# BE_PROJECT_PCB.net
KiCad netlist of a schematic drawn in EAGLE
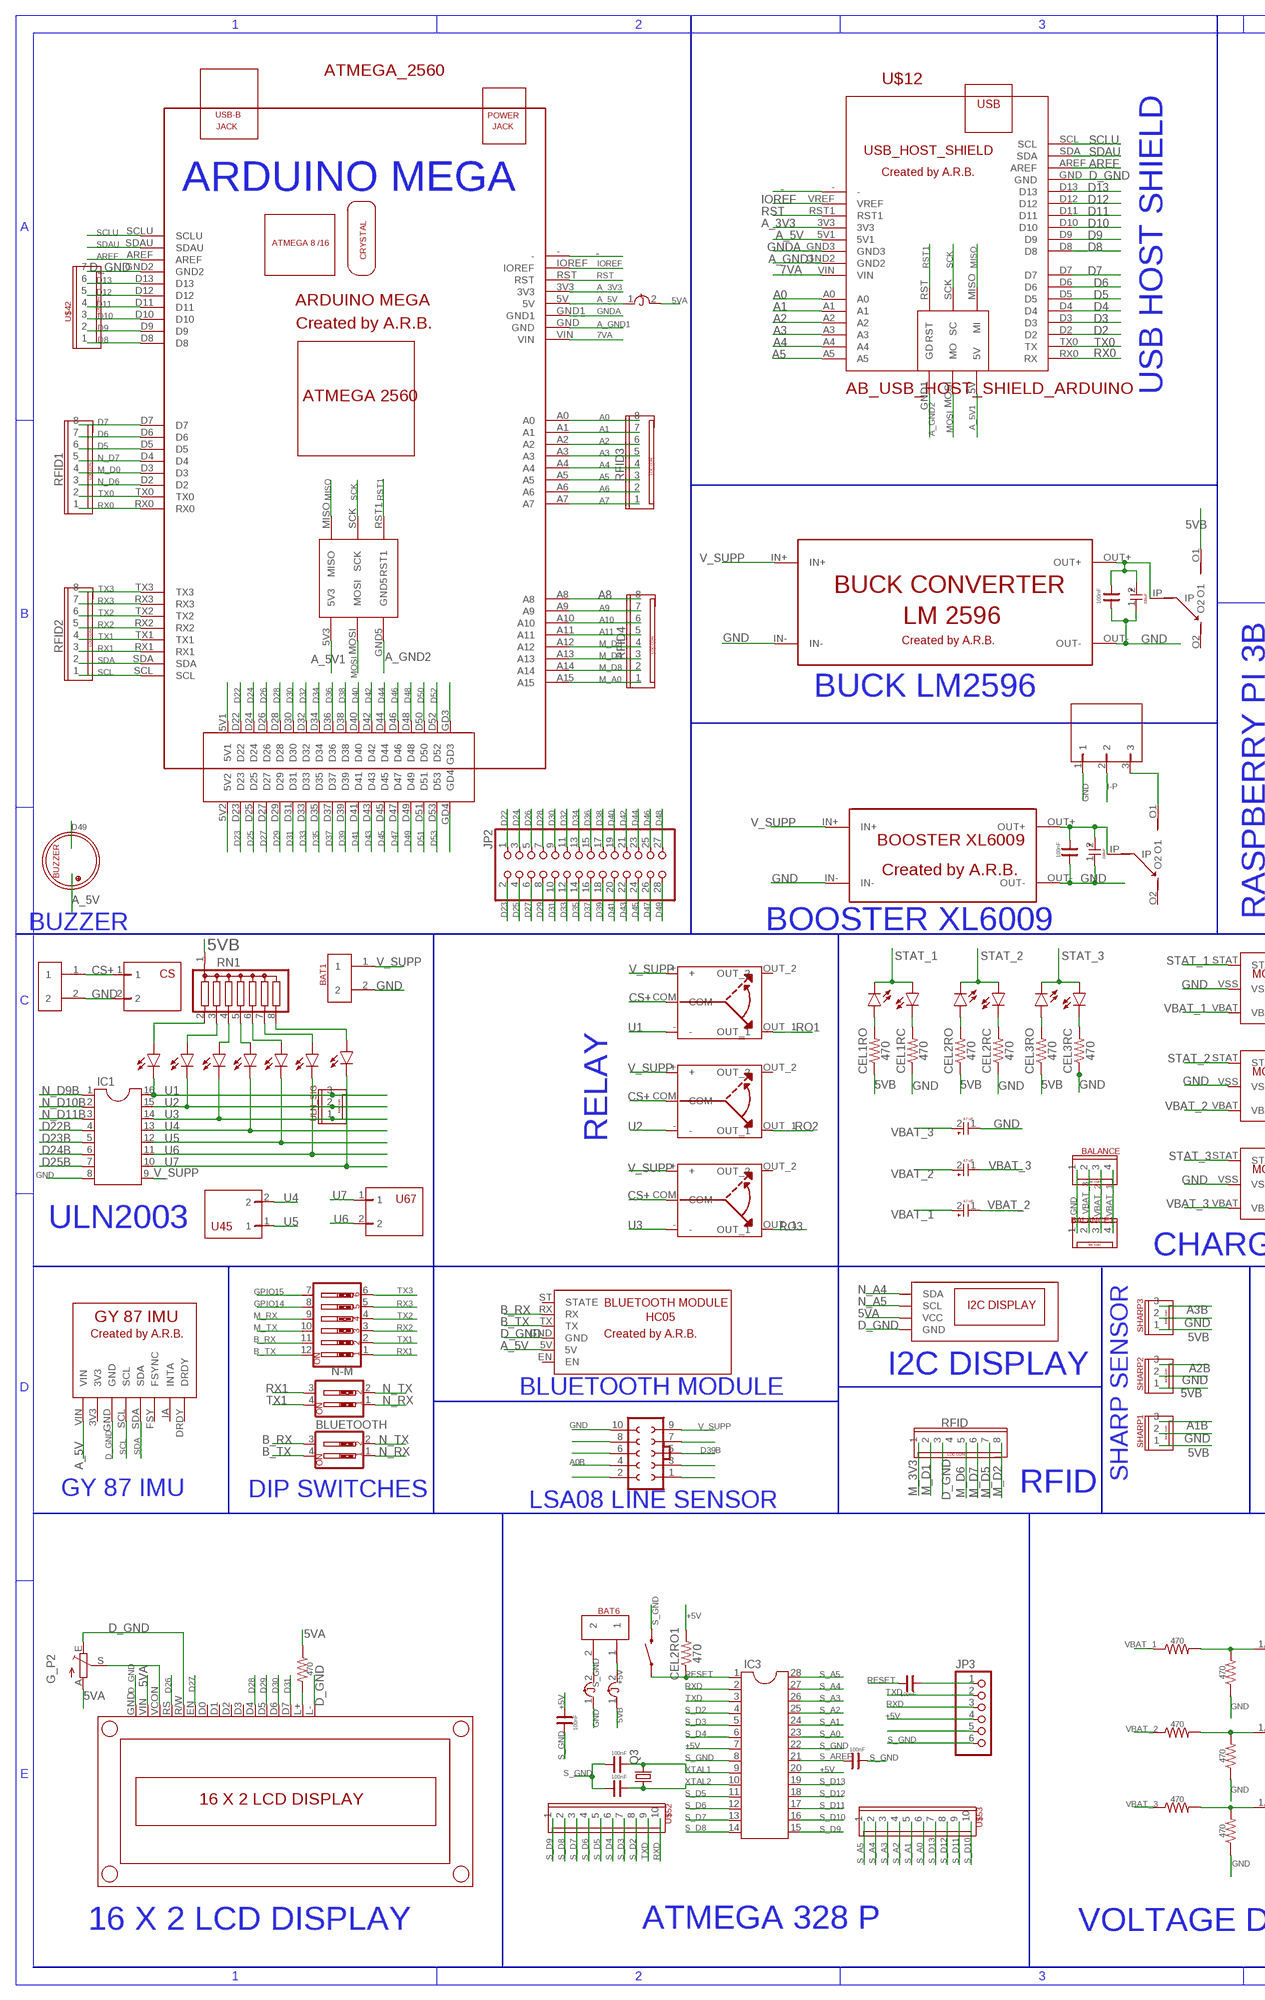
[diagram p0: schematic, sheet 1, part 1 of 3]
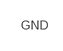
[diagram p1: schematic, sheet 1, part 2 of 3]
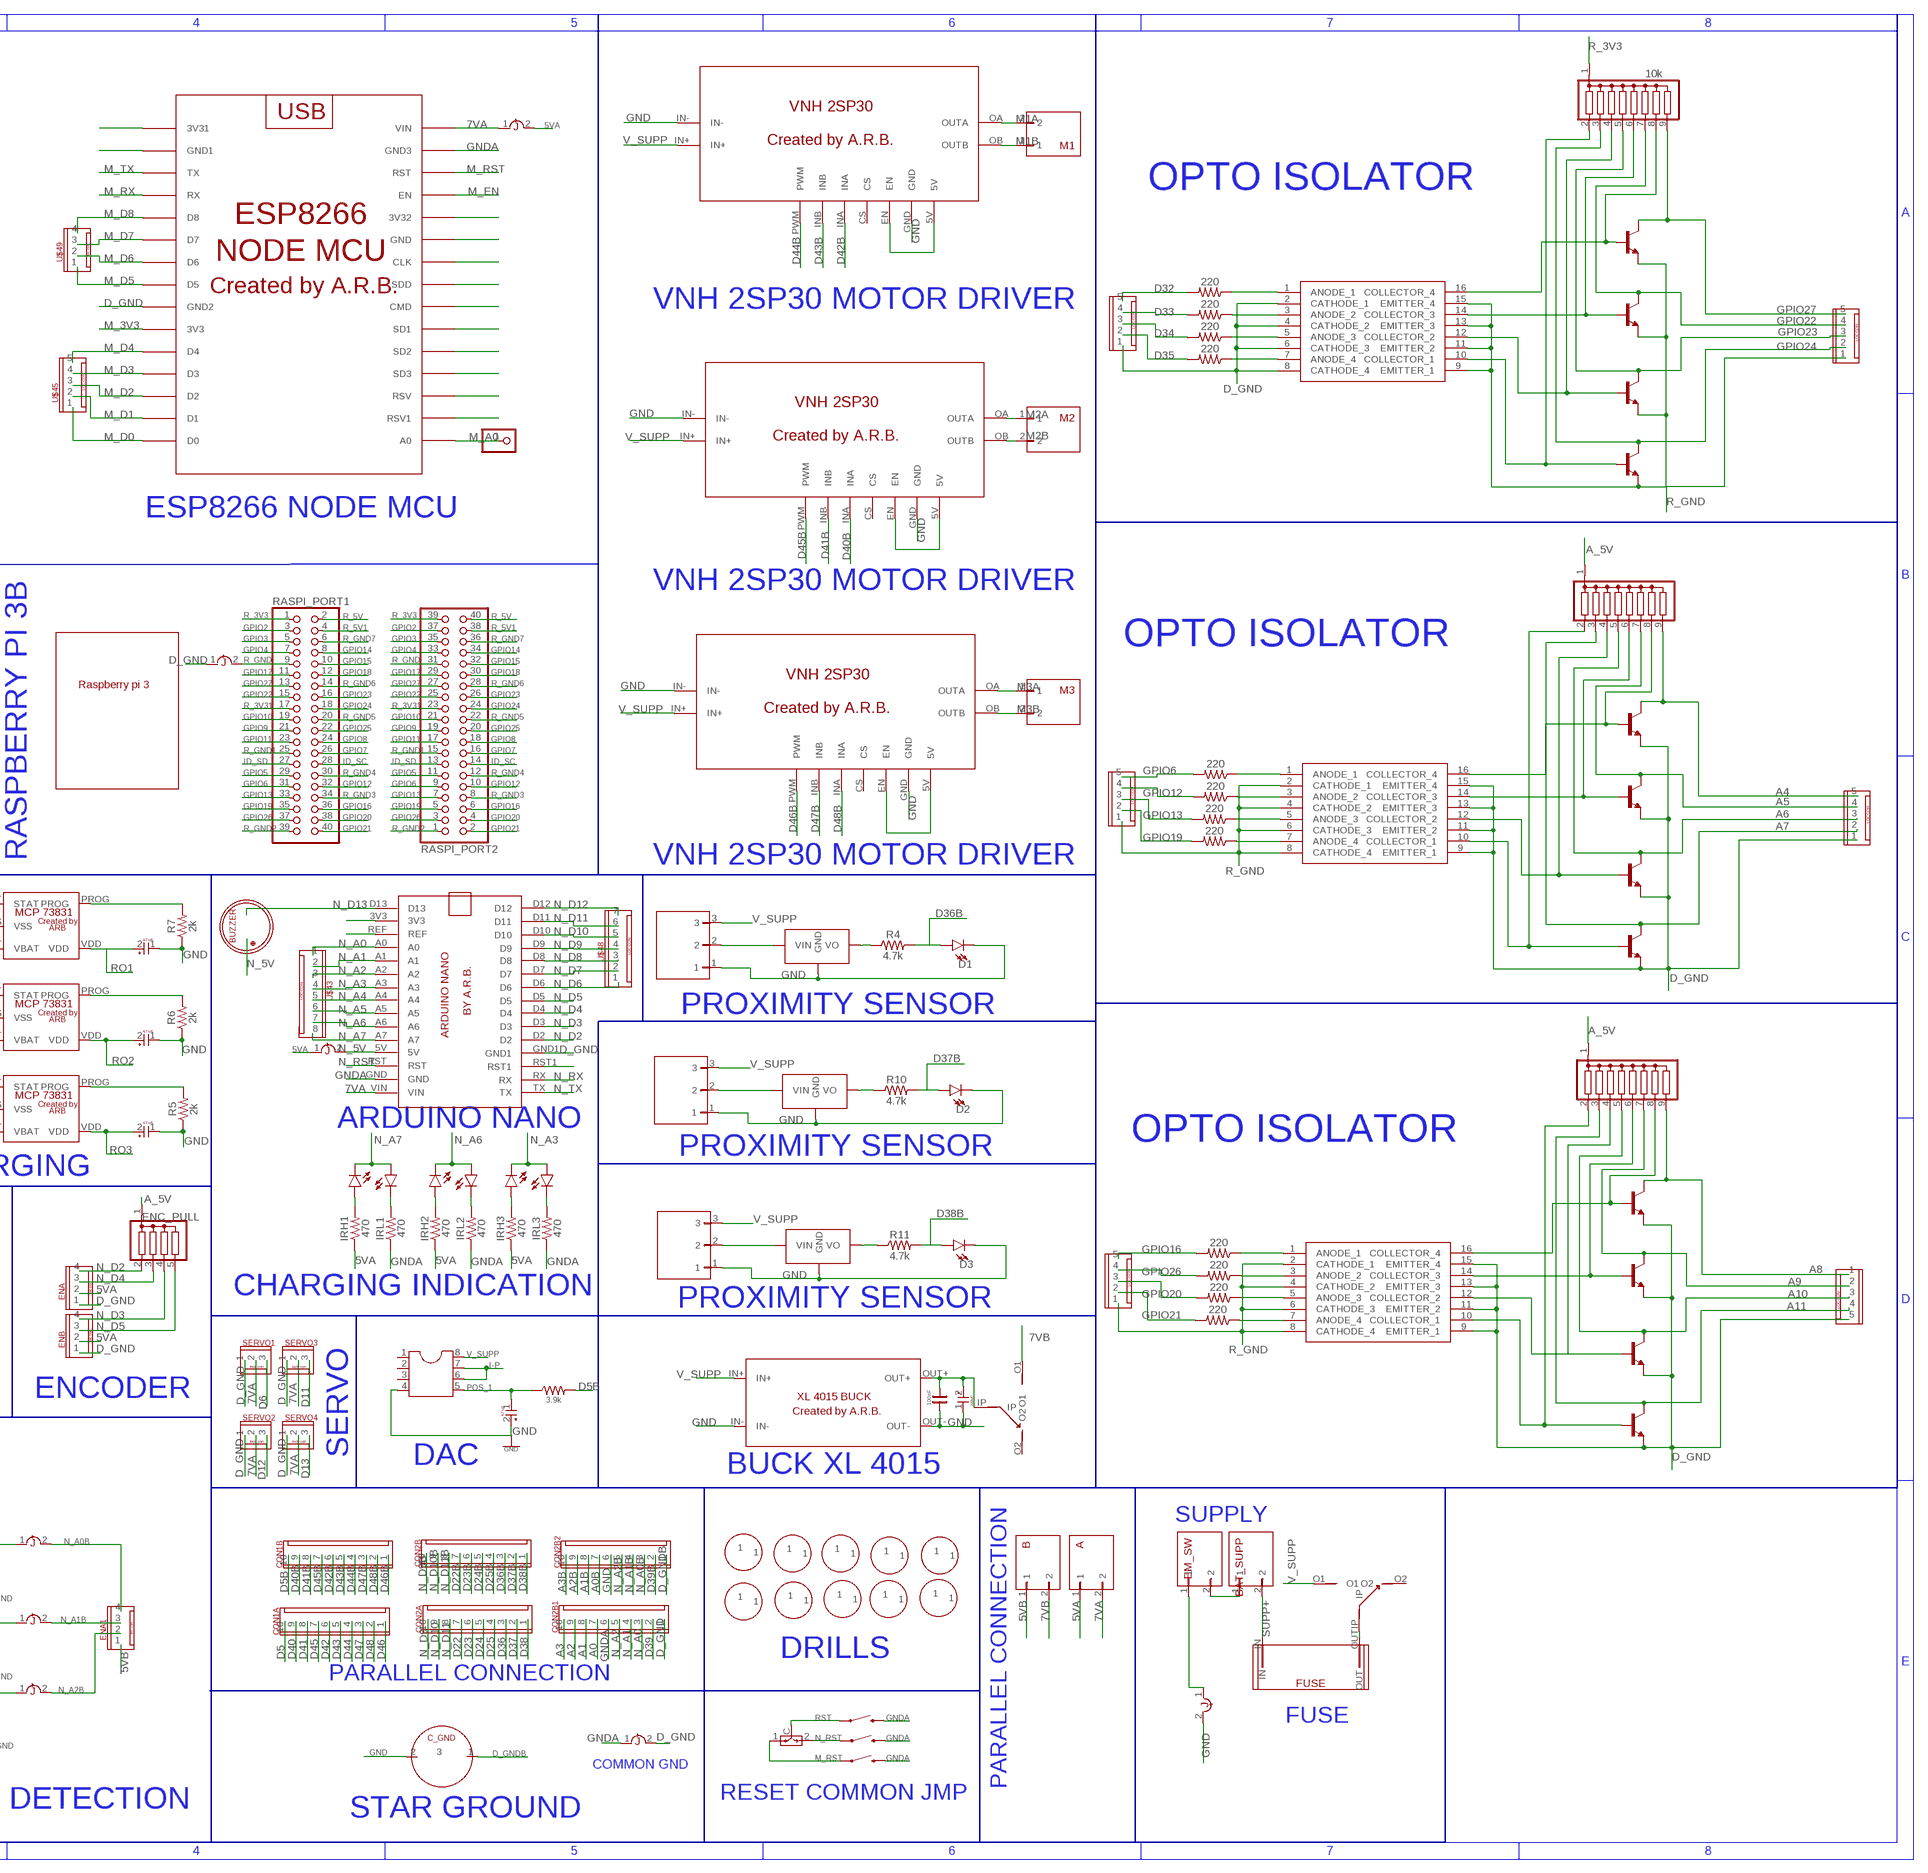
[diagram p2: schematic, sheet 1, part 3 of 3]

(export (version "E")
  (design (tool "Eeschema 10.0.6"))
  (components
    (comp (ref "10K")
      (value "10k")
      (footprint "eagle-import:SIL9")
      (libsource (lib "eagle-import") (part "G08R"))
    )
    (comp (ref "A")
      (value "AB_RIGHT_TER_BLK")
      (footprint "eagle-import:AB_RIGHT_TER_BLK")
      (libsource (lib "eagle-import") (part "AB_RIGHT_TER_BLK"))
    )
    (comp (ref "ATMEGA_2560")
      (value "AB_ARDUINO_MEGA")
      (footprint "eagle-import:AB_ARDUINO_MEGA")
      (libsource (lib "eagle-import") (part "AB_ARDUINO_MEGA"))
    )
    (comp (ref "B")
      (value "AB_RIGHT_TER_BLK")
      (footprint "eagle-import:AB_RIGHT_TER_BLK")
      (libsource (lib "eagle-import") (part "AB_RIGHT_TER_BLK"))
    )
    (comp (ref "BALANCE")
      (value "AB_4PIN_LOC_CONNECTOR")
      (footprint "eagle-import:AB_4PIN_LOC_CONNECTOR")
      (libsource (lib "eagle-import") (part "AB_4PIN_LOC_CONNECTOR"))
    )
    (comp (ref "BALANCE1")
      (value "AB_4PIN_LOC_CONNECTOR")
      (footprint "eagle-import:AB_4PIN_LOC_CONNECTOR")
      (libsource (lib "eagle-import") (part "AB_4PIN_LOC_CONNECTOR"))
    )
    (comp (ref "BAT1")
      (value "AB_SCREW_TERMINAL_5MM_2PIN")
      (footprint "eagle-import:AB_SCREW_TERMINAL_5MM_2PIN")
      (libsource (lib "eagle-import") (part "AB_SCREW_TERMINAL_5MM_2PIN"))
    )
    (comp (ref "BAT6")
      (value "AB_SCREW_TERMINAL_5MM_2PIN")
      (footprint "eagle-import:AB_SCREW_TERMINAL_5MM_2PIN")
      (libsource (lib "eagle-import") (part "AB_SCREW_TERMINAL_5MM_2PIN"))
    )
    (comp (ref "BAT_SUPP")
      (value "AB_RIGHT_TER_BLK")
      (footprint "eagle-import:AB_RIGHT_TER_BLK")
      (libsource (lib "eagle-import") (part "AB_RIGHT_TER_BLK"))
    )
    (comp (ref "BC547")
      (value "BC547")
      (footprint "eagle-import:TO92")
      (libsource (lib "eagle-import") (part "BC547"))
    )
    (comp (ref "BLUETOOTH")
      (value "SW_DIP-2")
      (footprint "eagle-import:EDG-02")
      (libsource (lib "eagle-import") (part "SW_DIP-2"))
    )
    (comp (ref "C1")
      (value "100nF")
      (footprint "eagle-import:C020-035X018")
      (libsource (lib "eagle-import") (part "CNP-C020-035X018"))
    )
    (comp (ref "C2")
      (value "100nF")
      (footprint "eagle-import:C020-035X018")
      (libsource (lib "eagle-import") (part "CNP-C020-035X018"))
    )
    (comp (ref "C3")
      (value "100nF")
      (footprint "eagle-import:C020-035X018")
      (libsource (lib "eagle-import") (part "CNP-C020-035X018"))
    )
    (comp (ref "C4")
      (value "100nF")
      (footprint "eagle-import:C020-035X018")
      (libsource (lib "eagle-import") (part "CNP-C020-035X018"))
    )
    (comp (ref "C5")
      (value "100nF")
      (footprint "eagle-import:C020-035X018")
      (libsource (lib "eagle-import") (part "CNP-C020-035X018"))
    )
    (comp (ref "C6")
      (value "100nF")
      (footprint "eagle-import:C020-035X018")
      (libsource (lib "eagle-import") (part "CNP-C020-035X018"))
    )
    (comp (ref "C7")
      (value "100nF")
      (footprint "eagle-import:C020-035X018")
      (libsource (lib "eagle-import") (part "CNP-C020-035X018"))
    )
    (comp (ref "C8")
      (value "100nF")
      (footprint "eagle-import:C020-035X018")
      (libsource (lib "eagle-import") (part "CNP-C020-035X018"))
    )
    (comp (ref "CEL1CC")
      (value "LED-3MM-NO_SILK")
      (footprint "eagle-import:LED_3MM-NS")
      (libsource (lib "eagle-import") (part "LED-3MM-NO_SILK"))
    )
    (comp (ref "CEL1CO")
      (value "LED-3MM-NO_SILK")
      (footprint "eagle-import:LED_3MM-NS")
      (libsource (lib "eagle-import") (part "LED-3MM-NO_SILK"))
    )
    (comp (ref "CEL1RC")
      (value "470")
      (footprint "eagle-import:AXIAL-0.3")
      (libsource (lib "eagle-import") (part "RESISTORAXIAL-0.3"))
    )
    (comp (ref "CEL1RO")
      (value "470")
      (footprint "eagle-import:AXIAL-0.3")
      (libsource (lib "eagle-import") (part "RESISTORAXIAL-0.3"))
    )
    (comp (ref "CEL2CC")
      (value "LED-3MM-NO_SILK")
      (footprint "eagle-import:LED_3MM-NS")
      (libsource (lib "eagle-import") (part "LED-3MM-NO_SILK"))
    )
    (comp (ref "CEL2CO")
      (value "LED-3MM-NO_SILK")
      (footprint "eagle-import:LED_3MM-NS")
      (libsource (lib "eagle-import") (part "LED-3MM-NO_SILK"))
    )
    (comp (ref "CEL2RC")
      (value "470")
      (footprint "eagle-import:AXIAL-0.3")
      (libsource (lib "eagle-import") (part "RESISTORAXIAL-0.3"))
    )
    (comp (ref "CEL2RO")
      (value "470")
      (footprint "eagle-import:AXIAL-0.3")
      (libsource (lib "eagle-import") (part "RESISTORAXIAL-0.3"))
    )
    (comp (ref "CEL2RO1")
      (value "470")
      (footprint "eagle-import:AXIAL-0.3")
      (libsource (lib "eagle-import") (part "RESISTORAXIAL-0.3"))
    )
    (comp (ref "CEL3CC")
      (value "LED-3MM-NO_SILK")
      (footprint "eagle-import:LED_3MM-NS")
      (libsource (lib "eagle-import") (part "LED-3MM-NO_SILK"))
    )
    (comp (ref "CEL3CO")
      (value "LED-3MM-NO_SILK")
      (footprint "eagle-import:LED_3MM-NS")
      (libsource (lib "eagle-import") (part "LED-3MM-NO_SILK"))
    )
    (comp (ref "CEL3RC")
      (value "470")
      (footprint "eagle-import:AXIAL-0.3")
      (libsource (lib "eagle-import") (part "RESISTORAXIAL-0.3"))
    )
    (comp (ref "CEL3RO")
      (value "470")
      (footprint "eagle-import:AXIAL-0.3")
      (libsource (lib "eagle-import") (part "RESISTORAXIAL-0.3"))
    )
    (comp (ref "CON1A")
      (value "AB_10PIN_LOC_CONNECTOR")
      (footprint "eagle-import:AB_10PIN_LOC_CONNECTOR")
      (libsource (lib "eagle-import") (part "AB_10PIN_LOC_CONNECTOR"))
    )
    (comp (ref "CON1B")
      (value "AB_10PIN_LOC_CONNECTOR")
      (footprint "eagle-import:AB_10PIN_LOC_CONNECTOR")
      (libsource (lib "eagle-import") (part "AB_10PIN_LOC_CONNECTOR"))
    )
    (comp (ref "CON2A")
      (value "AB_10PIN_LOC_CONNECTOR")
      (footprint "eagle-import:AB_10PIN_LOC_CONNECTOR")
      (libsource (lib "eagle-import") (part "AB_10PIN_LOC_CONNECTOR"))
    )
    (comp (ref "CON2B")
      (value "AB_10PIN_LOC_CONNECTOR")
      (footprint "eagle-import:AB_10PIN_LOC_CONNECTOR")
      (libsource (lib "eagle-import") (part "AB_10PIN_LOC_CONNECTOR"))
    )
    (comp (ref "CON2B1")
      (value "AB_10PIN_LOC_CONNECTOR")
      (footprint "eagle-import:AB_10PIN_LOC_CONNECTOR")
      (libsource (lib "eagle-import") (part "AB_10PIN_LOC_CONNECTOR"))
    )
    (comp (ref "CON2B2")
      (value "AB_10PIN_LOC_CONNECTOR")
      (footprint "eagle-import:AB_10PIN_LOC_CONNECTOR")
      (libsource (lib "eagle-import") (part "AB_10PIN_LOC_CONNECTOR"))
    )
    (comp (ref "CS")
      (value "AB_RIGHT_TER_BLK")
      (footprint "eagle-import:AB_RIGHT_TER_BLK")
      (libsource (lib "eagle-import") (part "AB_RIGHT_TER_BLK"))
    )
    (comp (ref "C_GND")
      (value "AB_JOINT_GND")
      (footprint "eagle-import:AB_JOINT_GND")
      (libsource (lib "eagle-import") (part "AB_JOINT_GND"))
    )
    (comp (ref "D1")
      (value "LED-3MM-NO_SILK")
      (footprint "eagle-import:LED_3MM-NS")
      (libsource (lib "eagle-import") (part "LED-3MM-NO_SILK"))
    )
    (comp (ref "D2")
      (value "LED-3MM-NO_SILK")
      (footprint "eagle-import:LED_3MM-NS")
      (libsource (lib "eagle-import") (part "LED-3MM-NO_SILK"))
    )
    (comp (ref "D3")
      (value "LED-3MM-NO_SILK")
      (footprint "eagle-import:LED_3MM-NS")
      (libsource (lib "eagle-import") (part "LED-3MM-NO_SILK"))
    )
    (comp (ref "EM_SW")
      (value "AB_RIGHT_TER_BLK")
      (footprint "eagle-import:AB_RIGHT_TER_BLK")
      (libsource (lib "eagle-import") (part "AB_RIGHT_TER_BLK"))
    )
    (comp (ref "ENA")
      (value "AB_4PIN_LOC_CONNECTOR")
      (footprint "eagle-import:AB_4PIN_LOC_CONNECTOR")
      (libsource (lib "eagle-import") (part "AB_4PIN_LOC_CONNECTOR"))
    )
    (comp (ref "ENA1")
      (value "AB_4PIN_LOC_CONNECTOR")
      (footprint "eagle-import:AB_4PIN_LOC_CONNECTOR")
      (libsource (lib "eagle-import") (part "AB_4PIN_LOC_CONNECTOR"))
    )
    (comp (ref "ENB")
      (value "AB_4PIN_LOC_CONNECTOR")
      (footprint "eagle-import:AB_4PIN_LOC_CONNECTOR")
      (libsource (lib "eagle-import") (part "AB_4PIN_LOC_CONNECTOR"))
    )
    (comp (ref "ENC_PULL")
      (value "G04R")
      (footprint "eagle-import:SIL5")
      (libsource (lib "eagle-import") (part "G04R"))
    )
    (comp (ref "FUSE")
      (value "AB_FUSE_HOLDER")
      (footprint "eagle-import:AB_FUSE_HOLDER")
      (libsource (lib "eagle-import") (part "AB_FUSE_HOLDER"))
    )
    (comp (ref "G_P2")
      (value "TRIM_EU-RS3")
      (footprint "eagle-import:RS3")
      (libsource (lib "eagle-import") (part "TRIM_EU-RS3"))
    )
    (comp (ref "IC1")
      (value "DIL16S")
      (footprint "eagle-import:SOCKET-16")
      (libsource (lib "eagle-import") (part "DIL16S"))
    )
    (comp (ref "IC2")
      (value "DIL8S")
      (footprint "eagle-import:SOCKET-08")
      (fields (field (name "SPICEPREFIX") "X"))
      (libsource (lib "eagle-import") (part "DIL8S"))
    )
    (comp (ref "IC3")
      (value "DIL28-3")
      (footprint "eagle-import:DIL28-3")
      (libsource (lib "eagle-import") (part "DIL28-3"))
    )
    (comp (ref "IC8")
      (value "TLP281-4(GB,J,F)")
      (footprint "eagle-import:SOIC127P700X210-16N")
      (fields
        (field (name "MOUSER_PART_NUMBER") "757-TLP281-4(GB,J,F)")
        (field (name "RS_PART_NUMBER") "7603227P")
      )
      (libsource (lib "eagle-import") (part "TLP281-4(GB,J,F)"))
    )
    (comp (ref "IC9")
      (value "TLP281-4(GB,J,F)")
      (footprint "eagle-import:SOIC127P700X210-16N")
      (fields
        (field (name "MOUSER_PART_NUMBER") "757-TLP281-4(GB,J,F)")
        (field (name "RS_PART_NUMBER") "7603227P")
      )
      (libsource (lib "eagle-import") (part "TLP281-4(GB,J,F)"))
    )
    (comp (ref "IC10")
      (value "TLP281-4(GB,J,F)")
      (footprint "eagle-import:SOIC127P700X210-16N")
      (fields
        (field (name "MOUSER_PART_NUMBER") "757-TLP281-4(GB,J,F)")
        (field (name "RS_PART_NUMBER") "7603227P")
      )
      (libsource (lib "eagle-import") (part "TLP281-4(GB,J,F)"))
    )
    (comp (ref "IH1")
      (value "LED-3MM-NO_SILK")
      (footprint "eagle-import:LED_3MM-NS")
      (libsource (lib "eagle-import") (part "LED-3MM-NO_SILK"))
    )
    (comp (ref "IH2")
      (value "LED-3MM-NO_SILK")
      (footprint "eagle-import:LED_3MM-NS")
      (libsource (lib "eagle-import") (part "LED-3MM-NO_SILK"))
    )
    (comp (ref "IH3")
      (value "LED-3MM-NO_SILK")
      (footprint "eagle-import:LED_3MM-NS")
      (libsource (lib "eagle-import") (part "LED-3MM-NO_SILK"))
    )
    (comp (ref "IL1")
      (value "LED-3MM-NO_SILK")
      (footprint "eagle-import:LED_3MM-NS")
      (libsource (lib "eagle-import") (part "LED-3MM-NO_SILK"))
    )
    (comp (ref "IL2")
      (value "LED-3MM-NO_SILK")
      (footprint "eagle-import:LED_3MM-NS")
      (libsource (lib "eagle-import") (part "LED-3MM-NO_SILK"))
    )
    (comp (ref "IL3")
      (value "LED-3MM-NO_SILK")
      (footprint "eagle-import:LED_3MM-NS")
      (libsource (lib "eagle-import") (part "LED-3MM-NO_SILK"))
    )
    (comp (ref "IRH1")
      (value "470")
      (footprint "eagle-import:AXIAL-0.3")
      (libsource (lib "eagle-import") (part "RESISTORAXIAL-0.3"))
    )
    (comp (ref "IRH2")
      (value "470")
      (footprint "eagle-import:AXIAL-0.3")
      (libsource (lib "eagle-import") (part "RESISTORAXIAL-0.3"))
    )
    (comp (ref "IRH3")
      (value "470")
      (footprint "eagle-import:AXIAL-0.3")
      (libsource (lib "eagle-import") (part "RESISTORAXIAL-0.3"))
    )
    (comp (ref "IRL1")
      (value "470")
      (footprint "eagle-import:AXIAL-0.3")
      (libsource (lib "eagle-import") (part "RESISTORAXIAL-0.3"))
    )
    (comp (ref "IRL2")
      (value "470")
      (footprint "eagle-import:AXIAL-0.3")
      (libsource (lib "eagle-import") (part "RESISTORAXIAL-0.3"))
    )
    (comp (ref "IRL3")
      (value "470")
      (footprint "eagle-import:AXIAL-0.3")
      (libsource (lib "eagle-import") (part "RESISTORAXIAL-0.3"))
    )
    (comp (ref "JP1")
      (value "PINHD-1X1")
      (footprint "eagle-import:1X01")
      (libsource (lib "eagle-import") (part "PINHD-1X1"))
    )
    (comp (ref "JP2")
      (value "PINHD-2X14")
      (footprint "eagle-import:2X14")
      (libsource (lib "eagle-import") (part "PINHD-2X14"))
    )
    (comp (ref "JP3")
      (value "PINHD-1X6")
      (footprint "eagle-import:1X06")
      (libsource (lib "eagle-import") (part "PINHD-1X6"))
    )
    (comp (ref "L1")
      (value "LED-3MM-NO_SILK")
      (footprint "eagle-import:LED_3MM-NS")
      (libsource (lib "eagle-import") (part "LED-3MM-NO_SILK"))
    )
    (comp (ref "L2")
      (value "LED-3MM-NO_SILK")
      (footprint "eagle-import:LED_3MM-NS")
      (libsource (lib "eagle-import") (part "LED-3MM-NO_SILK"))
    )
    (comp (ref "L3")
      (value "LED-3MM-NO_SILK")
      (footprint "eagle-import:LED_3MM-NS")
      (libsource (lib "eagle-import") (part "LED-3MM-NO_SILK"))
    )
    (comp (ref "L4")
      (value "LED-3MM-NO_SILK")
      (footprint "eagle-import:LED_3MM-NS")
      (libsource (lib "eagle-import") (part "LED-3MM-NO_SILK"))
    )
    (comp (ref "L5")
      (value "LED-3MM-NO_SILK")
      (footprint "eagle-import:LED_3MM-NS")
      (libsource (lib "eagle-import") (part "LED-3MM-NO_SILK"))
    )
    (comp (ref "L6")
      (value "LED-3MM-NO_SILK")
      (footprint "eagle-import:LED_3MM-NS")
      (libsource (lib "eagle-import") (part "LED-3MM-NO_SILK"))
    )
    (comp (ref "L7")
      (value "LED-3MM-NO_SILK")
      (footprint "eagle-import:LED_3MM-NS")
      (libsource (lib "eagle-import") (part "LED-3MM-NO_SILK"))
    )
    (comp (ref "LSA_2")
      (value "LSA1")
      (footprint "eagle-import:S10V")
      (libsource (lib "eagle-import") (part "SOCKET-10V"))
    )
    (comp (ref "M1")
      (value "AB_RIGHT_TER_BLK")
      (footprint "eagle-import:AB_RIGHT_TER_BLK")
      (libsource (lib "eagle-import") (part "AB_RIGHT_TER_BLK"))
    )
    (comp (ref "M2")
      (value "AB_RIGHT_TER_BLK")
      (footprint "eagle-import:AB_RIGHT_TER_BLK")
      (libsource (lib "eagle-import") (part "AB_RIGHT_TER_BLK"))
    )
    (comp (ref "M3")
      (value "AB_RIGHT_TER_BLK")
      (footprint "eagle-import:AB_RIGHT_TER_BLK")
      (libsource (lib "eagle-import") (part "AB_RIGHT_TER_BLK"))
    )
    (comp (ref "MEGA_RST")
      (value "MOMENTARY-SWITCH-SPST-PTH-6.0MM")
      (footprint "eagle-import:TACTILE_SWITCH_PTH_6.0MM")
      (libsource (lib "eagle-import") (part "MOMENTARY-SWITCH-SPST-PTH-6.0MM"))
    )
    (comp (ref "MEGA_RST1")
      (value "MOMENTARY-SWITCH-SPST-PTH-6.0MM")
      (footprint "eagle-import:TACTILE_SWITCH_PTH_6.0MM")
      (libsource (lib "eagle-import") (part "MOMENTARY-SWITCH-SPST-PTH-6.0MM"))
    )
    (comp (ref "M_RST")
      (value "MOMENTARY-SWITCH-SPST-PTH-6.0MM")
      (footprint "eagle-import:TACTILE_SWITCH_PTH_6.0MM")
      (libsource (lib "eagle-import") (part "MOMENTARY-SWITCH-SPST-PTH-6.0MM"))
    )
    (comp (ref "N-M")
      (value "SW_DIP-2")
      (footprint "eagle-import:EDG-02")
      (libsource (lib "eagle-import") (part "SW_DIP-2"))
    )
    (comp (ref "NANO")
      (value "AB_JUMPER_ONE_WAY")
      (footprint "eagle-import:AB_JUMPER_ONE_WAY")
      (libsource (lib "eagle-import") (part "AB_JUMPER_ONE_WAY"))
    )
    (comp (ref "NODEMCU")
      (value "AB_JUMPER_ONE_WAY")
      (footprint "eagle-import:AB_JUMPER_ONE_WAY")
      (libsource (lib "eagle-import") (part "AB_JUMPER_ONE_WAY"))
    )
    (comp (ref "N_RST")
      (value "MOMENTARY-SWITCH-SPST-PTH-6.0MM")
      (footprint "eagle-import:TACTILE_SWITCH_PTH_6.0MM")
      (libsource (lib "eagle-import") (part "MOMENTARY-SWITCH-SPST-PTH-6.0MM"))
    )
    (comp (ref "OISO1")
      (value "AB_5PIN_LOC_CONNECTOR")
      (footprint "eagle-import:AB_5PIN_LOC_CONNECTOR")
      (fields (field (name "SPICEPREFIX") "X"))
      (libsource (lib "eagle-import") (part "AB_5PIN_LOC_CONNECTOR"))
    )
    (comp (ref "OISO2")
      (value "AB_5PIN_LOC_CONNECTOR")
      (footprint "eagle-import:AB_5PIN_LOC_CONNECTOR")
      (fields (field (name "SPICEPREFIX") "X"))
      (libsource (lib "eagle-import") (part "AB_5PIN_LOC_CONNECTOR"))
    )
    (comp (ref "OISO3")
      (value "AB_5PIN_LOC_CONNECTOR")
      (footprint "eagle-import:AB_5PIN_LOC_CONNECTOR")
      (fields (field (name "SPICEPREFIX") "X"))
      (libsource (lib "eagle-import") (part "AB_5PIN_LOC_CONNECTOR"))
    )
    (comp (ref "OISO4")
      (value "AB_5PIN_LOC_CONNECTOR")
      (footprint "eagle-import:AB_5PIN_LOC_CONNECTOR")
      (fields (field (name "SPICEPREFIX") "X"))
      (libsource (lib "eagle-import") (part "AB_5PIN_LOC_CONNECTOR"))
    )
    (comp (ref "OISO5")
      (value "AB_5PIN_LOC_CONNECTOR")
      (footprint "eagle-import:AB_5PIN_LOC_CONNECTOR")
      (fields (field (name "SPICEPREFIX") "X"))
      (libsource (lib "eagle-import") (part "AB_5PIN_LOC_CONNECTOR"))
    )
    (comp (ref "OISO6")
      (value "AB_5PIN_LOC_CONNECTOR")
      (footprint "eagle-import:AB_5PIN_LOC_CONNECTOR")
      (fields (field (name "SPICEPREFIX") "X"))
      (libsource (lib "eagle-import") (part "AB_5PIN_LOC_CONNECTOR"))
    )
    (comp (ref "PPR_R1")
      (value "3.9k")
      (footprint "eagle-import:AXIAL-0.3")
      (libsource (lib "eagle-import") (part "RESISTORAXIAL-0.3"))
    )
    (comp (ref "PROX1")
      (value "AB_RIGHT_TER_BLK_3PIN")
      (footprint "eagle-import:AB_RIGHT_TER_BLK_3PIN")
      (libsource (lib "eagle-import") (part "AB_RIGHT_TER_BLK_3PIN"))
    )
    (comp (ref "PROX2")
      (value "AB_RIGHT_TER_BLK_3PIN")
      (footprint "eagle-import:AB_RIGHT_TER_BLK_3PIN")
      (libsource (lib "eagle-import") (part "AB_RIGHT_TER_BLK_3PIN"))
    )
    (comp (ref "PROX3")
      (value "AB_RIGHT_TER_BLK_3PIN")
      (footprint "eagle-import:AB_RIGHT_TER_BLK_3PIN")
      (libsource (lib "eagle-import") (part "AB_RIGHT_TER_BLK_3PIN"))
    )
    (comp (ref "Q3")
      (value "CRYSTALHC49U-V")
      (footprint "eagle-import:HC49U-V")
      (libsource (lib "eagle-import") (part "CRYSTALHC49U-V"))
    )
    (comp (ref "R4")
      (value "4.7k")
      (footprint "eagle-import:AXIAL-0.3")
      (libsource (lib "eagle-import") (part "RESISTORAXIAL-0.3"))
    )
    (comp (ref "R5")
      (value "2k")
      (footprint "eagle-import:AXIAL-0.3")
      (libsource (lib "eagle-import") (part "RESISTORAXIAL-0.3"))
    )
    (comp (ref "R6")
      (value "2k")
      (footprint "eagle-import:AXIAL-0.3")
      (libsource (lib "eagle-import") (part "RESISTORAXIAL-0.3"))
    )
    (comp (ref "R7")
      (value "2k")
      (footprint "eagle-import:AXIAL-0.3")
      (libsource (lib "eagle-import") (part "RESISTORAXIAL-0.3"))
    )
    (comp (ref "R10")
      (value "4.7k")
      (footprint "eagle-import:AXIAL-0.3")
      (libsource (lib "eagle-import") (part "RESISTORAXIAL-0.3"))
    )
    (comp (ref "R11")
      (value "4.7k")
      (footprint "eagle-import:AXIAL-0.3")
      (libsource (lib "eagle-import") (part "RESISTORAXIAL-0.3"))
    )
    (comp (ref "R17")
      (value "470")
      (footprint "eagle-import:AXIAL-0.3")
      (libsource (lib "eagle-import") (part "RESISTORAXIAL-0.3"))
    )
    (comp (ref "R18")
      (value "220")
      (footprint "eagle-import:AXIAL-0.3")
      (libsource (lib "eagle-import") (part "RESISTORAXIAL-0.3"))
    )
    (comp (ref "R19")
      (value "220")
      (footprint "eagle-import:AXIAL-0.3")
      (libsource (lib "eagle-import") (part "RESISTORAXIAL-0.3"))
    )
    (comp (ref "R20")
      (value "220")
      (footprint "eagle-import:AXIAL-0.3")
      (libsource (lib "eagle-import") (part "RESISTORAXIAL-0.3"))
    )
    (comp (ref "R21")
      (value "220")
      (footprint "eagle-import:AXIAL-0.3")
      (libsource (lib "eagle-import") (part "RESISTORAXIAL-0.3"))
    )
    (comp (ref "R22")
      (value "220")
      (footprint "eagle-import:AXIAL-0.3")
      (libsource (lib "eagle-import") (part "RESISTORAXIAL-0.3"))
    )
    (comp (ref "R23")
      (value "220")
      (footprint "eagle-import:AXIAL-0.3")
      (libsource (lib "eagle-import") (part "RESISTORAXIAL-0.3"))
    )
    (comp (ref "R24")
      (value "220")
      (footprint "eagle-import:AXIAL-0.3")
      (libsource (lib "eagle-import") (part "RESISTORAXIAL-0.3"))
    )
    (comp (ref "R25")
      (value "220")
      (footprint "eagle-import:AXIAL-0.3")
      (libsource (lib "eagle-import") (part "RESISTORAXIAL-0.3"))
    )
    (comp (ref "R26")
      (value "220")
      (footprint "eagle-import:AXIAL-0.3")
      (libsource (lib "eagle-import") (part "RESISTORAXIAL-0.3"))
    )
    (comp (ref "R27")
      (value "220")
      (footprint "eagle-import:AXIAL-0.3")
      (libsource (lib "eagle-import") (part "RESISTORAXIAL-0.3"))
    )
    (comp (ref "R28")
      (value "220")
      (footprint "eagle-import:AXIAL-0.3")
      (libsource (lib "eagle-import") (part "RESISTORAXIAL-0.3"))
    )
    (comp (ref "R32")
      (value "220")
      (footprint "eagle-import:AXIAL-0.3")
      (libsource (lib "eagle-import") (part "RESISTORAXIAL-0.3"))
    )
    (comp (ref "R33")
      (value "470")
      (footprint "eagle-import:AXIAL-0.3")
      (libsource (lib "eagle-import") (part "RESISTORAXIAL-0.3"))
    )
    (comp (ref "R34")
      (value "470")
      (footprint "eagle-import:AXIAL-0.3")
      (libsource (lib "eagle-import") (part "RESISTORAXIAL-0.3"))
    )
    (comp (ref "R35")
      (value "470")
      (footprint "eagle-import:AXIAL-0.3")
      (libsource (lib "eagle-import") (part "RESISTORAXIAL-0.3"))
    )
    (comp (ref "R36")
      (value "470")
      (footprint "eagle-import:AXIAL-0.3")
      (libsource (lib "eagle-import") (part "RESISTORAXIAL-0.3"))
    )
    (comp (ref "R37")
      (value "470")
      (footprint "eagle-import:AXIAL-0.3")
      (libsource (lib "eagle-import") (part "RESISTORAXIAL-0.3"))
    )
    (comp (ref "R38")
      (value "470")
      (footprint "eagle-import:AXIAL-0.3")
      (libsource (lib "eagle-import") (part "RESISTORAXIAL-0.3"))
    )
    (comp (ref "RASPI_PORT1")
      (value "PINHD-2X20")
      (footprint "eagle-import:2X20")
      (libsource (lib "eagle-import") (part "PINHD-2X20"))
    )
    (comp (ref "RASPI_PORT2")
      (value "PINHD-2X20")
      (footprint "eagle-import:2X20")
      (libsource (lib "eagle-import") (part "PINHD-2X20"))
    )
    (comp (ref "REL1")
      (value "12v")
      (footprint "eagle-import:AB_ELECTROMAGNETIC_RELAY")
      (libsource (lib "eagle-import") (part "AB_ELECTROMAGNETIC_RELAY"))
    )
    (comp (ref "REL2")
      (value "12v")
      (footprint "eagle-import:AB_ELECTROMAGNETIC_RELAY")
      (libsource (lib "eagle-import") (part "AB_ELECTROMAGNETIC_RELAY"))
    )
    (comp (ref "REL3")
      (value "12v")
      (footprint "eagle-import:AB_ELECTROMAGNETIC_RELAY")
      (libsource (lib "eagle-import") (part "AB_ELECTROMAGNETIC_RELAY"))
    )
    (comp (ref "RFID")
      (value "AB_8PIN_LOC_CONNECTOR")
      (footprint "eagle-import:AB_8PIN_LOC_CONNECTOR")
      (libsource (lib "eagle-import") (part "AB_8PIN_LOC_CONNECTOR"))
    )
    (comp (ref "RFID1")
      (value "AB_8PIN_LOC_CONNECTOR")
      (footprint "eagle-import:AB_8PIN_LOC_CONNECTOR")
      (libsource (lib "eagle-import") (part "AB_8PIN_LOC_CONNECTOR"))
    )
    (comp (ref "RFID2")
      (value "AB_8PIN_LOC_CONNECTOR")
      (footprint "eagle-import:AB_8PIN_LOC_CONNECTOR")
      (libsource (lib "eagle-import") (part "AB_8PIN_LOC_CONNECTOR"))
    )
    (comp (ref "RFID3")
      (value "AB_8PIN_LOC_CONNECTOR")
      (footprint "eagle-import:AB_8PIN_LOC_CONNECTOR")
      (libsource (lib "eagle-import") (part "AB_8PIN_LOC_CONNECTOR"))
    )
    (comp (ref "RFID4")
      (value "AB_8PIN_LOC_CONNECTOR")
      (footprint "eagle-import:AB_8PIN_LOC_CONNECTOR")
      (libsource (lib "eagle-import") (part "AB_8PIN_LOC_CONNECTOR"))
    )
    (comp (ref "RN1")
      (value "G07R")
      (footprint "eagle-import:SIL8")
      (libsource (lib "eagle-import") (part "G07R"))
    )
    (comp (ref "RN6")
      (value "G08R")
      (footprint "eagle-import:SIL9")
      (libsource (lib "eagle-import") (part "G08R"))
    )
    (comp (ref "RN7")
      (value "G08R")
      (footprint "eagle-import:SIL9")
      (libsource (lib "eagle-import") (part "G08R"))
    )
    (comp (ref "SERVO1")
      (value "AB_3PIN_LOC_CONNECTOR")
      (footprint "eagle-import:AB_3PIN_LOC_CONNECTOR")
      (libsource (lib "eagle-import") (part "AB_3PIN_LOC_CONNECTOR"))
    )
    (comp (ref "SERVO2")
      (value "AB_3PIN_LOC_CONNECTOR")
      (footprint "eagle-import:AB_3PIN_LOC_CONNECTOR")
      (libsource (lib "eagle-import") (part "AB_3PIN_LOC_CONNECTOR"))
    )
    (comp (ref "SERVO3")
      (value "AB_3PIN_LOC_CONNECTOR")
      (footprint "eagle-import:AB_3PIN_LOC_CONNECTOR")
      (libsource (lib "eagle-import") (part "AB_3PIN_LOC_CONNECTOR"))
    )
    (comp (ref "SERVO4")
      (value "AB_3PIN_LOC_CONNECTOR")
      (footprint "eagle-import:AB_3PIN_LOC_CONNECTOR")
      (libsource (lib "eagle-import") (part "AB_3PIN_LOC_CONNECTOR"))
    )
    (comp (ref "SHARP1")
      (value "AB_3PIN_LOC_CONNECTOR")
      (footprint "eagle-import:AB_3PIN_LOC_CONNECTOR")
      (libsource (lib "eagle-import") (part "AB_3PIN_LOC_CONNECTOR"))
    )
    (comp (ref "SHARP2")
      (value "AB_3PIN_LOC_CONNECTOR")
      (footprint "eagle-import:AB_3PIN_LOC_CONNECTOR")
      (libsource (lib "eagle-import") (part "AB_3PIN_LOC_CONNECTOR"))
    )
    (comp (ref "SHARP3")
      (value "AB_3PIN_LOC_CONNECTOR")
      (footprint "eagle-import:AB_3PIN_LOC_CONNECTOR")
      (libsource (lib "eagle-import") (part "AB_3PIN_LOC_CONNECTOR"))
    )
    (comp (ref "SW1")
      (value "SW_DIP-6")
      (footprint "eagle-import:EDG-06")
      (libsource (lib "eagle-import") (part "SW_DIP-6"))
    )
    (comp (ref "TR14")
      (value "BC547")
      (footprint "eagle-import:TO92")
      (libsource (lib "eagle-import") (part "BC547"))
    )
    (comp (ref "TR15")
      (value "BC547")
      (footprint "eagle-import:TO92")
      (libsource (lib "eagle-import") (part "BC547"))
    )
    (comp (ref "TR16")
      (value "BC547")
      (footprint "eagle-import:TO92")
      (libsource (lib "eagle-import") (part "BC547"))
    )
    (comp (ref "TR17")
      (value "BC547")
      (footprint "eagle-import:TO92")
      (libsource (lib "eagle-import") (part "BC547"))
    )
    (comp (ref "TR18")
      (value "BC547")
      (footprint "eagle-import:TO92")
      (libsource (lib "eagle-import") (part "BC547"))
    )
    (comp (ref "TR19")
      (value "BC547")
      (footprint "eagle-import:TO92")
      (libsource (lib "eagle-import") (part "BC547"))
    )
    (comp (ref "TR20")
      (value "BC547")
      (footprint "eagle-import:TO92")
      (libsource (lib "eagle-import") (part "BC547"))
    )
    (comp (ref "TR21")
      (value "BC547")
      (footprint "eagle-import:TO92")
      (libsource (lib "eagle-import") (part "BC547"))
    )
    (comp (ref "TR22")
      (value "BC547")
      (footprint "eagle-import:TO92")
      (libsource (lib "eagle-import") (part "BC547"))
    )
    (comp (ref "TR23")
      (value "BC547")
      (footprint "eagle-import:TO92")
      (libsource (lib "eagle-import") (part "BC547"))
    )
    (comp (ref "TR24")
      (value "BC547")
      (footprint "eagle-import:TO92")
      (libsource (lib "eagle-import") (part "BC547"))
    )
    (comp (ref "U$1")
      (value "AB_JUMPER_ONE_WAY")
      (footprint "eagle-import:AB_JUMPER_ONE_WAY")
      (libsource (lib "eagle-import") (part "AB_JUMPER_ONE_WAY"))
    )
    (comp (ref "U$2")
      (value "AB_16X2_LCD_DISPLAY")
      (footprint "eagle-import:AB_16X2_LCD_DISPLAY")
      (libsource (lib "eagle-import") (part "AB_16X2_LCD_DISPLAY"))
    )
    (comp (ref "U$3")
      (value "AB_VNH2SP30")
      (footprint "eagle-import:AB_VNH2SP30_MODULE")
      (libsource (lib "eagle-import") (part "AB_VNH2SP30"))
    )
    (comp (ref "U$4")
      (value "ESP8266_NODEMCU_BY_AB")
      (footprint "eagle-import:AB_ESP8266_BREAKOUT")
      (libsource (lib "eagle-import") (part "ESP8266_NODEMCU_BY_AB"))
    )
    (comp (ref "U$5")
      (value "AB_RASPBERRY_PI_3")
      (footprint "eagle-import:AB_RASPBERRY_PI_3")
      (libsource (lib "eagle-import") (part "AB_RASPBERRY_PI_3"))
    )
    (comp (ref "U$6")
      (value "AB_VNH2SP30")
      (footprint "eagle-import:AB_VNH2SP30_MODULE")
      (libsource (lib "eagle-import") (part "AB_VNH2SP30"))
    )
    (comp (ref "U$7")
      (value "AB_LM2596_BUCK_CONVERTER")
      (footprint "eagle-import:AB_LM2596_BUCK_CONVERTER")
      (libsource (lib "eagle-import") (part "AB_LM2596_BUCK_CONVERTER"))
    )
    (comp (ref "U$8")
      (value "AB_XL6009_BOOST_CONVERTER")
      (footprint "eagle-import:AB_XL6009E1_BOOST_CONVERTER")
      (libsource (lib "eagle-import") (part "AB_XL6009_BOOST_CONVERTER"))
    )
    (comp (ref "U$9")
      (value "AB_VNH2SP30")
      (footprint "eagle-import:AB_VNH2SP30_MODULE")
      (libsource (lib "eagle-import") (part "AB_VNH2SP30"))
    )
    (comp (ref "U$10")
      (value "AB_GY87")
      (footprint "eagle-import:AB_IMU_GY87")
      (libsource (lib "eagle-import") (part "AB_GY87"))
    )
    (comp (ref "U$11")
      (value "AB_BLUETOOTH_HC05")
      (footprint "eagle-import:AB_BLUETOOTH_HC05")
      (libsource (lib "eagle-import") (part "AB_BLUETOOTH_HC05"))
    )
    (comp (ref "U$12")
      (value "AB_USB_HOST_SHIELD_ARDUINO")
      (footprint "eagle-import:AB_USB_HOST_SHIELD_ARDUINO")
      (libsource (lib "eagle-import") (part "AB_USB_HOST_SHIELD_ARDUINO"))
    )
    (comp (ref "U$13")
      (value "AB_XL4015_5A_")
      (footprint "eagle-import:AB_XL_4015_5A_BUCK")
      (libsource (lib "eagle-import") (part "AB_XL4015_5A_"))
    )
    (comp (ref "U$14")
      (value "AB_SW")
      (footprint "eagle-import:AB_SW")
      (libsource (lib "eagle-import") (part "AB_SW"))
    )
    (comp (ref "U$15")
      (value "AB_SW")
      (footprint "eagle-import:AB_SW")
      (libsource (lib "eagle-import") (part "AB_SW"))
    )
    (comp (ref "U$16")
      (value "AB_SW")
      (footprint "eagle-import:AB_SW")
      (libsource (lib "eagle-import") (part "AB_SW"))
    )
    (comp (ref "U$17")
      (value "AB_JUMPER_ONE_WAY")
      (footprint "eagle-import:AB_JUMPER_ONE_WAY")
      (libsource (lib "eagle-import") (part "AB_JUMPER_ONE_WAY"))
    )
    (comp (ref "U$18")
      (value "AB_MCP_73831_LIPO_CHARGER")
      (footprint "eagle-import:AB_MCP_73831_LIPO_CHARGER")
      (libsource (lib "eagle-import") (part "AB_MCP_73831_LIPO_CHARGER"))
    )
    (comp (ref "U$19")
      (value "AB_MCP_73831_LIPO_CHARGER")
      (footprint "eagle-import:AB_MCP_73831_LIPO_CHARGER")
      (libsource (lib "eagle-import") (part "AB_MCP_73831_LIPO_CHARGER"))
    )
    (comp (ref "U$20")
      (value "AB_MCP_73831_LIPO_CHARGER")
      (footprint "eagle-import:AB_MCP_73831_LIPO_CHARGER")
      (libsource (lib "eagle-import") (part "AB_MCP_73831_LIPO_CHARGER"))
    )
    (comp (ref "U$21")
      (value "4.7 uF")
      (footprint "eagle-import:AB_POL_CAP")
      (libsource (lib "eagle-import") (part "AB_POL_CAP"))
    )
    (comp (ref "U$22")
      (value "4.7 uF")
      (footprint "eagle-import:AB_POL_CAP")
      (libsource (lib "eagle-import") (part "AB_POL_CAP"))
    )
    (comp (ref "U$23")
      (value "4.7 uF")
      (footprint "eagle-import:AB_POL_CAP")
      (libsource (lib "eagle-import") (part "AB_POL_CAP"))
    )
    (comp (ref "U$24")
      (value "AB_0.91_INCH_I2C_DISPLAY")
      (footprint "eagle-import:AB_0.91INCH_I2C_DISPLAY")
      (libsource (lib "eagle-import") (part "AB_0.91_INCH_I2C_DISPLAY"))
    )
    (comp (ref "U$25")
      (value "4.7 uF")
      (footprint "eagle-import:AB_POL_CAP")
      (libsource (lib "eagle-import") (part "AB_POL_CAP"))
    )
    (comp (ref "U$26")
      (value "4.7 uF")
      (footprint "eagle-import:AB_POL_CAP")
      (libsource (lib "eagle-import") (part "AB_POL_CAP"))
    )
    (comp (ref "U$27")
      (value "4.7 uF")
      (footprint "eagle-import:AB_POL_CAP")
      (libsource (lib "eagle-import") (part "AB_POL_CAP"))
    )
    (comp (ref "U$28")
      (value "AB_BUZZER")
      (footprint "eagle-import:AB_BUZZER")
      (libsource (lib "eagle-import") (part "AB_BUZZER"))
    )
    (comp (ref "U$29")
      (value "4.7 uF")
      (footprint "eagle-import:AB_POL_CAP")
      (libsource (lib "eagle-import") (part "AB_POL_CAP"))
    )
    (comp (ref "U$30")
      (value "AB_JUMPER_TWO_WAY")
      (footprint "eagle-import:AB_JUMPER_TWO_WAY")
      (libsource (lib "eagle-import") (part "AB_JUMPER_TWO_WAY"))
    )
    (comp (ref "U$31")
      (value "AB_JUMPER_ONE_WAY")
      (footprint "eagle-import:AB_JUMPER_ONE_WAY")
      (libsource (lib "eagle-import") (part "AB_JUMPER_ONE_WAY"))
    )
    (comp (ref "U$32")
      (value "AB_SW")
      (footprint "eagle-import:AB_SW")
      (libsource (lib "eagle-import") (part "AB_SW"))
    )
    (comp (ref "U$33")
      (value "AB_JUMPER_ONE_WAY")
      (footprint "eagle-import:AB_JUMPER_ONE_WAY")
      (libsource (lib "eagle-import") (part "AB_JUMPER_ONE_WAY"))
    )
    (comp (ref "U$34")
      (value "220uF")
      (footprint "eagle-import:AB_POL_CAP")
      (libsource (lib "eagle-import") (part "AB_POL_CAP"))
    )
    (comp (ref "U$35")
      (value "AB_ARDUINO_NANO")
      (footprint "eagle-import:AB_ARDUINO_NANO")
      (libsource (lib "eagle-import") (part "AB_ARDUINO_NANO"))
    )
    (comp (ref "U$36")
      (value "AB_SCREW_TERMINAL_5MM_2PIN")
      (footprint "eagle-import:AB_SCREW_TERMINAL_5MM_2PIN")
      (libsource (lib "eagle-import") (part "AB_SCREW_TERMINAL_5MM_2PIN"))
    )
    (comp (ref "U$37")
      (value "220uF")
      (footprint "eagle-import:AB_POL_CAP")
      (libsource (lib "eagle-import") (part "AB_POL_CAP"))
    )
    (comp (ref "U$38")
      (value "220uF")
      (footprint "eagle-import:AB_POL_CAP")
      (libsource (lib "eagle-import") (part "AB_POL_CAP"))
    )
    (comp (ref "U$39")
      (value "AB_BUZZER")
      (footprint "eagle-import:AB_BUZZER")
      (libsource (lib "eagle-import") (part "AB_BUZZER"))
    )
    (comp (ref "U$40")
      (value "AB_JUMPER_ONE_WAY")
      (footprint "eagle-import:AB_JUMPER_ONE_WAY")
      (libsource (lib "eagle-import") (part "AB_JUMPER_ONE_WAY"))
    )
    (comp (ref "U$41")
      (value "AB_JUMPER_ONE_WAY")
      (footprint "eagle-import:AB_JUMPER_ONE_WAY")
      (libsource (lib "eagle-import") (part "AB_JUMPER_ONE_WAY"))
    )
    (comp (ref "U$42")
      (value "AB_7PIN_LOC_CONNECTOR")
      (footprint "eagle-import:AB_7PIN_LOC_CONNECTOR")
      (libsource (lib "eagle-import") (part "AB_7PIN_LOC_CONNECTOR"))
    )
    (comp (ref "U$43")
      (value "AB_8PIN_LOC_CONNECTOR")
      (footprint "eagle-import:AB_8PIN_LOC_CONNECTOR")
      (libsource (lib "eagle-import") (part "AB_8PIN_LOC_CONNECTOR"))
    )
    (comp (ref "U$44")
      (value "AB_7805_FLAT")
      (footprint "eagle-import:AB_7805_FLAT")
      (libsource (lib "eagle-import") (part "AB_7805_FLAT"))
    )
    (comp (ref "U$45")
      (value "AB_5PIN_LOC_CONNECTOR")
      (footprint "eagle-import:AB_5PIN_LOC_CONNECTOR")
      (fields (field (name "SPICEPREFIX") "X"))
      (libsource (lib "eagle-import") (part "AB_5PIN_LOC_CONNECTOR"))
    )
    (comp (ref "U$46")
      (value "AB_7805_FLAT")
      (footprint "eagle-import:AB_7805_FLAT")
      (libsource (lib "eagle-import") (part "AB_7805_FLAT"))
    )
    (comp (ref "U$47")
      (value "AB_7805_FLAT")
      (footprint "eagle-import:AB_7805_FLAT")
      (libsource (lib "eagle-import") (part "AB_7805_FLAT"))
    )
    (comp (ref "U$48")
      (value "AB_7PIN_LOC_CONNECTOR")
      (footprint "eagle-import:AB_7PIN_LOC_CONNECTOR")
      (libsource (lib "eagle-import") (part "AB_7PIN_LOC_CONNECTOR"))
    )
    (comp (ref "U$49")
      (value "AB_4PIN_LOC_CONNECTOR")
      (footprint "eagle-import:AB_4PIN_LOC_CONNECTOR")
      (libsource (lib "eagle-import") (part "AB_4PIN_LOC_CONNECTOR"))
    )
    (comp (ref "U$50")
      (value "AB_JUMPER_ONE_WAY")
      (footprint "eagle-import:AB_JUMPER_ONE_WAY")
      (libsource (lib "eagle-import") (part "AB_JUMPER_ONE_WAY"))
    )
    (comp (ref "U$51")
      (value "AB_JUMPER_ONE_WAY")
      (footprint "eagle-import:AB_JUMPER_ONE_WAY")
      (libsource (lib "eagle-import") (part "AB_JUMPER_ONE_WAY"))
    )
    (comp (ref "U$52")
      (value "AB_10PIN_LOC_CONNECTOR")
      (footprint "eagle-import:AB_10PIN_LOC_CONNECTOR")
      (libsource (lib "eagle-import") (part "AB_10PIN_LOC_CONNECTOR"))
    )
    (comp (ref "U$53")
      (value "AB_10PIN_LOC_CONNECTOR")
      (footprint "eagle-import:AB_10PIN_LOC_CONNECTOR")
      (libsource (lib "eagle-import") (part "AB_10PIN_LOC_CONNECTOR"))
    )
    (comp (ref "U$54")
      (value "AB_PLATED_DRILL_160MIL")
      (footprint "eagle-import:AB_PLATED_DRILL_160MIL")
      (libsource (lib "eagle-import") (part "AB_PLATED_DRILL_160MIL"))
    )
    (comp (ref "U$55")
      (value "AB_PLATED_DRILL_160MIL")
      (footprint "eagle-import:AB_PLATED_DRILL_160MIL")
      (libsource (lib "eagle-import") (part "AB_PLATED_DRILL_160MIL"))
    )
    (comp (ref "U$56")
      (value "AB_PLATED_DRILL_160MIL")
      (footprint "eagle-import:AB_PLATED_DRILL_160MIL")
      (libsource (lib "eagle-import") (part "AB_PLATED_DRILL_160MIL"))
    )
    (comp (ref "U$57")
      (value "AB_PLATED_DRILL_160MIL")
      (footprint "eagle-import:AB_PLATED_DRILL_160MIL")
      (libsource (lib "eagle-import") (part "AB_PLATED_DRILL_160MIL"))
    )
    (comp (ref "U$58")
      (value "AB_PLATED_DRILL_160MIL")
      (footprint "eagle-import:AB_PLATED_DRILL_160MIL")
      (libsource (lib "eagle-import") (part "AB_PLATED_DRILL_160MIL"))
    )
    (comp (ref "U$59")
      (value "AB_PLATED_DRILL_160MIL")
      (footprint "eagle-import:AB_PLATED_DRILL_160MIL")
      (libsource (lib "eagle-import") (part "AB_PLATED_DRILL_160MIL"))
    )
    (comp (ref "U$60")
      (value "AB_PLATED_DRILL_160MIL")
      (footprint "eagle-import:AB_PLATED_DRILL_160MIL")
      (libsource (lib "eagle-import") (part "AB_PLATED_DRILL_160MIL"))
    )
    (comp (ref "U$61")
      (value "AB_PLATED_DRILL_160MIL")
      (footprint "eagle-import:AB_PLATED_DRILL_160MIL")
      (libsource (lib "eagle-import") (part "AB_PLATED_DRILL_160MIL"))
    )
    (comp (ref "U$62")
      (value "AB_JUMPER_ONE_WAY")
      (footprint "eagle-import:AB_JUMPER_ONE_WAY")
      (libsource (lib "eagle-import") (part "AB_JUMPER_ONE_WAY"))
    )
    (comp (ref "U$63")
      (value "AB_PLATED_DRILL_160MIL")
      (footprint "eagle-import:AB_PLATED_DRILL_160MIL")
      (libsource (lib "eagle-import") (part "AB_PLATED_DRILL_160MIL"))
    )
    (comp (ref "U$64")
      (value "AB_PLATED_DRILL_160MIL")
      (footprint "eagle-import:AB_PLATED_DRILL_160MIL")
      (libsource (lib "eagle-import") (part "AB_PLATED_DRILL_160MIL"))
    )
    (comp (ref "U45")
      (value "AB_RIGHT_TER_BLK")
      (footprint "eagle-import:AB_RIGHT_TER_BLK")
      (libsource (lib "eagle-import") (part "AB_RIGHT_TER_BLK"))
    )
    (comp (ref "U67")
      (value "AB_RIGHT_TER_BLK")
      (footprint "eagle-import:AB_RIGHT_TER_BLK")
      (libsource (lib "eagle-import") (part "AB_RIGHT_TER_BLK"))
    )
    (comp (ref "ULN_SIG")
      (value "AB_3PIN_LOC_CONNECTOR")
      (footprint "eagle-import:AB_3PIN_LOC_CONNECTOR")
      (libsource (lib "eagle-import") (part "AB_3PIN_LOC_CONNECTOR"))
    )
    (comp (ref "V-P")
      (value "AB_RIGHT_TER_BLK_3PIN")
      (footprint "eagle-import:AB_RIGHT_TER_BLK_3PIN")
      (libsource (lib "eagle-import") (part "AB_RIGHT_TER_BLK_3PIN"))
    )
  )
  (nets
    (net (code "1") (name "+5V") (class "Default")
      (node (ref "BAT6") (pin "1") (pinfunction "1_1") (pintype "bidirectional"))
      (node (ref "C5") (pin "1") (pinfunction "1_1") (pintype "passive"))
      (node (ref "CEL2RO1") (pin "P$2") (pinfunction "2_P$2") (pintype "passive"))
      (node (ref "IC3") (pin "20") (pinfunction "20_20") (pintype "passive"))
      (node (ref "IC3") (pin "7") (pinfunction "7_7") (pintype "passive"))
      (node (ref "JP3") (pin "4") (pinfunction "4_4") (pintype "passive"))
      (node (ref "U$50") (pin "2") (pinfunction "2_2") (pintype "bidirectional"))
    )
    (net (code "2") (name "-") (class "Default")
      (node (ref "ATMEGA_2560") (pin "-") (pinfunction "-_-") (pintype "bidirectional"))
      (node (ref "U$12") (pin "-") (pinfunction "-_-") (pintype "bidirectional"))
    )
    (net (code "3") (name "5VA") (class "Default")
      (node (ref "A") (pin "1") (pinfunction "1_1") (pintype "bidirectional"))
      (node (ref "ENA") (pin "2") (pinfunction "2_2") (pintype "bidirectional"))
      (node (ref "ENB") (pin "2") (pinfunction "2_2") (pintype "bidirectional"))
      (node (ref "G_P2") (pin "A") (pinfunction "A_A") (pintype "passive"))
      (node (ref "IRH1") (pin "P$1") (pinfunction "1_P$1") (pintype "passive"))
      (node (ref "IRH2") (pin "P$1") (pinfunction "1_P$1") (pintype "passive"))
      (node (ref "IRH3") (pin "P$1") (pinfunction "1_P$1") (pintype "passive"))
      (node (ref "NANO") (pin "1") (pinfunction "1_1") (pintype "bidirectional"))
      (node (ref "NODEMCU") (pin "2") (pinfunction "2_2") (pintype "bidirectional"))
      (node (ref "R17") (pin "P$1") (pinfunction "1_P$1") (pintype "passive"))
      (node (ref "U$2") (pin "VIN") (pinfunction "VIN_VIN") (pintype "bidirectional"))
      (node (ref "U$24") (pin "VCC") (pinfunction "VCC_VCC") (pintype "bidirectional"))
      (node (ref "U$31") (pin "2") (pinfunction "2_2") (pintype "bidirectional"))
    )
    (net (code "4") (name "5VB") (class "Default")
      (node (ref "B") (pin "1") (pinfunction "1_1") (pintype "bidirectional"))
      (node (ref "CEL1RO") (pin "P$1") (pinfunction "1_P$1") (pintype "passive"))
      (node (ref "CEL2RO") (pin "P$1") (pinfunction "1_P$1") (pintype "passive"))
      (node (ref "CEL3RO") (pin "P$1") (pinfunction "1_P$1") (pintype "passive"))
      (node (ref "ENA1") (pin "1") (pinfunction "1_1") (pintype "bidirectional"))
      (node (ref "RN1") (pin "1") (pinfunction "1_1") (pintype "passive"))
      (node (ref "SHARP1") (pin "1") (pinfunction "1_1") (pintype "bidirectional"))
      (node (ref "SHARP2") (pin "1") (pinfunction "1_1") (pintype "bidirectional"))
      (node (ref "SHARP3") (pin "1") (pinfunction "1_1") (pintype "bidirectional"))
      (node (ref "U$14") (pin "O1") (pinfunction "O1_O1") (pintype "bidirectional"))
      (node (ref "U$50") (pin "1") (pinfunction "1_1") (pintype "bidirectional"))
    )
    (net (code "5") (name "7VA") (class "Default")
      (node (ref "A") (pin "2") (pinfunction "2_2") (pintype "bidirectional"))
      (node (ref "ATMEGA_2560") (pin "VIN") (pinfunction "VIN_VIN") (pintype "bidirectional"))
      (node (ref "NODEMCU") (pin "1") (pinfunction "1_1") (pintype "bidirectional"))
      (node (ref "SERVO1") (pin "2") (pinfunction "2_2") (pintype "bidirectional"))
      (node (ref "SERVO2") (pin "2") (pinfunction "2_2") (pintype "bidirectional"))
      (node (ref "SERVO3") (pin "2") (pinfunction "2_2") (pintype "bidirectional"))
      (node (ref "SERVO4") (pin "2") (pinfunction "2_2") (pintype "bidirectional"))
      (node (ref "U$12") (pin "VIN") (pinfunction "VIN_VIN") (pintype "bidirectional"))
      (node (ref "U$35") (pin "VIN") (pinfunction "VIN_VIN") (pintype "bidirectional"))
      (node (ref "U$4") (pin "VIN") (pinfunction "VIN_VIN") (pintype "bidirectional"))
    )
    (net (code "6") (name "7VB") (class "Default")
      (node (ref "B") (pin "2") (pinfunction "2_2") (pintype "bidirectional"))
      (node (ref "U$16") (pin "O1") (pinfunction "O1_O1") (pintype "bidirectional"))
    )
    (net (code "7") (name "A0") (class "Default")
      (node (ref "ATMEGA_2560") (pin "A0") (pinfunction "A0_A0") (pintype "bidirectional"))
      (node (ref "CON2B1") (pin "7") (pinfunction "7_7") (pintype "bidirectional"))
      (node (ref "RFID3") (pin "8") (pinfunction "8_8") (pintype "bidirectional"))
      (node (ref "U$12") (pin "A0") (pinfunction "A0_A0") (pintype "bidirectional"))
    )
    (net (code "8") (name "A0B") (class "Default")
      (node (ref "CON2B2") (pin "7") (pinfunction "7_7") (pintype "bidirectional"))
      (node (ref "LSA_2") (pin "4") (pinfunction "4_4") (pintype "passive"))
    )
    (net (code "9") (name "A1") (class "Default")
      (node (ref "ATMEGA_2560") (pin "A1") (pinfunction "A1_A1") (pintype "bidirectional"))
      (node (ref "CON2B1") (pin "8") (pinfunction "8_8") (pintype "bidirectional"))
      (node (ref "RFID3") (pin "7") (pinfunction "7_7") (pintype "bidirectional"))
      (node (ref "U$12") (pin "A1") (pinfunction "A1_A1") (pintype "bidirectional"))
    )
    (net (code "10") (name "A1B") (class "Default")
      (node (ref "CON2B2") (pin "8") (pinfunction "8_8") (pintype "bidirectional"))
      (node (ref "SHARP1") (pin "3") (pinfunction "3_3") (pintype "bidirectional"))
    )
    (net (code "11") (name "A2") (class "Default")
      (node (ref "ATMEGA_2560") (pin "A2") (pinfunction "A2_A2") (pintype "bidirectional"))
      (node (ref "CON2B1") (pin "9") (pinfunction "9_9") (pintype "bidirectional"))
      (node (ref "RFID3") (pin "6") (pinfunction "6_6") (pintype "bidirectional"))
      (node (ref "U$12") (pin "A2") (pinfunction "A2_A2") (pintype "bidirectional"))
    )
    (net (code "12") (name "A2B") (class "Default")
      (node (ref "CON2B2") (pin "9") (pinfunction "9_9") (pintype "bidirectional"))
      (node (ref "SHARP2") (pin "3") (pinfunction "3_3") (pintype "bidirectional"))
    )
    (net (code "13") (name "A3") (class "Default")
      (node (ref "ATMEGA_2560") (pin "A3") (pinfunction "A3_A3") (pintype "bidirectional"))
      (node (ref "CON2B1") (pin "10") (pinfunction "10_10") (pintype "bidirectional"))
      (node (ref "RFID3") (pin "5") (pinfunction "5_5") (pintype "bidirectional"))
      (node (ref "U$12") (pin "A3") (pinfunction "A3_A3") (pintype "bidirectional"))
    )
    (net (code "14") (name "A3B") (class "Default")
      (node (ref "CON2B2") (pin "10") (pinfunction "10_10") (pintype "bidirectional"))
      (node (ref "SHARP3") (pin "3") (pinfunction "3_3") (pintype "bidirectional"))
    )
    (net (code "15") (name "A4") (class "Default")
      (node (ref "ATMEGA_2560") (pin "A4") (pinfunction "A4_A4") (pintype "bidirectional"))
      (node (ref "OISO4") (pin "5") (pinfunction "5_5") (pintype "bidirectional"))
      (node (ref "RFID3") (pin "4") (pinfunction "4_4") (pintype "bidirectional"))
      (node (ref "RN6") (pin "9") (pinfunction "9_9") (pintype "passive"))
      (node (ref "TR17") (pin "3") (pinfunction "C_3") (pintype "passive"))
      (node (ref "U$12") (pin "A4") (pinfunction "A4_A4") (pintype "bidirectional"))
    )
    (net (code "16") (name "A5") (class "Default")
      (node (ref "ATMEGA_2560") (pin "A5") (pinfunction "A5_A5") (pintype "bidirectional"))
      (node (ref "OISO4") (pin "4") (pinfunction "4_4") (pintype "bidirectional"))
      (node (ref "RFID3") (pin "3") (pinfunction "3_3") (pintype "bidirectional"))
      (node (ref "RN6") (pin "7") (pinfunction "7_7") (pintype "passive"))
      (node (ref "TR18") (pin "3") (pinfunction "C_3") (pintype "passive"))
      (node (ref "U$12") (pin "A5") (pinfunction "A5_A5") (pintype "bidirectional"))
    )
    (net (code "17") (name "A6") (class "Default")
      (node (ref "ATMEGA_2560") (pin "A6") (pinfunction "A6_A6") (pintype "bidirectional"))
      (node (ref "OISO4") (pin "3") (pinfunction "3_3") (pintype "bidirectional"))
      (node (ref "RFID3") (pin "2") (pinfunction "2_2") (pintype "bidirectional"))
      (node (ref "RN6") (pin "5") (pinfunction "5_5") (pintype "passive"))
      (node (ref "TR19") (pin "3") (pinfunction "C_3") (pintype "passive"))
    )
    (net (code "18") (name "A7") (class "Default")
      (node (ref "ATMEGA_2560") (pin "A7") (pinfunction "A7_A7") (pintype "bidirectional"))
      (node (ref "OISO4") (pin "2") (pinfunction "2_2") (pintype "bidirectional"))
      (node (ref "RFID3") (pin "1") (pinfunction "1_1") (pintype "bidirectional"))
      (node (ref "RN6") (pin "3") (pinfunction "3_3") (pintype "passive"))
      (node (ref "TR20") (pin "3") (pinfunction "C_3") (pintype "passive"))
    )
    (net (code "19") (name "A8") (class "Default")
      (node (ref "ATMEGA_2560") (pin "A8") (pinfunction "A8_A8") (pintype "bidirectional"))
      (node (ref "OISO6") (pin "1") (pinfunction "1_1") (pintype "bidirectional"))
      (node (ref "RFID4") (pin "8") (pinfunction "8_8") (pintype "bidirectional"))
      (node (ref "RN7") (pin "9") (pinfunction "9_9") (pintype "passive"))
      (node (ref "TR21") (pin "3") (pinfunction "C_3") (pintype "passive"))
    )
    (net (code "20") (name "A9") (class "Default")
      (node (ref "ATMEGA_2560") (pin "A9") (pinfunction "A9_A9") (pintype "bidirectional"))
      (node (ref "OISO6") (pin "2") (pinfunction "2_2") (pintype "bidirectional"))
      (node (ref "RFID4") (pin "7") (pinfunction "7_7") (pintype "bidirectional"))
      (node (ref "RN7") (pin "7") (pinfunction "7_7") (pintype "passive"))
      (node (ref "TR22") (pin "3") (pinfunction "C_3") (pintype "passive"))
    )
    (net (code "21") (name "A10") (class "Default")
      (node (ref "ATMEGA_2560") (pin "A10") (pinfunction "A10_A10") (pintype "bidirectional"))
      (node (ref "OISO6") (pin "3") (pinfunction "3_3") (pintype "bidirectional"))
      (node (ref "RFID4") (pin "6") (pinfunction "6_6") (pintype "bidirectional"))
      (node (ref "RN7") (pin "5") (pinfunction "5_5") (pintype "passive"))
      (node (ref "TR23") (pin "3") (pinfunction "C_3") (pintype "passive"))
    )
    (net (code "22") (name "A11") (class "Default")
      (node (ref "ATMEGA_2560") (pin "A11") (pinfunction "A11_A11") (pintype "bidirectional"))
      (node (ref "OISO6") (pin "4") (pinfunction "4_4") (pintype "bidirectional"))
      (node (ref "RFID4") (pin "5") (pinfunction "5_5") (pintype "bidirectional"))
      (node (ref "RN7") (pin "3") (pinfunction "3_3") (pintype "passive"))
      (node (ref "TR24") (pin "3") (pinfunction "C_3") (pintype "passive"))
    )
    (net (code "23") (name "AREF") (class "Default")
      (node (ref "ATMEGA_2560") (pin "AREF") (pinfunction "AREF_AREF") (pintype "bidirectional"))
      (node (ref "U$12") (pin "AREF") (pinfunction "AREF_AREF") (pintype "bidirectional"))
    )
    (net (code "24") (name "A_3V3") (class "Default")
      (node (ref "ATMEGA_2560") (pin "3V3") (pinfunction "3V3_3V3") (pintype "bidirectional"))
      (node (ref "U$12") (pin "3V3") (pinfunction "3V3_3V3") (pintype "bidirectional"))
    )
    (net (code "25") (name "A_5V") (class "Default")
      (node (ref "ATMEGA_2560") (pin "5V") (pinfunction "5V_5V") (pintype "bidirectional"))
      (node (ref "ENC_PULL") (pin "1") (pinfunction "1_1") (pintype "passive"))
      (node (ref "RN6") (pin "1") (pinfunction "1_1") (pintype "passive"))
      (node (ref "RN7") (pin "1") (pinfunction "1_1") (pintype "passive"))
      (node (ref "U$10") (pin "VIN") (pinfunction "VIN_VIN") (pintype "bidirectional"))
      (node (ref "U$11") (pin "5V") (pinfunction "5V_5V") (pintype "bidirectional"))
      (node (ref "U$12") (pin "5V1") (pinfunction "5V1_5V1") (pintype "bidirectional"))
      (node (ref "U$31") (pin "1") (pinfunction "1_1") (pintype "bidirectional"))
      (node (ref "U$39") (pin "+") (pinfunction "+_+") (pintype "bidirectional"))
    )
    (net (code "26") (name "A_5V1") (class "Default")
      (node (ref "ATMEGA_2560") (pin "5V3") (pinfunction "5V3_5V3") (pintype "bidirectional"))
      (node (ref "U$12") (pin "5V") (pinfunction "5V_5V") (pintype "bidirectional"))
    )
    (net (code "27") (name "A_GND1") (class "Default")
      (node (ref "ATMEGA_2560") (pin "GND") (pinfunction "GND_GND") (pintype "bidirectional"))
      (node (ref "U$12") (pin "GND2") (pinfunction "GND2_GND2") (pintype "bidirectional"))
    )
    (net (code "28") (name "A_GND2") (class "Default")
      (node (ref "ATMEGA_2560") (pin "GND5") (pinfunction "GND5_GND5") (pintype "bidirectional"))
      (node (ref "U$12") (pin "GND1") (pinfunction "GD_GND1") (pintype "bidirectional"))
    )
    (net (code "29") (name "B_RX") (class "Default")
      (node (ref "BLUETOOTH") (pin "3") (pinfunction "3_3") (pintype "passive"))
      (node (ref "SW1") (pin "11") (pinfunction "11_11") (pintype "passive"))
      (node (ref "U$11") (pin "RX") (pinfunction "RX_RX") (pintype "bidirectional"))
    )
    (net (code "30") (name "B_TX") (class "Default")
      (node (ref "BLUETOOTH") (pin "4") (pinfunction "4_4") (pintype "passive"))
      (node (ref "SW1") (pin "12") (pinfunction "12_12") (pintype "passive"))
      (node (ref "U$11") (pin "TX") (pinfunction "TX_TX") (pintype "bidirectional"))
    )
    (net (code "31") (name "CS+") (class "Default")
      (node (ref "CS") (pin "1") (pinfunction "1_1") (pintype "bidirectional"))
      (node (ref "REL1") (pin "COM") (pinfunction "COM_COM") (pintype "bidirectional"))
      (node (ref "REL2") (pin "COM") (pinfunction "COM_COM") (pintype "bidirectional"))
      (node (ref "REL3") (pin "COM") (pinfunction "COM_COM") (pintype "bidirectional"))
      (node (ref "U$36") (pin "1") (pinfunction "1_1") (pintype "bidirectional"))
    )
    (net (code "32") (name "D2") (class "Default")
      (node (ref "U$12") (pin "D2") (pinfunction "D2_D2") (pintype "bidirectional"))
    )
    (net (code "33") (name "D3") (class "Default")
      (node (ref "U$12") (pin "D3") (pinfunction "D3_D3") (pintype "bidirectional"))
    )
    (net (code "34") (name "D4") (class "Default")
      (node (ref "U$12") (pin "D4") (pinfunction "D4_D4") (pintype "bidirectional"))
    )
    (net (code "35") (name "D5") (class "Default")
      (node (ref "ATMEGA_2560") (pin "D5") (pinfunction "D5_D5") (pintype "bidirectional"))
      (node (ref "CON1A") (pin "10") (pinfunction "10_10") (pintype "bidirectional"))
      (node (ref "RFID1") (pin "6") (pinfunction "6_6") (pintype "bidirectional"))
      (node (ref "U$12") (pin "D5") (pinfunction "D5_D5") (pintype "bidirectional"))
    )
    (net (code "36") (name "D5B") (class "Default")
      (node (ref "CON1B") (pin "10") (pinfunction "10_10") (pintype "bidirectional"))
      (node (ref "PPR_R1") (pin "P$2") (pinfunction "2_P$2") (pintype "passive"))
    )
    (net (code "37") (name "D6") (class "Default")
      (node (ref "ATMEGA_2560") (pin "D6") (pinfunction "D6_D6") (pintype "bidirectional"))
      (node (ref "RFID1") (pin "7") (pinfunction "7_7") (pintype "bidirectional"))
      (node (ref "SERVO1") (pin "3") (pinfunction "3_3") (pintype "bidirectional"))
      (node (ref "U$12") (pin "D6") (pinfunction "D6_D6") (pintype "bidirectional"))
    )
    (net (code "38") (name "D7") (class "Default")
      (node (ref "ATMEGA_2560") (pin "D7") (pinfunction "D7_D7") (pintype "bidirectional"))
      (node (ref "RFID1") (pin "8") (pinfunction "8_8") (pintype "bidirectional"))
      (node (ref "U$12") (pin "D7") (pinfunction "D7_D7") (pintype "bidirectional"))
    )
    (net (code "39") (name "D8") (class "Default")
      (node (ref "ATMEGA_2560") (pin "D8") (pinfunction "D8_D8") (pintype "bidirectional"))
      (node (ref "U$12") (pin "D8") (pinfunction "D8_D8") (pintype "bidirectional"))
      (node (ref "U$42") (pin "1") (pinfunction "1_1") (pintype "bidirectional"))
    )
    (net (code "40") (name "D9") (class "Default")
      (node (ref "ATMEGA_2560") (pin "D9") (pinfunction "D9_D9") (pintype "bidirectional"))
      (node (ref "U$12") (pin "D9") (pinfunction "D9_D9") (pintype "bidirectional"))
      (node (ref "U$42") (pin "2") (pinfunction "2_2") (pintype "bidirectional"))
    )
    (net (code "41") (name "D10") (class "Default")
      (node (ref "ATMEGA_2560") (pin "D10") (pinfunction "D10_D10") (pintype "bidirectional"))
      (node (ref "U$12") (pin "D10") (pinfunction "D10_D10") (pintype "bidirectional"))
      (node (ref "U$42") (pin "3") (pinfunction "3_3") (pintype "bidirectional"))
    )
    (net (code "42") (name "D11") (class "Default")
      (node (ref "ATMEGA_2560") (pin "D11") (pinfunction "D11_D11") (pintype "bidirectional"))
      (node (ref "SERVO3") (pin "3") (pinfunction "3_3") (pintype "bidirectional"))
      (node (ref "U$12") (pin "D11") (pinfunction "D11_D11") (pintype "bidirectional"))
      (node (ref "U$42") (pin "4") (pinfunction "4_4") (pintype "bidirectional"))
    )
    (net (code "43") (name "D12") (class "Default")
      (node (ref "ATMEGA_2560") (pin "D12") (pinfunction "D12_D12") (pintype "bidirectional"))
      (node (ref "SERVO2") (pin "3") (pinfunction "3_3") (pintype "bidirectional"))
      (node (ref "U$12") (pin "D12") (pinfunction "D12_D12") (pintype "bidirectional"))
      (node (ref "U$42") (pin "5") (pinfunction "5_5") (pintype "bidirectional"))
    )
    (net (code "44") (name "D13") (class "Default")
      (node (ref "ATMEGA_2560") (pin "D13") (pinfunction "D13_D13") (pintype "bidirectional"))
      (node (ref "SERVO4") (pin "3") (pinfunction "3_3") (pintype "bidirectional"))
      (node (ref "U$12") (pin "D13") (pinfunction "D13_D13") (pintype "bidirectional"))
      (node (ref "U$42") (pin "6") (pinfunction "6_6") (pintype "bidirectional"))
    )
    (net (code "45") (name "D22") (class "Default")
      (node (ref "ATMEGA_2560") (pin "D22") (pinfunction "D22_D22") (pintype "bidirectional"))
      (node (ref "CON2A") (pin "7") (pinfunction "7_7") (pintype "bidirectional"))
      (node (ref "JP2") (pin "1") (pinfunction "1_1") (pintype "passive"))
    )
    (net (code "46") (name "D22B") (class "Default")
      (node (ref "CON2B") (pin "7") (pinfunction "7_7") (pintype "bidirectional"))
      (node (ref "IC1") (pin "4") (pinfunction "4_4") (pintype "passive"))
    )
    (net (code "47") (name "D23") (class "Default")
      (node (ref "ATMEGA_2560") (pin "D23") (pinfunction "D23_D23") (pintype "bidirectional"))
      (node (ref "CON2A") (pin "6") (pinfunction "6_6") (pintype "bidirectional"))
      (node (ref "JP2") (pin "2") (pinfunction "2_2") (pintype "passive"))
    )
    (net (code "48") (name "D23B") (class "Default")
      (node (ref "CON2B") (pin "6") (pinfunction "6_6") (pintype "bidirectional"))
      (node (ref "IC1") (pin "5") (pinfunction "5_5") (pintype "passive"))
    )
    (net (code "49") (name "D24") (class "Default")
      (node (ref "ATMEGA_2560") (pin "D24") (pinfunction "D24_D24") (pintype "bidirectional"))
      (node (ref "CON2A") (pin "5") (pinfunction "5_5") (pintype "bidirectional"))
      (node (ref "JP2") (pin "3") (pinfunction "3_3") (pintype "passive"))
    )
    (net (code "50") (name "D24B") (class "Default")
      (node (ref "CON2B") (pin "5") (pinfunction "5_5") (pintype "bidirectional"))
      (node (ref "IC1") (pin "6") (pinfunction "6_6") (pintype "passive"))
    )
    (net (code "51") (name "D25") (class "Default")
      (node (ref "ATMEGA_2560") (pin "D25") (pinfunction "D25_D25") (pintype "bidirectional"))
      (node (ref "CON2A") (pin "4") (pinfunction "4_4") (pintype "bidirectional"))
      (node (ref "JP2") (pin "4") (pinfunction "4_4") (pintype "passive"))
    )
    (net (code "52") (name "D25B") (class "Default")
      (node (ref "CON2B") (pin "4") (pinfunction "4_4") (pintype "bidirectional"))
      (node (ref "IC1") (pin "7") (pinfunction "7_7") (pintype "passive"))
    )
    (net (code "53") (name "D26") (class "Default")
      (node (ref "ATMEGA_2560") (pin "D26") (pinfunction "D26_D26") (pintype "bidirectional"))
      (node (ref "JP2") (pin "5") (pinfunction "5_5") (pintype "passive"))
      (node (ref "U$2") (pin "RS") (pinfunction "RS_RS") (pintype "bidirectional"))
    )
    (net (code "54") (name "D27") (class "Default")
      (node (ref "ATMEGA_2560") (pin "D27") (pinfunction "D27_D27") (pintype "bidirectional"))
      (node (ref "JP2") (pin "6") (pinfunction "6_6") (pintype "passive"))
      (node (ref "U$2") (pin "EN") (pinfunction "EN_EN") (pintype "bidirectional"))
    )
    (net (code "55") (name "D28") (class "Default")
      (node (ref "ATMEGA_2560") (pin "D28") (pinfunction "D28_D28") (pintype "bidirectional"))
      (node (ref "JP2") (pin "7") (pinfunction "7_7") (pintype "passive"))
      (node (ref "U$2") (pin "D4") (pinfunction "D4_D4") (pintype "bidirectional"))
    )
    (net (code "56") (name "D29") (class "Default")
      (node (ref "ATMEGA_2560") (pin "D29") (pinfunction "D29_D29") (pintype "bidirectional"))
      (node (ref "JP2") (pin "8") (pinfunction "8_8") (pintype "passive"))
      (node (ref "U$2") (pin "D5") (pinfunction "D5_D5") (pintype "bidirectional"))
    )
    (net (code "57") (name "D30") (class "Default")
      (node (ref "ATMEGA_2560") (pin "D30") (pinfunction "D30_D30") (pintype "bidirectional"))
      (node (ref "JP2") (pin "9") (pinfunction "9_9") (pintype "passive"))
      (node (ref "U$2") (pin "D6") (pinfunction "D6_D6") (pintype "bidirectional"))
    )
    (net (code "58") (name "D31") (class "Default")
      (node (ref "ATMEGA_2560") (pin "D31") (pinfunction "D31_D31") (pintype "bidirectional"))
      (node (ref "JP2") (pin "10") (pinfunction "10_10") (pintype "passive"))
      (node (ref "U$2") (pin "D7") (pinfunction "D7_D7") (pintype "bidirectional"))
    )
    (net (code "59") (name "D32") (class "Default")
      (node (ref "ATMEGA_2560") (pin "D32") (pinfunction "D32_D32") (pintype "bidirectional"))
      (node (ref "JP2") (pin "11") (pinfunction "11_11") (pintype "passive"))
      (node (ref "OISO1") (pin "5") (pinfunction "5_5") (pintype "bidirectional"))
      (node (ref "R32") (pin "P$2") (pinfunction "2_P$2") (pintype "passive"))
    )
    (net (code "60") (name "D33") (class "Default")
      (node (ref "ATMEGA_2560") (pin "D33") (pinfunction "D33_D33") (pintype "bidirectional"))
      (node (ref "JP2") (pin "12") (pinfunction "12_12") (pintype "passive"))
      (node (ref "OISO1") (pin "4") (pinfunction "4_4") (pintype "bidirectional"))
      (node (ref "R18") (pin "P$2") (pinfunction "2_P$2") (pintype "passive"))
    )
    (net (code "61") (name "D34") (class "Default")
      (node (ref "ATMEGA_2560") (pin "D34") (pinfunction "D34_D34") (pintype "bidirectional"))
      (node (ref "JP2") (pin "13") (pinfunction "13_13") (pintype "passive"))
      (node (ref "OISO1") (pin "3") (pinfunction "3_3") (pintype "bidirectional"))
      (node (ref "R19") (pin "P$2") (pinfunction "2_P$2") (pintype "passive"))
    )
    (net (code "62") (name "D35") (class "Default")
      (node (ref "ATMEGA_2560") (pin "D35") (pinfunction "D35_D35") (pintype "bidirectional"))
      (node (ref "JP2") (pin "14") (pinfunction "14_14") (pintype "passive"))
      (node (ref "OISO1") (pin "2") (pinfunction "2_2") (pintype "bidirectional"))
      (node (ref "R20") (pin "P$2") (pinfunction "2_P$2") (pintype "passive"))
    )
    (net (code "63") (name "D36") (class "Default")
      (node (ref "ATMEGA_2560") (pin "D36") (pinfunction "D36_D36") (pintype "bidirectional"))
      (node (ref "CON2A") (pin "3") (pinfunction "3_3") (pintype "bidirectional"))
      (node (ref "JP2") (pin "15") (pinfunction "15_15") (pintype "passive"))
    )
    (net (code "64") (name "D36B") (class "Default")
      (node (ref "CON2B") (pin "3") (pinfunction "3_3") (pintype "bidirectional"))
      (node (ref "D1") (pin "A") (pinfunction "A_A") (pintype "passive"))
      (node (ref "R4") (pin "P$2") (pinfunction "2_P$2") (pintype "passive"))
    )
    (net (code "65") (name "D37") (class "Default")
      (node (ref "ATMEGA_2560") (pin "D37") (pinfunction "D37_D37") (pintype "bidirectional"))
      (node (ref "CON2A") (pin "2") (pinfunction "2_2") (pintype "bidirectional"))
      (node (ref "JP2") (pin "16") (pinfunction "16_16") (pintype "passive"))
    )
    (net (code "66") (name "D37B") (class "Default")
      (node (ref "CON2B") (pin "2") (pinfunction "2_2") (pintype "bidirectional"))
      (node (ref "D2") (pin "A") (pinfunction "A_A") (pintype "passive"))
      (node (ref "R10") (pin "P$2") (pinfunction "2_P$2") (pintype "passive"))
    )
    (net (code "67") (name "D38") (class "Default")
      (node (ref "ATMEGA_2560") (pin "D38") (pinfunction "D38_D38") (pintype "bidirectional"))
      (node (ref "CON2A") (pin "1") (pinfunction "1_1") (pintype "bidirectional"))
      (node (ref "JP2") (pin "17") (pinfunction "17_17") (pintype "passive"))
    )
    (net (code "68") (name "D38B") (class "Default")
      (node (ref "CON2B") (pin "1") (pinfunction "1_1") (pintype "bidirectional"))
      (node (ref "D3") (pin "A") (pinfunction "A_A") (pintype "passive"))
      (node (ref "R11") (pin "P$2") (pinfunction "2_P$2") (pintype "passive"))
    )
    (net (code "69") (name "D39") (class "Default")
      (node (ref "ATMEGA_2560") (pin "D39") (pinfunction "D39_D39") (pintype "bidirectional"))
      (node (ref "CON2B1") (pin "2") (pinfunction "2_2") (pintype "bidirectional"))
      (node (ref "JP2") (pin "18") (pinfunction "18_18") (pintype "passive"))
    )
    (net (code "70") (name "D39B") (class "Default")
      (node (ref "CON2B2") (pin "2") (pinfunction "2_2") (pintype "bidirectional"))
      (node (ref "LSA_2") (pin "5") (pinfunction "5_5") (pintype "passive"))
    )
    (net (code "71") (name "D40") (class "Default")
      (node (ref "ATMEGA_2560") (pin "D40") (pinfunction "D40_D40") (pintype "bidirectional"))
      (node (ref "CON1A") (pin "9") (pinfunction "9_9") (pintype "bidirectional"))
      (node (ref "JP2") (pin "19") (pinfunction "19_19") (pintype "passive"))
    )
    (net (code "72") (name "D40B") (class "Default")
      (node (ref "CON1B") (pin "9") (pinfunction "9_9") (pintype "bidirectional"))
      (node (ref "U$6") (pin "INA") (pinfunction "INA_INA") (pintype "bidirectional"))
    )
    (net (code "73") (name "D41") (class "Default")
      (node (ref "ATMEGA_2560") (pin "D41") (pinfunction "D41_D41") (pintype "bidirectional"))
      (node (ref "CON1A") (pin "8") (pinfunction "8_8") (pintype "bidirectional"))
      (node (ref "JP2") (pin "20") (pinfunction "20_20") (pintype "passive"))
    )
    (net (code "74") (name "D41B") (class "Default")
      (node (ref "CON1B") (pin "8") (pinfunction "8_8") (pintype "bidirectional"))
      (node (ref "U$6") (pin "INB") (pinfunction "INB_INB") (pintype "bidirectional"))
    )
    (net (code "75") (name "D42") (class "Default")
      (node (ref "ATMEGA_2560") (pin "D42") (pinfunction "D42_D42") (pintype "bidirectional"))
      (node (ref "CON1A") (pin "6") (pinfunction "6_6") (pintype "bidirectional"))
      (node (ref "JP2") (pin "21") (pinfunction "21_21") (pintype "passive"))
    )
    (net (code "76") (name "D42B") (class "Default")
      (node (ref "CON1B") (pin "6") (pinfunction "6_6") (pintype "bidirectional"))
      (node (ref "U$3") (pin "INA") (pinfunction "INA_INA") (pintype "bidirectional"))
    )
    (net (code "77") (name "D43") (class "Default")
      (node (ref "ATMEGA_2560") (pin "D43") (pinfunction "D43_D43") (pintype "bidirectional"))
      (node (ref "CON1A") (pin "5") (pinfunction "5_5") (pintype "bidirectional"))
      (node (ref "JP2") (pin "22") (pinfunction "22_22") (pintype "passive"))
    )
    (net (code "78") (name "D43B") (class "Default")
      (node (ref "CON1B") (pin "5") (pinfunction "5_5") (pintype "bidirectional"))
      (node (ref "U$3") (pin "INB") (pinfunction "INB_INB") (pintype "bidirectional"))
    )
    (net (code "79") (name "D44") (class "Default")
      (node (ref "ATMEGA_2560") (pin "D44") (pinfunction "D44_D44") (pintype "bidirectional"))
      (node (ref "CON1A") (pin "4") (pinfunction "4_4") (pintype "bidirectional"))
      (node (ref "JP2") (pin "23") (pinfunction "23_23") (pintype "passive"))
    )
    (net (code "80") (name "D44B") (class "Default")
      (node (ref "CON1B") (pin "4") (pinfunction "4_4") (pintype "bidirectional"))
      (node (ref "U$3") (pin "PWM") (pinfunction "PWM_PWM") (pintype "bidirectional"))
    )
    (net (code "81") (name "D45") (class "Default")
      (node (ref "ATMEGA_2560") (pin "D45") (pinfunction "D45_D45") (pintype "bidirectional"))
      (node (ref "CON1A") (pin "7") (pinfunction "7_7") (pintype "bidirectional"))
      (node (ref "JP2") (pin "24") (pinfunction "24_24") (pintype "passive"))
    )
    (net (code "82") (name "D45B") (class "Default")
      (node (ref "CON1B") (pin "7") (pinfunction "7_7") (pintype "bidirectional"))
      (node (ref "U$6") (pin "PWM") (pinfunction "PWM_PWM") (pintype "bidirectional"))
    )
    (net (code "83") (name "D46") (class "Default")
      (node (ref "ATMEGA_2560") (pin "D46") (pinfunction "D46_D46") (pintype "bidirectional"))
      (node (ref "CON1A") (pin "1") (pinfunction "1_1") (pintype "bidirectional"))
      (node (ref "JP2") (pin "25") (pinfunction "25_25") (pintype "passive"))
    )
    (net (code "84") (name "D46B") (class "Default")
      (node (ref "CON1B") (pin "1") (pinfunction "1_1") (pintype "bidirectional"))
      (node (ref "U$9") (pin "PWM") (pinfunction "PWM_PWM") (pintype "bidirectional"))
    )
    (net (code "85") (name "D47") (class "Default")
      (node (ref "ATMEGA_2560") (pin "D47") (pinfunction "D47_D47") (pintype "bidirectional"))
      (node (ref "CON1A") (pin "3") (pinfunction "3_3") (pintype "bidirectional"))
      (node (ref "JP2") (pin "26") (pinfunction "26_26") (pintype "passive"))
    )
    (net (code "86") (name "D47B") (class "Default")
      (node (ref "CON1B") (pin "3") (pinfunction "3_3") (pintype "bidirectional"))
      (node (ref "U$9") (pin "INB") (pinfunction "INB_INB") (pintype "bidirectional"))
    )
    (net (code "87") (name "D48") (class "Default")
      (node (ref "ATMEGA_2560") (pin "D48") (pinfunction "D48_D48") (pintype "bidirectional"))
      (node (ref "CON1A") (pin "2") (pinfunction "2_2") (pintype "bidirectional"))
      (node (ref "JP2") (pin "27") (pinfunction "27_27") (pintype "passive"))
    )
    (net (code "88") (name "D48B") (class "Default")
      (node (ref "CON1B") (pin "2") (pinfunction "2_2") (pintype "bidirectional"))
      (node (ref "U$9") (pin "INA") (pinfunction "INA_INA") (pintype "bidirectional"))
    )
    (net (code "89") (name "D49") (class "Default")
      (node (ref "ATMEGA_2560") (pin "D49") (pinfunction "D49_D49") (pintype "bidirectional"))
      (node (ref "JP2") (pin "28") (pinfunction "28_28") (pintype "passive"))
      (node (ref "U$39") (pin "-") (pinfunction "-_-") (pintype "bidirectional"))
    )
    (net (code "90") (name "D50") (class "Default")
      (node (ref "ATMEGA_2560") (pin "D50") (pinfunction "D50_D50") (pintype "bidirectional"))
    )
    (net (code "91") (name "D51") (class "Default")
      (node (ref "ATMEGA_2560") (pin "D51") (pinfunction "D51_D51") (pintype "bidirectional"))
    )
    (net (code "92") (name "D52") (class "Default")
      (node (ref "ATMEGA_2560") (pin "D52") (pinfunction "D52_D52") (pintype "bidirectional"))
    )
    (net (code "93") (name "D53") (class "Default")
      (node (ref "ATMEGA_2560") (pin "D53") (pinfunction "D53_D53") (pintype "bidirectional"))
    )
    (net (code "94") (name "D_GND") (class "Default")
      (node (ref "ATMEGA_2560") (pin "GND2") (pinfunction "GND2_GND2") (pintype "bidirectional"))
      (node (ref "CON2B1") (pin "1") (pinfunction "1_1") (pintype "bidirectional"))
      (node (ref "ENA") (pin "1") (pinfunction "1_1") (pintype "bidirectional"))
      (node (ref "ENB") (pin "1") (pinfunction "1_1") (pintype "bidirectional"))
      (node (ref "G_P2") (pin "E") (pinfunction "E_E") (pintype "passive"))
      (node (ref "IC10") (pin "11") (pinfunction "EMITTER_2_11") (pintype "bidirectional"))
      (node (ref "IC10") (pin "13") (pinfunction "EMITTER_3_13") (pintype "bidirectional"))
      (node (ref "IC10") (pin "15") (pinfunction "EMITTER_4_15") (pintype "bidirectional"))
      (node (ref "IC10") (pin "9") (pinfunction "EMITTER_1_9") (pintype "bidirectional"))
      (node (ref "IC8") (pin "2") (pinfunction "CATHODE_1_2") (pintype "bidirectional"))
      (node (ref "IC8") (pin "4") (pinfunction "CATHODE_2_4") (pintype "bidirectional"))
      (node (ref "IC8") (pin "6") (pinfunction "CATHODE_3_6") (pintype "bidirectional"))
      (node (ref "IC8") (pin "8") (pinfunction "CATHODE_4_8") (pintype "bidirectional"))
      (node (ref "IC9") (pin "11") (pinfunction "EMITTER_2_11") (pintype "bidirectional"))
      (node (ref "IC9") (pin "13") (pinfunction "EMITTER_3_13") (pintype "bidirectional"))
      (node (ref "IC9") (pin "15") (pinfunction "EMITTER_4_15") (pintype "bidirectional"))
      (node (ref "IC9") (pin "9") (pinfunction "EMITTER_1_9") (pintype "bidirectional"))
      (node (ref "OISO1") (pin "1") (pinfunction "1_1") (pintype "bidirectional"))
      (node (ref "OISO4") (pin "1") (pinfunction "1_1") (pintype "bidirectional"))
      (node (ref "OISO6") (pin "5") (pinfunction "5_5") (pintype "bidirectional"))
      (node (ref "RFID") (pin "3") (pinfunction "3_3") (pintype "bidirectional"))
      (node (ref "SERVO1") (pin "1") (pinfunction "1_1") (pintype "bidirectional"))
      (node (ref "SERVO2") (pin "1") (pinfunction "1_1") (pintype "bidirectional"))
      (node (ref "SERVO3") (pin "1") (pinfunction "1_1") (pintype "bidirectional"))
      (node (ref "SERVO4") (pin "1") (pinfunction "1_1") (pintype "bidirectional"))
      (node (ref "TR17") (pin "1") (pinfunction "E_1") (pintype "passive"))
      (node (ref "TR18") (pin "1") (pinfunction "E_1") (pintype "passive"))
      (node (ref "TR19") (pin "1") (pinfunction "E_1") (pintype "passive"))
      (node (ref "TR20") (pin "1") (pinfunction "E_1") (pintype "passive"))
      (node (ref "TR21") (pin "1") (pinfunction "E_1") (pintype "passive"))
      (node (ref "TR22") (pin "1") (pinfunction "E_1") (pintype "passive"))
      (node (ref "TR23") (pin "1") (pinfunction "E_1") (pintype "passive"))
      (node (ref "TR24") (pin "1") (pinfunction "E_1") (pintype "passive"))
      (node (ref "U$10") (pin "GND") (pinfunction "GND_GND") (pintype "bidirectional"))
      (node (ref "U$11") (pin "GND") (pinfunction "GND_GND") (pintype "bidirectional"))
      (node (ref "U$12") (pin "GND") (pinfunction "GND_GND") (pintype "bidirectional"))
      (node (ref "U$17") (pin "1") (pinfunction "1_1") (pintype "bidirectional"))
      (node (ref "U$2") (pin "GND") (pinfunction "GND_GND") (pintype "bidirectional"))
      (node (ref "U$2") (pin "L-") (pinfunction "L-_L-") (pintype "bidirectional"))
      (node (ref "U$2") (pin "R/W") (pinfunction "R/W_R/W") (pintype "bidirectional"))
      (node (ref "U$24") (pin "GND") (pinfunction "GND_GND") (pintype "bidirectional"))
      (node (ref "U$35") (pin "GND1") (pinfunction "GND1_GND1") (pintype "bidirectional"))
      (node (ref "U$4") (pin "GND2") (pinfunction "GND2_GND2") (pintype "bidirectional"))
      (node (ref "U$42") (pin "7") (pinfunction "7_7") (pintype "bidirectional"))
      (node (ref "U$62") (pin "2") (pinfunction "2_2") (pintype "bidirectional"))
    )
    (net (code "95") (name "D_GNDB") (class "Default")
      (node (ref "CON2B2") (pin "1") (pinfunction "1_1") (pintype "bidirectional"))
      (node (ref "C_GND") (pin "1") (pinfunction "1_1") (pintype "bidirectional"))
    )
    (net (code "96") (name "GND") (class "Default")
      (node (ref "BALANCE") (pin "1") (pinfunction "1_1") (pintype "bidirectional"))
      (node (ref "BALANCE1") (pin "1") (pinfunction "1_1") (pintype "bidirectional"))
      (node (ref "BAT1") (pin "2") (pinfunction "2_2") (pintype "bidirectional"))
      (node (ref "C1") (pin "1") (pinfunction "1_1") (pintype "passive"))
      (node (ref "C3") (pin "1") (pinfunction "1_1") (pintype "passive"))
      (node (ref "C4") (pin "1") (pinfunction "1_1") (pintype "passive"))
      (node (ref "CEL1RC") (pin "P$1") (pinfunction "1_P$1") (pintype "passive"))
      (node (ref "CEL2RC") (pin "P$1") (pinfunction "1_P$1") (pintype "passive"))
      (node (ref "CEL3RC") (pin "P$1") (pinfunction "1_P$1") (pintype "passive"))
      (node (ref "CON2B2") (pin "6") (pinfunction "6_6") (pintype "bidirectional"))
      (node (ref "CS") (pin "2") (pinfunction "2_2") (pintype "bidirectional"))
      (node (ref "C_GND") (pin "2") (pinfunction "2_2") (pintype "bidirectional"))
      (node (ref "D1") (pin "K") (pinfunction "C_K") (pintype "passive"))
      (node (ref "D2") (pin "K") (pinfunction "C_K") (pintype "passive"))
      (node (ref "D3") (pin "K") (pinfunction "C_K") (pintype "passive"))
      (node (ref "IC1") (pin "8") (pinfunction "8_8") (pintype "passive"))
      (node (ref "IC2") (pin "4") (pinfunction "4_4") (pintype "passive"))
      (node (ref "LSA_2") (pin "10") (pinfunction "10_10") (pintype "passive"))
      (node (ref "PROX1") (pin "1") (pinfunction "1_1") (pintype "bidirectional"))
      (node (ref "PROX2") (pin "1") (pinfunction "1_1") (pintype "bidirectional"))
      (node (ref "PROX3") (pin "1") (pinfunction "1_1") (pintype "bidirectional"))
      (node (ref "R34") (pin "P$1") (pinfunction "1_P$1") (pintype "passive"))
      (node (ref "R36") (pin "P$1") (pinfunction "1_P$1") (pintype "passive"))
      (node (ref "R38") (pin "P$1") (pinfunction "1_P$1") (pintype "passive"))
      (node (ref "R5") (pin "P$1") (pinfunction "1_P$1") (pintype "passive"))
      (node (ref "R6") (pin "P$1") (pinfunction "1_P$1") (pintype "passive"))
      (node (ref "R7") (pin "P$1") (pinfunction "1_P$1") (pintype "passive"))
      (node (ref "SHARP1") (pin "2") (pinfunction "2_2") (pintype "bidirectional"))
      (node (ref "SHARP2") (pin "2") (pinfunction "2_2") (pintype "bidirectional"))
      (node (ref "SHARP3") (pin "2") (pinfunction "2_2") (pintype "bidirectional"))
      (node (ref "U$13") (pin "IN-") (pinfunction "IN-_IN-") (pintype "bidirectional"))
      (node (ref "U$13") (pin "OUT-") (pinfunction "OUT-_OUT-") (pintype "bidirectional"))
      (node (ref "U$18") (pin "VSS") (pinfunction "VSS_VSS") (pintype "bidirectional"))
      (node (ref "U$19") (pin "VSS") (pinfunction "VSS_VSS") (pintype "bidirectional"))
      (node (ref "U$20") (pin "VSS") (pinfunction "VSS_VSS") (pintype "bidirectional"))
      (node (ref "U$23") (pin "1") (pinfunction "1_1") (pintype "bidirectional"))
      (node (ref "U$25") (pin "1") (pinfunction "1_1") (pintype "bidirectional"))
      (node (ref "U$26") (pin "1") (pinfunction "1_1") (pintype "bidirectional"))
      (node (ref "U$27") (pin "1") (pinfunction "1_1") (pintype "bidirectional"))
      (node (ref "U$29") (pin "2") (pinfunction "2_2") (pintype "bidirectional"))
      (node (ref "U$3") (pin "GND") (pinfunction "GND_GND") (pintype "bidirectional"))
      (node (ref "U$3") (pin "IN-") (pinfunction "IN-_IN-") (pintype "bidirectional"))
      (node (ref "U$33") (pin "2") (pinfunction "2_2") (pintype "bidirectional"))
      (node (ref "U$34") (pin "1") (pinfunction "1_1") (pintype "bidirectional"))
      (node (ref "U$36") (pin "2") (pinfunction "2_2") (pintype "bidirectional"))
      (node (ref "U$37") (pin "1") (pinfunction "1_1") (pintype "bidirectional"))
      (node (ref "U$38") (pin "1") (pinfunction "1_1") (pintype "bidirectional"))
      (node (ref "U$44") (pin "2") (pinfunction "GND_2") (pintype "bidirectional"))
      (node (ref "U$46") (pin "2") (pinfunction "GND_2") (pintype "bidirectional"))
      (node (ref "U$47") (pin "2") (pinfunction "GND_2") (pintype "bidirectional"))
      (node (ref "U$51") (pin "1") (pinfunction "1_1") (pintype "bidirectional"))
      (node (ref "U$6") (pin "GND") (pinfunction "GND_GND") (pintype "bidirectional"))
      (node (ref "U$6") (pin "IN-") (pinfunction "IN-_IN-") (pintype "bidirectional"))
      (node (ref "U$7") (pin "IN-") (pinfunction "IN-_IN-") (pintype "bidirectional"))
      (node (ref "U$7") (pin "OUT-") (pinfunction "OUT-_OUT-") (pintype "bidirectional"))
      (node (ref "U$8") (pin "IN-") (pinfunction "IN-_IN-") (pintype "bidirectional"))
      (node (ref "U$8") (pin "OUT-") (pinfunction "OUT-_OUT-") (pintype "bidirectional"))
      (node (ref "U$9") (pin "GND") (pinfunction "GND_GND") (pintype "bidirectional"))
      (node (ref "U$9") (pin "IN-") (pinfunction "IN-_IN-") (pintype "bidirectional"))
      (node (ref "V-P") (pin "1") (pinfunction "1_1") (pintype "bidirectional"))
    )
    (net (code "97") (name "GNDA") (class "Default")
      (node (ref "ATMEGA_2560") (pin "GND1") (pinfunction "GND1_GND1") (pintype "bidirectional"))
      (node (ref "CON2B1") (pin "6") (pinfunction "6_6") (pintype "bidirectional"))
      (node (ref "IRL1") (pin "P$1") (pinfunction "1_P$1") (pintype "passive"))
      (node (ref "IRL2") (pin "P$1") (pinfunction "1_P$1") (pintype "passive"))
      (node (ref "IRL3") (pin "P$1") (pinfunction "1_P$1") (pintype "passive"))
      (node (ref "MEGA_RST") (pin "3") (pinfunction "2_3") (pintype "passive"))
      (node (ref "M_RST") (pin "3") (pinfunction "2_3") (pintype "passive"))
      (node (ref "N_RST") (pin "3") (pinfunction "2_3") (pintype "passive"))
      (node (ref "U$12") (pin "GND3") (pinfunction "GND3_GND3") (pintype "bidirectional"))
      (node (ref "U$35") (pin "GND") (pinfunction "GND_GND") (pintype "bidirectional"))
      (node (ref "U$4") (pin "GND3") (pinfunction "GND3_GND3") (pintype "bidirectional"))
      (node (ref "U$62") (pin "1") (pinfunction "1_1") (pintype "bidirectional"))
    )
    (net (code "98") (name "GPIO2") (class "Default")
      (node (ref "RASPI_PORT1") (pin "3") (pinfunction "3_3") (pintype "passive"))
      (node (ref "RASPI_PORT2") (pin "37") (pinfunction "37_37") (pintype "passive"))
    )
    (net (code "99") (name "GPIO3") (class "Default")
      (node (ref "RASPI_PORT1") (pin "5") (pinfunction "5_5") (pintype "passive"))
      (node (ref "RASPI_PORT2") (pin "35") (pinfunction "35_35") (pintype "passive"))
    )
    (net (code "100") (name "GPIO4") (class "Default")
      (node (ref "RASPI_PORT1") (pin "7") (pinfunction "7_7") (pintype "passive"))
      (node (ref "RASPI_PORT2") (pin "33") (pinfunction "33_33") (pintype "passive"))
    )
    (net (code "101") (name "GPIO5") (class "Default")
      (node (ref "RASPI_PORT1") (pin "29") (pinfunction "29_29") (pintype "passive"))
      (node (ref "RASPI_PORT2") (pin "11") (pinfunction "11_11") (pintype "passive"))
    )
    (net (code "102") (name "GPIO6") (class "Default")
      (node (ref "OISO3") (pin "5") (pinfunction "5_5") (pintype "bidirectional"))
      (node (ref "R21") (pin "P$2") (pinfunction "2_P$2") (pintype "passive"))
      (node (ref "RASPI_PORT1") (pin "31") (pinfunction "31_31") (pintype "passive"))
      (node (ref "RASPI_PORT2") (pin "9") (pinfunction "9_9") (pintype "passive"))
    )
    (net (code "103") (name "GPIO7") (class "Default")
      (node (ref "RASPI_PORT1") (pin "26") (pinfunction "26_26") (pintype "passive"))
      (node (ref "RASPI_PORT2") (pin "16") (pinfunction "16_16") (pintype "passive"))
    )
    (net (code "104") (name "GPIO8") (class "Default")
      (node (ref "RASPI_PORT1") (pin "24") (pinfunction "24_24") (pintype "passive"))
      (node (ref "RASPI_PORT2") (pin "18") (pinfunction "18_18") (pintype "passive"))
    )
    (net (code "105") (name "GPIO9") (class "Default")
      (node (ref "RASPI_PORT1") (pin "21") (pinfunction "21_21") (pintype "passive"))
      (node (ref "RASPI_PORT2") (pin "19") (pinfunction "19_19") (pintype "passive"))
    )
    (net (code "106") (name "GPIO10") (class "Default")
      (node (ref "RASPI_PORT1") (pin "19") (pinfunction "19_19") (pintype "passive"))
      (node (ref "RASPI_PORT2") (pin "21") (pinfunction "21_21") (pintype "passive"))
    )
    (net (code "107") (name "GPIO11") (class "Default")
      (node (ref "RASPI_PORT1") (pin "23") (pinfunction "23_23") (pintype "passive"))
      (node (ref "RASPI_PORT2") (pin "17") (pinfunction "17_17") (pintype "passive"))
    )
    (net (code "108") (name "GPIO12") (class "Default")
      (node (ref "OISO3") (pin "4") (pinfunction "4_4") (pintype "bidirectional"))
      (node (ref "R22") (pin "P$2") (pinfunction "2_P$2") (pintype "passive"))
      (node (ref "RASPI_PORT1") (pin "32") (pinfunction "32_32") (pintype "passive"))
      (node (ref "RASPI_PORT2") (pin "10") (pinfunction "10_10") (pintype "passive"))
    )
    (net (code "109") (name "GPIO13") (class "Default")
      (node (ref "OISO3") (pin "3") (pinfunction "3_3") (pintype "bidirectional"))
      (node (ref "R23") (pin "P$2") (pinfunction "2_P$2") (pintype "passive"))
      (node (ref "RASPI_PORT1") (pin "33") (pinfunction "33_33") (pintype "passive"))
      (node (ref "RASPI_PORT2") (pin "7") (pinfunction "7_7") (pintype "passive"))
    )
    (net (code "110") (name "GPIO14") (class "Default")
      (node (ref "RASPI_PORT1") (pin "8") (pinfunction "8_8") (pintype "passive"))
      (node (ref "RASPI_PORT2") (pin "34") (pinfunction "34_34") (pintype "passive"))
      (node (ref "SW1") (pin "8") (pinfunction "8_8") (pintype "passive"))
    )
    (net (code "111") (name "GPIO15") (class "Default")
      (node (ref "RASPI_PORT1") (pin "10") (pinfunction "10_10") (pintype "passive"))
      (node (ref "RASPI_PORT2") (pin "32") (pinfunction "32_32") (pintype "passive"))
      (node (ref "SW1") (pin "7") (pinfunction "7_7") (pintype "passive"))
    )
    (net (code "112") (name "GPIO16") (class "Default")
      (node (ref "OISO5") (pin "5") (pinfunction "5_5") (pintype "bidirectional"))
      (node (ref "R25") (pin "P$2") (pinfunction "2_P$2") (pintype "passive"))
      (node (ref "RASPI_PORT1") (pin "36") (pinfunction "36_36") (pintype "passive"))
      (node (ref "RASPI_PORT2") (pin "6") (pinfunction "6_6") (pintype "passive"))
    )
    (net (code "113") (name "GPIO17") (class "Default")
      (node (ref "RASPI_PORT1") (pin "11") (pinfunction "11_11") (pintype "passive"))
      (node (ref "RASPI_PORT2") (pin "29") (pinfunction "29_29") (pintype "passive"))
    )
    (net (code "114") (name "GPIO18") (class "Default")
      (node (ref "RASPI_PORT1") (pin "12") (pinfunction "12_12") (pintype "passive"))
      (node (ref "RASPI_PORT2") (pin "30") (pinfunction "30_30") (pintype "passive"))
    )
    (net (code "115") (name "GPIO19") (class "Default")
      (node (ref "OISO3") (pin "2") (pinfunction "2_2") (pintype "bidirectional"))
      (node (ref "R24") (pin "P$2") (pinfunction "2_P$2") (pintype "passive"))
      (node (ref "RASPI_PORT1") (pin "35") (pinfunction "35_35") (pintype "passive"))
      (node (ref "RASPI_PORT2") (pin "5") (pinfunction "5_5") (pintype "passive"))
    )
    (net (code "116") (name "GPIO20") (class "Default")
      (node (ref "OISO5") (pin "3") (pinfunction "3_3") (pintype "bidirectional"))
      (node (ref "R27") (pin "P$2") (pinfunction "2_P$2") (pintype "passive"))
      (node (ref "RASPI_PORT1") (pin "38") (pinfunction "38_38") (pintype "passive"))
      (node (ref "RASPI_PORT2") (pin "4") (pinfunction "4_4") (pintype "passive"))
    )
    (net (code "117") (name "GPIO21") (class "Default")
      (node (ref "OISO5") (pin "2") (pinfunction "2_2") (pintype "bidirectional"))
      (node (ref "R28") (pin "P$2") (pinfunction "2_P$2") (pintype "passive"))
      (node (ref "RASPI_PORT1") (pin "40") (pinfunction "40_40") (pintype "passive"))
      (node (ref "RASPI_PORT2") (pin "2") (pinfunction "2_2") (pintype "passive"))
    )
    (net (code "118") (name "GPIO22") (class "Default")
      (node (ref "10K") (pin "7") (pinfunction "7_7") (pintype "passive"))
      (node (ref "OISO2") (pin "4") (pinfunction "4_4") (pintype "bidirectional"))
      (node (ref "RASPI_PORT1") (pin "15") (pinfunction "15_15") (pintype "passive"))
      (node (ref "RASPI_PORT2") (pin "25") (pinfunction "25_25") (pintype "passive"))
      (node (ref "TR14") (pin "3") (pinfunction "C_3") (pintype "passive"))
    )
    (net (code "119") (name "GPIO23") (class "Default")
      (node (ref "10K") (pin "5") (pinfunction "5_5") (pintype "passive"))
      (node (ref "OISO2") (pin "3") (pinfunction "3_3") (pintype "bidirectional"))
      (node (ref "RASPI_PORT1") (pin "16") (pinfunction "16_16") (pintype "passive"))
      (node (ref "RASPI_PORT2") (pin "26") (pinfunction "26_26") (pintype "passive"))
      (node (ref "TR15") (pin "3") (pinfunction "C_3") (pintype "passive"))
    )
    (net (code "120") (name "GPIO24") (class "Default")
      (node (ref "10K") (pin "3") (pinfunction "3_3") (pintype "passive"))
      (node (ref "OISO2") (pin "2") (pinfunction "2_2") (pintype "bidirectional"))
      (node (ref "RASPI_PORT1") (pin "18") (pinfunction "18_18") (pintype "passive"))
      (node (ref "RASPI_PORT2") (pin "24") (pinfunction "24_24") (pintype "passive"))
      (node (ref "TR16") (pin "3") (pinfunction "C_3") (pintype "passive"))
    )
    (net (code "121") (name "GPIO25") (class "Default")
      (node (ref "RASPI_PORT1") (pin "22") (pinfunction "22_22") (pintype "passive"))
      (node (ref "RASPI_PORT2") (pin "20") (pinfunction "20_20") (pintype "passive"))
    )
    (net (code "122") (name "GPIO26") (class "Default")
      (node (ref "OISO5") (pin "4") (pinfunction "4_4") (pintype "bidirectional"))
      (node (ref "R26") (pin "P$2") (pinfunction "2_P$2") (pintype "passive"))
      (node (ref "RASPI_PORT1") (pin "37") (pinfunction "37_37") (pintype "passive"))
      (node (ref "RASPI_PORT2") (pin "3") (pinfunction "3_3") (pintype "passive"))
    )
    (net (code "123") (name "GPIO27") (class "Default")
      (node (ref "10K") (pin "9") (pinfunction "9_9") (pintype "passive"))
      (node (ref "BC547") (pin "3") (pinfunction "C_3") (pintype "passive"))
      (node (ref "OISO2") (pin "5") (pinfunction "5_5") (pintype "bidirectional"))
      (node (ref "RASPI_PORT1") (pin "13") (pinfunction "13_13") (pintype "passive"))
      (node (ref "RASPI_PORT2") (pin "27") (pinfunction "27_27") (pintype "passive"))
    )
    (net (code "124") (name "I-P") (class "Default")
      (node (ref "IC2") (pin "6") (pinfunction "6_6") (pintype "passive"))
      (node (ref "IC2") (pin "7") (pinfunction "7_7") (pintype "passive"))
      (node (ref "V-P") (pin "2") (pinfunction "2_2") (pintype "bidirectional"))
    )
    (net (code "125") (name "ID_SC") (class "Default")
      (node (ref "RASPI_PORT1") (pin "28") (pinfunction "28_28") (pintype "passive"))
      (node (ref "RASPI_PORT2") (pin "14") (pinfunction "14_14") (pintype "passive"))
    )
    (net (code "126") (name "ID_SD") (class "Default")
      (node (ref "RASPI_PORT1") (pin "27") (pinfunction "27_27") (pintype "passive"))
      (node (ref "RASPI_PORT2") (pin "13") (pinfunction "13_13") (pintype "passive"))
    )
    (net (code "127") (name "IOREF") (class "Default")
      (node (ref "ATMEGA_2560") (pin "IOREF") (pinfunction "IOREF_IOREF") (pintype "bidirectional"))
      (node (ref "U$12") (pin "VREF") (pinfunction "VREF_VREF") (pintype "bidirectional"))
    )
    (net (code "128") (name "M1A") (class "Default")
      (node (ref "M1") (pin "2") (pinfunction "2_2") (pintype "bidirectional"))
      (node (ref "U$3") (pin "OA") (pinfunction "OUTA_OA") (pintype "bidirectional"))
    )
    (net (code "129") (name "M1B") (class "Default")
      (node (ref "M1") (pin "1") (pinfunction "1_1") (pintype "bidirectional"))
      (node (ref "U$3") (pin "OB") (pinfunction "OUTB_OB") (pintype "bidirectional"))
    )
    (net (code "130") (name "M2A") (class "Default")
      (node (ref "M2") (pin "1") (pinfunction "1_1") (pintype "bidirectional"))
      (node (ref "U$6") (pin "OA") (pinfunction "OUTA_OA") (pintype "bidirectional"))
    )
    (net (code "131") (name "M2B") (class "Default")
      (node (ref "M2") (pin "2") (pinfunction "2_2") (pintype "bidirectional"))
      (node (ref "U$6") (pin "OB") (pinfunction "OUTB_OB") (pintype "bidirectional"))
    )
    (net (code "132") (name "M3A") (class "Default")
      (node (ref "M3") (pin "1") (pinfunction "1_1") (pintype "bidirectional"))
      (node (ref "U$9") (pin "OA") (pinfunction "OUTA_OA") (pintype "bidirectional"))
    )
    (net (code "133") (name "M3B") (class "Default")
      (node (ref "M3") (pin "2") (pinfunction "2_2") (pintype "bidirectional"))
      (node (ref "U$9") (pin "OB") (pinfunction "OUTB_OB") (pintype "bidirectional"))
    )
    (net (code "134") (name "MISO") (class "Default")
      (node (ref "ATMEGA_2560") (pin "MISO") (pinfunction "MISO_MISO") (pintype "bidirectional"))
      (node (ref "U$12") (pin "MISO") (pinfunction "MI_MISO") (pintype "bidirectional"))
    )
    (net (code "135") (name "MOSI") (class "Default")
      (node (ref "ATMEGA_2560") (pin "MOSI") (pinfunction "MOSI_MOSI") (pintype "bidirectional"))
      (node (ref "U$12") (pin "MOSI") (pinfunction "MO_MOSI") (pintype "bidirectional"))
    )
    (net (code "136") (name "M_3V3") (class "Default")
      (node (ref "RFID") (pin "1") (pinfunction "1_1") (pintype "bidirectional"))
      (node (ref "U$4") (pin "3V3") (pinfunction "3V3_3V3") (pintype "bidirectional"))
    )
    (net (code "137") (name "M_A0") (class "Default")
      (node (ref "ATMEGA_2560") (pin "A15") (pinfunction "A15_A15") (pintype "bidirectional"))
      (node (ref "JP1") (pin "1") (pinfunction "1_1") (pintype "passive"))
      (node (ref "RFID4") (pin "1") (pinfunction "1_1") (pintype "bidirectional"))
      (node (ref "U$4") (pin "A0") (pinfunction "A0_A0") (pintype "bidirectional"))
    )
    (net (code "138") (name "M_D0") (class "Default")
      (node (ref "ATMEGA_2560") (pin "D3") (pinfunction "D3_D3") (pintype "bidirectional"))
      (node (ref "RFID1") (pin "4") (pinfunction "4_4") (pintype "bidirectional"))
      (node (ref "U$4") (pin "D0") (pinfunction "D0_D0") (pintype "bidirectional"))
      (node (ref "U$45") (pin "1") (pinfunction "1_1") (pintype "bidirectional"))
    )
    (net (code "139") (name "M_D1") (class "Default")
      (node (ref "RFID") (pin "2") (pinfunction "2_2") (pintype "bidirectional"))
      (node (ref "U$4") (pin "D1") (pinfunction "D1_D1") (pintype "bidirectional"))
      (node (ref "U$45") (pin "2") (pinfunction "2_2") (pintype "bidirectional"))
    )
    (net (code "140") (name "M_D2") (class "Default")
      (node (ref "RFID") (pin "8") (pinfunction "8_8") (pintype "bidirectional"))
      (node (ref "U$4") (pin "D2") (pinfunction "D2_D2") (pintype "bidirectional"))
      (node (ref "U$45") (pin "3") (pinfunction "3_3") (pintype "bidirectional"))
    )
    (net (code "141") (name "M_D3") (class "Default")
      (node (ref "ATMEGA_2560") (pin "A12") (pinfunction "A12_A12") (pintype "bidirectional"))
      (node (ref "RFID4") (pin "4") (pinfunction "4_4") (pintype "bidirectional"))
      (node (ref "U$4") (pin "D3") (pinfunction "D3_D3") (pintype "bidirectional"))
      (node (ref "U$45") (pin "4") (pinfunction "4_4") (pintype "bidirectional"))
    )
    (net (code "142") (name "M_D4") (class "Default")
      (node (ref "ATMEGA_2560") (pin "A13") (pinfunction "A13_A13") (pintype "bidirectional"))
      (node (ref "RFID4") (pin "3") (pinfunction "3_3") (pintype "bidirectional"))
      (node (ref "U$4") (pin "D4") (pinfunction "D4_D4") (pintype "bidirectional"))
      (node (ref "U$45") (pin "5") (pinfunction "5_5") (pintype "bidirectional"))
    )
    (net (code "143") (name "M_D5") (class "Default")
      (node (ref "RFID") (pin "7") (pinfunction "7_7") (pintype "bidirectional"))
      (node (ref "U$4") (pin "D5") (pinfunction "D5_D5") (pintype "bidirectional"))
      (node (ref "U$49") (pin "1") (pinfunction "1_1") (pintype "bidirectional"))
    )
    (net (code "144") (name "M_D6") (class "Default")
      (node (ref "RFID") (pin "5") (pinfunction "5_5") (pintype "bidirectional"))
      (node (ref "U$4") (pin "D6") (pinfunction "D6_D6") (pintype "bidirectional"))
      (node (ref "U$49") (pin "2") (pinfunction "2_2") (pintype "bidirectional"))
    )
    (net (code "145") (name "M_D7") (class "Default")
      (node (ref "RFID") (pin "6") (pinfunction "6_6") (pintype "bidirectional"))
      (node (ref "U$4") (pin "D7") (pinfunction "D7_D7") (pintype "bidirectional"))
      (node (ref "U$49") (pin "3") (pinfunction "3_3") (pintype "bidirectional"))
    )
    (net (code "146") (name "M_D8") (class "Default")
      (node (ref "ATMEGA_2560") (pin "A14") (pinfunction "A14_A14") (pintype "bidirectional"))
      (node (ref "RFID4") (pin "2") (pinfunction "2_2") (pintype "bidirectional"))
      (node (ref "U$4") (pin "D8") (pinfunction "D8_D8") (pintype "bidirectional"))
      (node (ref "U$49") (pin "4") (pinfunction "4_4") (pintype "bidirectional"))
    )
    (net (code "147") (name "M_EN") (class "Default")
      (node (ref "U$4") (pin "EN") (pinfunction "EN_EN") (pintype "bidirectional"))
    )
    (net (code "148") (name "M_RST") (class "Default")
      (node (ref "M_RST") (pin "1") (pinfunction "1_1") (pintype "passive"))
      (node (ref "U$30") (pin "1") (pinfunction "1_1") (pintype "bidirectional"))
      (node (ref "U$4") (pin "RST") (pinfunction "RST_RST") (pintype "bidirectional"))
    )
    (net (code "149") (name "M_RX") (class "Default")
      (node (ref "SW1") (pin "9") (pinfunction "9_9") (pintype "passive"))
      (node (ref "U$4") (pin "RX") (pinfunction "RX_RX") (pintype "bidirectional"))
    )
    (net (code "150") (name "M_TX") (class "Default")
      (node (ref "SW1") (pin "10") (pinfunction "10_10") (pintype "passive"))
      (node (ref "U$4") (pin "TX") (pinfunction "TX_TX") (pintype "bidirectional"))
    )
    (net (code "151") (name "N_5V") (class "Default")
      (node (ref "NANO") (pin "2") (pinfunction "2_2") (pintype "bidirectional"))
      (node (ref "U$28") (pin "+") (pinfunction "+_+") (pintype "bidirectional"))
      (node (ref "U$35") (pin "5V") (pinfunction "5V_5V") (pintype "bidirectional"))
    )
    (net (code "152") (name "N_A0") (class "Default")
      (node (ref "CON2B1") (pin "3") (pinfunction "3_3") (pintype "bidirectional"))
      (node (ref "U$35") (pin "A0") (pinfunction "A0_A0") (pintype "bidirectional"))
      (node (ref "U$43") (pin "1") (pinfunction "1_1") (pintype "bidirectional"))
    )
    (net (code "153") (name "N_A0B") (class "Default")
      (node (ref "CON2B2") (pin "3") (pinfunction "3_3") (pintype "bidirectional"))
      (node (ref "ENA1") (pin "4") (pinfunction "4_4") (pintype "bidirectional"))
      (node (ref "U$1") (pin "2") (pinfunction "2_2") (pintype "bidirectional"))
    )
    (net (code "154") (name "N_A1") (class "Default")
      (node (ref "CON2B1") (pin "4") (pinfunction "4_4") (pintype "bidirectional"))
      (node (ref "U$35") (pin "A1") (pinfunction "A1_A1") (pintype "bidirectional"))
      (node (ref "U$43") (pin "2") (pinfunction "2_2") (pintype "bidirectional"))
    )
    (net (code "155") (name "N_A1B") (class "Default")
      (node (ref "CON2B2") (pin "4") (pinfunction "4_4") (pintype "bidirectional"))
      (node (ref "ENA1") (pin "3") (pinfunction "3_3") (pintype "bidirectional"))
      (node (ref "U$40") (pin "2") (pinfunction "2_2") (pintype "bidirectional"))
    )
    (net (code "156") (name "N_A2") (class "Default")
      (node (ref "CON2B1") (pin "5") (pinfunction "5_5") (pintype "bidirectional"))
      (node (ref "U$35") (pin "A2") (pinfunction "A2_A2") (pintype "bidirectional"))
      (node (ref "U$43") (pin "3") (pinfunction "3_3") (pintype "bidirectional"))
    )
    (net (code "157") (name "N_A2B") (class "Default")
      (node (ref "CON2B2") (pin "5") (pinfunction "5_5") (pintype "bidirectional"))
      (node (ref "ENA1") (pin "2") (pinfunction "2_2") (pintype "bidirectional"))
      (node (ref "U$41") (pin "2") (pinfunction "2_2") (pintype "bidirectional"))
    )
    (net (code "158") (name "N_A3") (class "Default")
      (node (ref "IH3") (pin "K") (pinfunction "C_K") (pintype "passive"))
      (node (ref "IL3") (pin "A") (pinfunction "A_A") (pintype "passive"))
      (node (ref "U$35") (pin "A3") (pinfunction "A3_A3") (pintype "bidirectional"))
      (node (ref "U$43") (pin "4") (pinfunction "4_4") (pintype "bidirectional"))
    )
    (net (code "159") (name "N_A4") (class "Default")
      (node (ref "U$24") (pin "SDA") (pinfunction "SDA_SDA") (pintype "bidirectional"))
      (node (ref "U$35") (pin "A4") (pinfunction "A4_A4") (pintype "bidirectional"))
      (node (ref "U$43") (pin "5") (pinfunction "5_5") (pintype "bidirectional"))
    )
    (net (code "160") (name "N_A5") (class "Default")
      (node (ref "U$24") (pin "SCL") (pinfunction "SCL_SCL") (pintype "bidirectional"))
      (node (ref "U$35") (pin "A5") (pinfunction "A5_A5") (pintype "bidirectional"))
      (node (ref "U$43") (pin "6") (pinfunction "6_6") (pintype "bidirectional"))
    )
    (net (code "161") (name "N_A6") (class "Default")
      (node (ref "IH2") (pin "K") (pinfunction "C_K") (pintype "passive"))
      (node (ref "IL2") (pin "A") (pinfunction "A_A") (pintype "passive"))
      (node (ref "U$35") (pin "A6") (pinfunction "A6_A6") (pintype "bidirectional"))
      (node (ref "U$43") (pin "7") (pinfunction "7_7") (pintype "bidirectional"))
    )
    (net (code "162") (name "N_A7") (class "Default")
      (node (ref "IH1") (pin "K") (pinfunction "C_K") (pintype "passive"))
      (node (ref "IL1") (pin "A") (pinfunction "A_A") (pintype "passive"))
      (node (ref "U$35") (pin "A7") (pinfunction "A7_A7") (pintype "bidirectional"))
      (node (ref "U$43") (pin "8") (pinfunction "8_8") (pintype "bidirectional"))
    )
    (net (code "163") (name "N_D2") (class "Default")
      (node (ref "ENA") (pin "4") (pinfunction "4_4") (pintype "bidirectional"))
      (node (ref "ENC_PULL") (pin "2") (pinfunction "2_2") (pintype "passive"))
      (node (ref "U$35") (pin "D2") (pinfunction "D2_D2") (pintype "bidirectional"))
    )
    (net (code "164") (name "N_D3") (class "Default")
      (node (ref "ENB") (pin "4") (pinfunction "4_4") (pintype "bidirectional"))
      (node (ref "ENC_PULL") (pin "4") (pinfunction "4_4") (pintype "passive"))
      (node (ref "U$35") (pin "D3") (pinfunction "D3_D3") (pintype "bidirectional"))
    )
    (net (code "165") (name "N_D4") (class "Default")
      (node (ref "ENA") (pin "3") (pinfunction "3_3") (pintype "bidirectional"))
      (node (ref "ENC_PULL") (pin "3") (pinfunction "3_3") (pintype "passive"))
      (node (ref "U$35") (pin "D4") (pinfunction "D4_D4") (pintype "bidirectional"))
    )
    (net (code "166") (name "N_D5") (class "Default")
      (node (ref "ENB") (pin "3") (pinfunction "3_3") (pintype "bidirectional"))
      (node (ref "ENC_PULL") (pin "5") (pinfunction "5_5") (pintype "passive"))
      (node (ref "U$35") (pin "D5") (pinfunction "D5_D5") (pintype "bidirectional"))
    )
    (net (code "167") (name "N_D6") (class "Default")
      (node (ref "ATMEGA_2560") (pin "D2") (pinfunction "D2_D2") (pintype "bidirectional"))
      (node (ref "RFID1") (pin "3") (pinfunction "3_3") (pintype "bidirectional"))
      (node (ref "U$35") (pin "D6") (pinfunction "D6_D6") (pintype "bidirectional"))
      (node (ref "U$48") (pin "1") (pinfunction "1_1") (pintype "bidirectional"))
    )
    (net (code "168") (name "N_D7") (class "Default")
      (node (ref "ATMEGA_2560") (pin "D4") (pinfunction "D4_D4") (pintype "bidirectional"))
      (node (ref "RFID1") (pin "5") (pinfunction "5_5") (pintype "bidirectional"))
      (node (ref "U$35") (pin "D7") (pinfunction "D7_D7") (pintype "bidirectional"))
      (node (ref "U$48") (pin "2") (pinfunction "2_2") (pintype "bidirectional"))
    )
    (net (code "169") (name "N_D8") (class "Default")
      (node (ref "U$35") (pin "D8") (pinfunction "D8_D8") (pintype "bidirectional"))
      (node (ref "U$48") (pin "3") (pinfunction "3_3") (pintype "bidirectional"))
    )
    (net (code "170") (name "N_D9") (class "Default")
      (node (ref "CON2A") (pin "10") (pinfunction "10_10") (pintype "bidirectional"))
      (node (ref "U$35") (pin "D9") (pinfunction "D9_D9") (pintype "bidirectional"))
      (node (ref "U$48") (pin "4") (pinfunction "4_4") (pintype "bidirectional"))
    )
    (net (code "171") (name "N_D9B") (class "Default")
      (node (ref "CON2B") (pin "10") (pinfunction "10_10") (pintype "bidirectional"))
      (node (ref "IC1") (pin "1") (pinfunction "1_1") (pintype "passive"))
    )
    (net (code "172") (name "N_D10") (class "Default")
      (node (ref "CON2A") (pin "9") (pinfunction "9_9") (pintype "bidirectional"))
      (node (ref "U$35") (pin "D10") (pinfunction "D10_D10") (pintype "bidirectional"))
      (node (ref "U$48") (pin "5") (pinfunction "5_5") (pintype "bidirectional"))
    )
    (net (code "173") (name "N_D10B") (class "Default")
      (node (ref "CON2B") (pin "9") (pinfunction "9_9") (pintype "bidirectional"))
      (node (ref "IC1") (pin "2") (pinfunction "2_2") (pintype "passive"))
    )
    (net (code "174") (name "N_D11") (class "Default")
      (node (ref "CON2A") (pin "8") (pinfunction "8_8") (pintype "bidirectional"))
      (node (ref "U$35") (pin "D11") (pinfunction "D11_D11") (pintype "bidirectional"))
      (node (ref "U$48") (pin "6") (pinfunction "6_6") (pintype "bidirectional"))
    )
    (net (code "175") (name "N_D11B") (class "Default")
      (node (ref "CON2B") (pin "8") (pinfunction "8_8") (pintype "bidirectional"))
      (node (ref "IC1") (pin "3") (pinfunction "3_3") (pintype "passive"))
    )
    (net (code "176") (name "N_D12") (class "Default")
      (node (ref "U$35") (pin "D12") (pinfunction "D12_D12") (pintype "bidirectional"))
      (node (ref "U$48") (pin "7") (pinfunction "7_7") (pintype "bidirectional"))
    )
    (net (code "177") (name "N_D13") (class "Default")
      (node (ref "U$28") (pin "-") (pinfunction "-_-") (pintype "bidirectional"))
      (node (ref "U$35") (pin "D13") (pinfunction "D13_D13") (pintype "bidirectional"))
    )
    (net (code "178") (name "N_RST") (class "Default")
      (node (ref "N_RST") (pin "1") (pinfunction "1_1") (pintype "passive"))
      (node (ref "U$30") (pin "2") (pinfunction "2_2") (pintype "bidirectional"))
      (node (ref "U$35") (pin "RST") (pinfunction "RST_RST") (pintype "bidirectional"))
    )
    (net (code "179") (name "N_RX") (class "Default")
      (node (ref "BLUETOOTH") (pin "1") (pinfunction "1_1") (pintype "passive"))
      (node (ref "N-M") (pin "1") (pinfunction "1_1") (pintype "passive"))
      (node (ref "U$35") (pin "RX") (pinfunction "RX_RX") (pintype "bidirectional"))
    )
    (net (code "180") (name "N_TX") (class "Default")
      (node (ref "BLUETOOTH") (pin "2") (pinfunction "2_2") (pintype "passive"))
      (node (ref "N-M") (pin "2") (pinfunction "2_2") (pintype "passive"))
      (node (ref "U$35") (pin "TX") (pinfunction "TX_TX") (pintype "bidirectional"))
    )
    (net (code "181") (name "Net-(BAT_SUPP-Pad1)") (class "Default")
      (node (ref "BAT_SUPP") (pin "1") (pinfunction "1_1") (pintype "bidirectional"))
      (node (ref "EM_SW") (pin "2") (pinfunction "2_2") (pintype "bidirectional"))
    )
    (net (code "182") (name "Net-(BC547-B)") (class "Default")
      (node (ref "10K") (pin "8") (pinfunction "8_8") (pintype "passive"))
      (node (ref "BC547") (pin "2") (pinfunction "B_2") (pintype "passive"))
      (node (ref "IC8") (pin "16") (pinfunction "COLLECTOR_4_16") (pintype "bidirectional"))
    )
    (net (code "183") (name "Net-(C1-Pad2)") (class "Default")
      (node (ref "C1") (pin "2") (pinfunction "2_2") (pintype "passive"))
      (node (ref "U$14") (pin "IP") (pinfunction "IP_IP") (pintype "bidirectional"))
      (node (ref "U$34") (pin "2") (pinfunction "2_2") (pintype "bidirectional"))
      (node (ref "U$7") (pin "OUT+") (pinfunction "OUT+_OUT+") (pintype "bidirectional"))
    )
    (net (code "184") (name "Net-(C2-Pad1)") (class "Default")
      (node (ref "C2") (pin "1") (pinfunction "1_1") (pintype "passive"))
      (node (ref "JP3") (pin "1") (pinfunction "1_1") (pintype "passive"))
    )
    (net (code "185") (name "Net-(C3-Pad2)") (class "Default")
      (node (ref "C3") (pin "2") (pinfunction "2_2") (pintype "passive"))
      (node (ref "U$15") (pin "IP") (pinfunction "IP_IP") (pintype "bidirectional"))
      (node (ref "U$37") (pin "2") (pinfunction "2_2") (pintype "bidirectional"))
      (node (ref "U$8") (pin "OUT+") (pinfunction "OUT+_OUT+") (pintype "bidirectional"))
    )
    (net (code "186") (name "Net-(C4-Pad2)") (class "Default")
      (node (ref "C4") (pin "2") (pinfunction "2_2") (pintype "passive"))
      (node (ref "U$13") (pin "OUT+") (pinfunction "OUT+_OUT+") (pintype "bidirectional"))
      (node (ref "U$16") (pin "IP") (pinfunction "IP_IP") (pintype "bidirectional"))
      (node (ref "U$38") (pin "2") (pinfunction "2_2") (pintype "bidirectional"))
    )
    (net (code "187") (name "Net-(CEL1CC-C)") (class "Default")
      (node (ref "CEL1CC") (pin "K") (pinfunction "C_K") (pintype "passive"))
      (node (ref "CEL1RC") (pin "P$2") (pinfunction "2_P$2") (pintype "passive"))
    )
    (net (code "188") (name "Net-(CEL1RO-2)") (class "Default")
      (node (ref "CEL1CO") (pin "A") (pinfunction "A_A") (pintype "passive"))
      (node (ref "CEL1RO") (pin "P$2") (pinfunction "2_P$2") (pintype "passive"))
    )
    (net (code "189") (name "Net-(CEL2CC-C)") (class "Default")
      (node (ref "CEL2CC") (pin "K") (pinfunction "C_K") (pintype "passive"))
      (node (ref "CEL2RC") (pin "P$2") (pinfunction "2_P$2") (pintype "passive"))
    )
    (net (code "190") (name "Net-(CEL2RO-2)") (class "Default")
      (node (ref "CEL2CO") (pin "A") (pinfunction "A_A") (pintype "passive"))
      (node (ref "CEL2RO") (pin "P$2") (pinfunction "2_P$2") (pintype "passive"))
    )
    (net (code "191") (name "Net-(CEL3CC-C)") (class "Default")
      (node (ref "CEL3CC") (pin "K") (pinfunction "C_K") (pintype "passive"))
      (node (ref "CEL3RC") (pin "P$2") (pinfunction "2_P$2") (pintype "passive"))
    )
    (net (code "192") (name "Net-(CEL3RO-2)") (class "Default")
      (node (ref "CEL3CO") (pin "A") (pinfunction "A_A") (pintype "passive"))
      (node (ref "CEL3RO") (pin "P$2") (pinfunction "2_P$2") (pintype "passive"))
    )
    (net (code "193") (name "Net-(EM_SW-Pad1)") (class "Default")
      (node (ref "EM_SW") (pin "1") (pinfunction "1_1") (pintype "bidirectional"))
      (node (ref "U$33") (pin "1") (pinfunction "1_1") (pintype "bidirectional"))
    )
    (net (code "194") (name "Net-(FUSE-PadOUT)") (class "Default")
      (node (ref "FUSE") (pin "OUT") (pinfunction "OUT_OUT") (pintype "bidirectional"))
      (node (ref "U$32") (pin "IP") (pinfunction "IP_IP") (pintype "bidirectional"))
    )
    (net (code "195") (name "Net-(G_P2-PadS)") (class "Default")
      (node (ref "G_P2") (pin "S") (pinfunction "S_S") (pintype "passive"))
      (node (ref "U$2") (pin "VCON") (pinfunction "VCON_VCON") (pintype "bidirectional"))
    )
    (net (code "196") (name "Net-(IC8-ANODE_1)") (class "Default")
      (node (ref "IC8") (pin "1") (pinfunction "ANODE_1_1") (pintype "bidirectional"))
      (node (ref "R32") (pin "P$1") (pinfunction "1_P$1") (pintype "passive"))
    )
    (net (code "197") (name "Net-(IC8-ANODE_2)") (class "Default")
      (node (ref "IC8") (pin "3") (pinfunction "ANODE_2_3") (pintype "bidirectional"))
      (node (ref "R18") (pin "P$1") (pinfunction "1_P$1") (pintype "passive"))
    )
    (net (code "198") (name "Net-(IC8-ANODE_3)") (class "Default")
      (node (ref "IC8") (pin "5") (pinfunction "ANODE_3_5") (pintype "bidirectional"))
      (node (ref "R19") (pin "P$1") (pinfunction "1_P$1") (pintype "passive"))
    )
    (net (code "199") (name "Net-(IC8-ANODE_4)") (class "Default")
      (node (ref "IC8") (pin "7") (pinfunction "ANODE_4_7") (pintype "bidirectional"))
      (node (ref "R20") (pin "P$1") (pinfunction "1_P$1") (pintype "passive"))
    )
    (net (code "200") (name "Net-(IC8-COLLECTOR_1)") (class "Default")
      (node (ref "10K") (pin "2") (pinfunction "2_2") (pintype "passive"))
      (node (ref "IC8") (pin "10") (pinfunction "COLLECTOR_1_10") (pintype "bidirectional"))
      (node (ref "TR16") (pin "2") (pinfunction "B_2") (pintype "passive"))
    )
    (net (code "201") (name "Net-(IC8-COLLECTOR_2)") (class "Default")
      (node (ref "10K") (pin "4") (pinfunction "4_4") (pintype "passive"))
      (node (ref "IC8") (pin "12") (pinfunction "COLLECTOR_2_12") (pintype "bidirectional"))
      (node (ref "TR15") (pin "2") (pinfunction "B_2") (pintype "passive"))
    )
    (net (code "202") (name "Net-(IC8-COLLECTOR_3)") (class "Default")
      (node (ref "10K") (pin "6") (pinfunction "6_6") (pintype "passive"))
      (node (ref "IC8") (pin "14") (pinfunction "COLLECTOR_3_14") (pintype "bidirectional"))
      (node (ref "TR14") (pin "2") (pinfunction "B_2") (pintype "passive"))
    )
    (net (code "203") (name "Net-(IC9-ANODE_1)") (class "Default")
      (node (ref "IC9") (pin "1") (pinfunction "ANODE_1_1") (pintype "bidirectional"))
      (node (ref "R21") (pin "P$1") (pinfunction "1_P$1") (pintype "passive"))
    )
    (net (code "204") (name "Net-(IC9-ANODE_2)") (class "Default")
      (node (ref "IC9") (pin "3") (pinfunction "ANODE_2_3") (pintype "bidirectional"))
      (node (ref "R22") (pin "P$1") (pinfunction "1_P$1") (pintype "passive"))
    )
    (net (code "205") (name "Net-(IC9-ANODE_3)") (class "Default")
      (node (ref "IC9") (pin "5") (pinfunction "ANODE_3_5") (pintype "bidirectional"))
      (node (ref "R23") (pin "P$1") (pinfunction "1_P$1") (pintype "passive"))
    )
    (net (code "206") (name "Net-(IC9-ANODE_4)") (class "Default")
      (node (ref "IC9") (pin "7") (pinfunction "ANODE_4_7") (pintype "bidirectional"))
      (node (ref "R24") (pin "P$1") (pinfunction "1_P$1") (pintype "passive"))
    )
    (net (code "207") (name "Net-(IC9-COLLECTOR_1)") (class "Default")
      (node (ref "IC9") (pin "10") (pinfunction "COLLECTOR_1_10") (pintype "bidirectional"))
      (node (ref "RN6") (pin "2") (pinfunction "2_2") (pintype "passive"))
      (node (ref "TR20") (pin "2") (pinfunction "B_2") (pintype "passive"))
    )
    (net (code "208") (name "Net-(IC9-COLLECTOR_2)") (class "Default")
      (node (ref "IC9") (pin "12") (pinfunction "COLLECTOR_2_12") (pintype "bidirectional"))
      (node (ref "RN6") (pin "4") (pinfunction "4_4") (pintype "passive"))
      (node (ref "TR19") (pin "2") (pinfunction "B_2") (pintype "passive"))
    )
    (net (code "209") (name "Net-(IC9-COLLECTOR_3)") (class "Default")
      (node (ref "IC9") (pin "14") (pinfunction "COLLECTOR_3_14") (pintype "bidirectional"))
      (node (ref "RN6") (pin "6") (pinfunction "6_6") (pintype "passive"))
      (node (ref "TR18") (pin "2") (pinfunction "B_2") (pintype "passive"))
    )
    (net (code "210") (name "Net-(IC9-COLLECTOR_4)") (class "Default")
      (node (ref "IC9") (pin "16") (pinfunction "COLLECTOR_4_16") (pintype "bidirectional"))
      (node (ref "RN6") (pin "8") (pinfunction "8_8") (pintype "passive"))
      (node (ref "TR17") (pin "2") (pinfunction "B_2") (pintype "passive"))
    )
    (net (code "211") (name "Net-(IC10-ANODE_1)") (class "Default")
      (node (ref "IC10") (pin "1") (pinfunction "ANODE_1_1") (pintype "bidirectional"))
      (node (ref "R25") (pin "P$1") (pinfunction "1_P$1") (pintype "passive"))
    )
    (net (code "212") (name "Net-(IC10-ANODE_2)") (class "Default")
      (node (ref "IC10") (pin "3") (pinfunction "ANODE_2_3") (pintype "bidirectional"))
      (node (ref "R26") (pin "P$1") (pinfunction "1_P$1") (pintype "passive"))
    )
    (net (code "213") (name "Net-(IC10-ANODE_3)") (class "Default")
      (node (ref "IC10") (pin "5") (pinfunction "ANODE_3_5") (pintype "bidirectional"))
      (node (ref "R27") (pin "P$1") (pinfunction "1_P$1") (pintype "passive"))
    )
    (net (code "214") (name "Net-(IC10-ANODE_4)") (class "Default")
      (node (ref "IC10") (pin "7") (pinfunction "ANODE_4_7") (pintype "bidirectional"))
      (node (ref "R28") (pin "P$1") (pinfunction "1_P$1") (pintype "passive"))
    )
    (net (code "215") (name "Net-(IC10-COLLECTOR_1)") (class "Default")
      (node (ref "IC10") (pin "10") (pinfunction "COLLECTOR_1_10") (pintype "bidirectional"))
      (node (ref "RN7") (pin "2") (pinfunction "2_2") (pintype "passive"))
      (node (ref "TR24") (pin "2") (pinfunction "B_2") (pintype "passive"))
    )
    (net (code "216") (name "Net-(IC10-COLLECTOR_2)") (class "Default")
      (node (ref "IC10") (pin "12") (pinfunction "COLLECTOR_2_12") (pintype "bidirectional"))
      (node (ref "RN7") (pin "4") (pinfunction "4_4") (pintype "passive"))
      (node (ref "TR23") (pin "2") (pinfunction "B_2") (pintype "passive"))
    )
    (net (code "217") (name "Net-(IC10-COLLECTOR_3)") (class "Default")
      (node (ref "IC10") (pin "14") (pinfunction "COLLECTOR_3_14") (pintype "bidirectional"))
      (node (ref "RN7") (pin "6") (pinfunction "6_6") (pintype "passive"))
      (node (ref "TR22") (pin "2") (pinfunction "B_2") (pintype "passive"))
    )
    (net (code "218") (name "Net-(IC10-COLLECTOR_4)") (class "Default")
      (node (ref "IC10") (pin "16") (pinfunction "COLLECTOR_4_16") (pintype "bidirectional"))
      (node (ref "RN7") (pin "8") (pinfunction "8_8") (pintype "passive"))
      (node (ref "TR21") (pin "2") (pinfunction "B_2") (pintype "passive"))
    )
    (net (code "219") (name "Net-(IL1-C)") (class "Default")
      (node (ref "IL1") (pin "K") (pinfunction "C_K") (pintype "passive"))
      (node (ref "IRL1") (pin "P$2") (pinfunction "2_P$2") (pintype "passive"))
    )
    (net (code "220") (name "Net-(IL2-C)") (class "Default")
      (node (ref "IL2") (pin "K") (pinfunction "C_K") (pintype "passive"))
      (node (ref "IRL2") (pin "P$2") (pinfunction "2_P$2") (pintype "passive"))
    )
    (net (code "221") (name "Net-(IL3-C)") (class "Default")
      (node (ref "IL3") (pin "K") (pinfunction "C_K") (pintype "passive"))
      (node (ref "IRL3") (pin "P$2") (pinfunction "2_P$2") (pintype "passive"))
    )
    (net (code "222") (name "Net-(IRH1-2)") (class "Default")
      (node (ref "IH1") (pin "A") (pinfunction "A_A") (pintype "passive"))
      (node (ref "IRH1") (pin "P$2") (pinfunction "2_P$2") (pintype "passive"))
    )
    (net (code "223") (name "Net-(IRH2-2)") (class "Default")
      (node (ref "IH2") (pin "A") (pinfunction "A_A") (pintype "passive"))
      (node (ref "IRH2") (pin "P$2") (pinfunction "2_P$2") (pintype "passive"))
    )
    (net (code "224") (name "Net-(IRH3-2)") (class "Default")
      (node (ref "IH3") (pin "A") (pinfunction "A_A") (pintype "passive"))
      (node (ref "IRH3") (pin "P$2") (pinfunction "2_P$2") (pintype "passive"))
    )
    (net (code "225") (name "Net-(L1-PadA)") (class "Default")
      (node (ref "L1") (pin "A") (pinfunction "A_A") (pintype "passive"))
      (node (ref "RN1") (pin "2") (pinfunction "2_2") (pintype "passive"))
    )
    (net (code "226") (name "Net-(L2-PadA)") (class "Default")
      (node (ref "L2") (pin "A") (pinfunction "A_A") (pintype "passive"))
      (node (ref "RN1") (pin "3") (pinfunction "3_3") (pintype "passive"))
    )
    (net (code "227") (name "Net-(L3-PadA)") (class "Default")
      (node (ref "L3") (pin "A") (pinfunction "A_A") (pintype "passive"))
      (node (ref "RN1") (pin "4") (pinfunction "4_4") (pintype "passive"))
    )
    (net (code "228") (name "Net-(L4-PadA)") (class "Default")
      (node (ref "L4") (pin "A") (pinfunction "A_A") (pintype "passive"))
      (node (ref "RN1") (pin "5") (pinfunction "5_5") (pintype "passive"))
    )
    (net (code "229") (name "Net-(L5-PadA)") (class "Default")
      (node (ref "L5") (pin "A") (pinfunction "A_A") (pintype "passive"))
      (node (ref "RN1") (pin "6") (pinfunction "6_6") (pintype "passive"))
    )
    (net (code "230") (name "Net-(L6-PadA)") (class "Default")
      (node (ref "L6") (pin "A") (pinfunction "A_A") (pintype "passive"))
      (node (ref "RN1") (pin "7") (pinfunction "7_7") (pintype "passive"))
    )
    (net (code "231") (name "Net-(L7-PadA)") (class "Default")
      (node (ref "L7") (pin "A") (pinfunction "A_A") (pintype "passive"))
      (node (ref "RN1") (pin "8") (pinfunction "8_8") (pintype "passive"))
    )
    (net (code "232") (name "Net-(R4-1)") (class "Default")
      (node (ref "R4") (pin "P$1") (pinfunction "1_P$1") (pintype "passive"))
      (node (ref "U$44") (pin "3") (pinfunction "VO_3") (pintype "bidirectional"))
    )
    (net (code "233") (name "Net-(R5-2)") (class "Default")
      (node (ref "R5") (pin "P$2") (pinfunction "2_P$2") (pintype "passive"))
      (node (ref "U$20") (pin "PROG") (pinfunction "PROG_PROG") (pintype "bidirectional"))
    )
    (net (code "234") (name "Net-(R6-2)") (class "Default")
      (node (ref "R6") (pin "P$2") (pinfunction "2_P$2") (pintype "passive"))
      (node (ref "U$19") (pin "PROG") (pinfunction "PROG_PROG") (pintype "bidirectional"))
    )
    (net (code "235") (name "Net-(R7-2)") (class "Default")
      (node (ref "R7") (pin "P$2") (pinfunction "2_P$2") (pintype "passive"))
      (node (ref "U$18") (pin "PROG") (pinfunction "PROG_PROG") (pintype "bidirectional"))
    )
    (net (code "236") (name "Net-(R10-1)") (class "Default")
      (node (ref "R10") (pin "P$1") (pinfunction "1_P$1") (pintype "passive"))
      (node (ref "U$46") (pin "3") (pinfunction "VO_3") (pintype "bidirectional"))
    )
    (net (code "237") (name "Net-(R11-1)") (class "Default")
      (node (ref "R11") (pin "P$1") (pinfunction "1_P$1") (pintype "passive"))
      (node (ref "U$47") (pin "3") (pinfunction "VO_3") (pintype "bidirectional"))
    )
    (net (code "238") (name "Net-(R17-2)") (class "Default")
      (node (ref "R17") (pin "P$2") (pinfunction "2_P$2") (pintype "passive"))
      (node (ref "U$2") (pin "L+") (pinfunction "L+_L+") (pintype "bidirectional"))
    )
    (net (code "239") (name "Net-(R33-2)") (class "Default")
      (node (ref "R33") (pin "P$2") (pinfunction "2_P$2") (pintype "passive"))
      (node (ref "R34") (pin "P$2") (pinfunction "2_P$2") (pintype "passive"))
      (node (ref "U$1") (pin "1") (pinfunction "1_1") (pintype "bidirectional"))
    )
    (net (code "240") (name "Net-(R35-2)") (class "Default")
      (node (ref "R35") (pin "P$2") (pinfunction "2_P$2") (pintype "passive"))
      (node (ref "R36") (pin "P$2") (pinfunction "2_P$2") (pintype "passive"))
      (node (ref "U$40") (pin "1") (pinfunction "1_1") (pintype "bidirectional"))
    )
    (net (code "241") (name "Net-(R37-2)") (class "Default")
      (node (ref "R37") (pin "P$2") (pinfunction "2_P$2") (pintype "passive"))
      (node (ref "R38") (pin "P$2") (pinfunction "2_P$2") (pintype "passive"))
      (node (ref "U$41") (pin "1") (pinfunction "1_1") (pintype "bidirectional"))
    )
    (net (code "242") (name "Net-(U$3-Pad5V)") (class "Default")
      (node (ref "U$3") (pin "5V") (pinfunction "5V_5V") (pintype "bidirectional"))
      (node (ref "U$3") (pin "EN") (pinfunction "EN_EN") (pintype "bidirectional"))
    )
    (net (code "243") (name "Net-(U$6-Pad5V)") (class "Default")
      (node (ref "U$6") (pin "5V") (pinfunction "5V_5V") (pintype "bidirectional"))
      (node (ref "U$6") (pin "EN") (pinfunction "EN_EN") (pintype "bidirectional"))
    )
    (net (code "244") (name "Net-(U$9-Pad5V)") (class "Default")
      (node (ref "U$9") (pin "5V") (pinfunction "5V_5V") (pintype "bidirectional"))
      (node (ref "U$9") (pin "EN") (pinfunction "EN_EN") (pintype "bidirectional"))
    )
    (net (code "245") (name "Net-(U$15-PadO1)") (class "Default")
      (node (ref "U$15") (pin "O1") (pinfunction "O1_O1") (pintype "bidirectional"))
      (node (ref "V-P") (pin "3") (pinfunction "3_3") (pintype "bidirectional"))
    )
    (net (code "246") (name "Net-(U$44-VIN)") (class "Default")
      (node (ref "PROX1") (pin "2") (pinfunction "2_2") (pintype "bidirectional"))
      (node (ref "U$44") (pin "1") (pinfunction "VIN_1") (pintype "bidirectional"))
    )
    (net (code "247") (name "Net-(U$46-VIN)") (class "Default")
      (node (ref "PROX2") (pin "2") (pinfunction "2_2") (pintype "bidirectional"))
      (node (ref "U$46") (pin "1") (pinfunction "VIN_1") (pintype "bidirectional"))
    )
    (net (code "248") (name "Net-(U$47-VIN)") (class "Default")
      (node (ref "PROX3") (pin "2") (pinfunction "2_2") (pintype "bidirectional"))
      (node (ref "U$47") (pin "1") (pinfunction "VIN_1") (pintype "bidirectional"))
    )
    (net (code "249") (name "POS_1") (class "Default")
      (node (ref "IC2") (pin "5") (pinfunction "5_5") (pintype "passive"))
      (node (ref "PPR_R1") (pin "P$1") (pinfunction "1_P$1") (pintype "passive"))
      (node (ref "U$29") (pin "1") (pinfunction "1_1") (pintype "bidirectional"))
    )
    (net (code "250") (name "RESET") (class "Default")
      (node (ref "C2") (pin "2") (pinfunction "2_2") (pintype "passive"))
      (node (ref "CEL2RO1") (pin "P$1") (pinfunction "1_P$1") (pintype "passive"))
      (node (ref "IC3") (pin "1") (pinfunction "1_1") (pintype "passive"))
      (node (ref "MEGA_RST1") (pin "1") (pinfunction "1_1") (pintype "passive"))
    )
    (net (code "251") (name "RO1") (class "Default")
      (node (ref "REL1") (pin "OUT_1") (pinfunction "OUT_1_OUT_1") (pintype "bidirectional"))
      (node (ref "U$18") (pin "VDD") (pinfunction "VDD_VDD") (pintype "bidirectional"))
      (node (ref "U$25") (pin "2") (pinfunction "2_2") (pintype "bidirectional"))
    )
    (net (code "252") (name "RO2") (class "Default")
      (node (ref "REL2") (pin "OUT_1") (pinfunction "OUT_1_OUT_1") (pintype "bidirectional"))
      (node (ref "U$19") (pin "VDD") (pinfunction "VDD_VDD") (pintype "bidirectional"))
      (node (ref "U$26") (pin "2") (pinfunction "2_2") (pintype "bidirectional"))
    )
    (net (code "253") (name "RO3") (class "Default")
      (node (ref "REL3") (pin "OUT_1") (pinfunction "OUT_1_OUT_1") (pintype "bidirectional"))
      (node (ref "U$20") (pin "VDD") (pinfunction "VDD_VDD") (pintype "bidirectional"))
      (node (ref "U$27") (pin "2") (pinfunction "2_2") (pintype "bidirectional"))
    )
    (net (code "254") (name "RST") (class "Default")
      (node (ref "ATMEGA_2560") (pin "RST") (pinfunction "RST_RST") (pintype "bidirectional"))
      (node (ref "MEGA_RST") (pin "1") (pinfunction "1_1") (pintype "passive"))
      (node (ref "U$12") (pin "RST1") (pinfunction "RST1_RST1") (pintype "bidirectional"))
      (node (ref "U$30") (pin "C") (pinfunction "C_C") (pintype "bidirectional"))
    )
    (net (code "255") (name "RST1") (class "Default")
      (node (ref "ATMEGA_2560") (pin "RST1") (pinfunction "RST1_RST1") (pintype "bidirectional"))
      (node (ref "U$12") (pin "RST") (pinfunction "RST_RST") (pintype "bidirectional"))
    )
    (net (code "256") (name "RX0") (class "Default")
      (node (ref "ATMEGA_2560") (pin "RX0") (pinfunction "RX0_RX0") (pintype "bidirectional"))
      (node (ref "RFID1") (pin "1") (pinfunction "1_1") (pintype "bidirectional"))
      (node (ref "U$12") (pin "RX0") (pinfunction "RX_RX0") (pintype "bidirectional"))
    )
    (net (code "257") (name "RX1") (class "Default")
      (node (ref "ATMEGA_2560") (pin "RX1") (pinfunction "RX1_RX1") (pintype "bidirectional"))
      (node (ref "N-M") (pin "3") (pinfunction "3_3") (pintype "passive"))
      (node (ref "RFID2") (pin "3") (pinfunction "3_3") (pintype "bidirectional"))
      (node (ref "SW1") (pin "1") (pinfunction "1_1") (pintype "passive"))
    )
    (net (code "258") (name "RX2") (class "Default")
      (node (ref "ATMEGA_2560") (pin "RX2") (pinfunction "RX2_RX2") (pintype "bidirectional"))
      (node (ref "RFID2") (pin "5") (pinfunction "5_5") (pintype "bidirectional"))
      (node (ref "SW1") (pin "3") (pinfunction "3_3") (pintype "passive"))
    )
    (net (code "259") (name "RX3") (class "Default")
      (node (ref "ATMEGA_2560") (pin "RX3") (pinfunction "RX3_RX3") (pintype "bidirectional"))
      (node (ref "RFID2") (pin "7") (pinfunction "7_7") (pintype "bidirectional"))
      (node (ref "SW1") (pin "5") (pinfunction "5_5") (pintype "passive"))
    )
    (net (code "260") (name "RXD") (class "Default")
      (node (ref "IC3") (pin "2") (pinfunction "2_2") (pintype "passive"))
      (node (ref "JP3") (pin "3") (pinfunction "3_3") (pintype "passive"))
      (node (ref "U$52") (pin "10") (pinfunction "10_10") (pintype "bidirectional"))
    )
    (net (code "261") (name "R_3V3") (class "Default")
      (node (ref "10K") (pin "1") (pinfunction "1_1") (pintype "passive"))
      (node (ref "RASPI_PORT1") (pin "1") (pinfunction "1_1") (pintype "passive"))
      (node (ref "RASPI_PORT2") (pin "39") (pinfunction "39_39") (pintype "passive"))
    )
    (net (code "262") (name "R_3V31") (class "Default")
      (node (ref "RASPI_PORT1") (pin "17") (pinfunction "17_17") (pintype "passive"))
      (node (ref "RASPI_PORT2") (pin "23") (pinfunction "23_23") (pintype "passive"))
    )
    (net (code "263") (name "R_5V") (class "Default")
      (node (ref "RASPI_PORT1") (pin "2") (pinfunction "2_2") (pintype "passive"))
      (node (ref "RASPI_PORT2") (pin "40") (pinfunction "40_40") (pintype "passive"))
    )
    (net (code "264") (name "R_5V1") (class "Default")
      (node (ref "RASPI_PORT1") (pin "4") (pinfunction "4_4") (pintype "passive"))
      (node (ref "RASPI_PORT2") (pin "38") (pinfunction "38_38") (pintype "passive"))
    )
    (net (code "265") (name "R_GND") (class "Default")
      (node (ref "BC547") (pin "1") (pinfunction "E_1") (pintype "passive"))
      (node (ref "IC10") (pin "2") (pinfunction "CATHODE_1_2") (pintype "bidirectional"))
      (node (ref "IC10") (pin "4") (pinfunction "CATHODE_2_4") (pintype "bidirectional"))
      (node (ref "IC10") (pin "6") (pinfunction "CATHODE_3_6") (pintype "bidirectional"))
      (node (ref "IC10") (pin "8") (pinfunction "CATHODE_4_8") (pintype "bidirectional"))
      (node (ref "IC8") (pin "11") (pinfunction "EMITTER_2_11") (pintype "bidirectional"))
      (node (ref "IC8") (pin "13") (pinfunction "EMITTER_3_13") (pintype "bidirectional"))
      (node (ref "IC8") (pin "15") (pinfunction "EMITTER_4_15") (pintype "bidirectional"))
      (node (ref "IC8") (pin "9") (pinfunction "EMITTER_1_9") (pintype "bidirectional"))
      (node (ref "IC9") (pin "2") (pinfunction "CATHODE_1_2") (pintype "bidirectional"))
      (node (ref "IC9") (pin "4") (pinfunction "CATHODE_2_4") (pintype "bidirectional"))
      (node (ref "IC9") (pin "6") (pinfunction "CATHODE_3_6") (pintype "bidirectional"))
      (node (ref "IC9") (pin "8") (pinfunction "CATHODE_4_8") (pintype "bidirectional"))
      (node (ref "OISO2") (pin "1") (pinfunction "1_1") (pintype "bidirectional"))
      (node (ref "OISO3") (pin "1") (pinfunction "1_1") (pintype "bidirectional"))
      (node (ref "OISO5") (pin "1") (pinfunction "1_1") (pintype "bidirectional"))
      (node (ref "RASPI_PORT1") (pin "9") (pinfunction "9_9") (pintype "passive"))
      (node (ref "RASPI_PORT2") (pin "31") (pinfunction "31_31") (pintype "passive"))
      (node (ref "TR14") (pin "1") (pinfunction "E_1") (pintype "passive"))
      (node (ref "TR15") (pin "1") (pinfunction "E_1") (pintype "passive"))
      (node (ref "TR16") (pin "1") (pinfunction "E_1") (pintype "passive"))
      (node (ref "U$17") (pin "2") (pinfunction "2_2") (pintype "bidirectional"))
    )
    (net (code "266") (name "R_GND1") (class "Default")
      (node (ref "RASPI_PORT1") (pin "25") (pinfunction "25_25") (pintype "passive"))
      (node (ref "RASPI_PORT2") (pin "15") (pinfunction "15_15") (pintype "passive"))
    )
    (net (code "267") (name "R_GND2") (class "Default")
      (node (ref "RASPI_PORT1") (pin "39") (pinfunction "39_39") (pintype "passive"))
      (node (ref "RASPI_PORT2") (pin "1") (pinfunction "1_1") (pintype "passive"))
    )
    (net (code "268") (name "R_GND3") (class "Default")
      (node (ref "RASPI_PORT1") (pin "34") (pinfunction "34_34") (pintype "passive"))
      (node (ref "RASPI_PORT2") (pin "8") (pinfunction "8_8") (pintype "passive"))
    )
    (net (code "269") (name "R_GND4") (class "Default")
      (node (ref "RASPI_PORT1") (pin "30") (pinfunction "30_30") (pintype "passive"))
      (node (ref "RASPI_PORT2") (pin "12") (pinfunction "12_12") (pintype "passive"))
    )
    (net (code "270") (name "R_GND5") (class "Default")
      (node (ref "RASPI_PORT1") (pin "20") (pinfunction "20_20") (pintype "passive"))
      (node (ref "RASPI_PORT2") (pin "22") (pinfunction "22_22") (pintype "passive"))
    )
    (net (code "271") (name "R_GND6") (class "Default")
      (node (ref "RASPI_PORT1") (pin "14") (pinfunction "14_14") (pintype "passive"))
      (node (ref "RASPI_PORT2") (pin "28") (pinfunction "28_28") (pintype "passive"))
    )
    (net (code "272") (name "R_GND7") (class "Default")
      (node (ref "RASPI_PORT1") (pin "6") (pinfunction "6_6") (pintype "passive"))
      (node (ref "RASPI_PORT2") (pin "36") (pinfunction "36_36") (pintype "passive"))
    )
    (net (code "273") (name "SCK") (class "Default")
      (node (ref "ATMEGA_2560") (pin "SCK") (pinfunction "SCK_SCK") (pintype "bidirectional"))
      (node (ref "U$12") (pin "SCK") (pinfunction "SC_SCK") (pintype "bidirectional"))
    )
    (net (code "274") (name "SCL") (class "Default")
      (node (ref "ATMEGA_2560") (pin "SCL") (pinfunction "SCL_SCL") (pintype "bidirectional"))
      (node (ref "RFID2") (pin "1") (pinfunction "1_1") (pintype "bidirectional"))
      (node (ref "U$10") (pin "SCL") (pinfunction "SCL_SCL") (pintype "bidirectional"))
    )
    (net (code "275") (name "SCLU") (class "Default")
      (node (ref "ATMEGA_2560") (pin "SCLU") (pinfunction "SCLU_SCLU") (pintype "bidirectional"))
      (node (ref "U$12") (pin "SCL") (pinfunction "SCL_SCL") (pintype "bidirectional"))
    )
    (net (code "276") (name "SDA") (class "Default")
      (node (ref "ATMEGA_2560") (pin "SDA") (pinfunction "SDA_SDA") (pintype "bidirectional"))
      (node (ref "RFID2") (pin "2") (pinfunction "2_2") (pintype "bidirectional"))
      (node (ref "U$10") (pin "SDA") (pinfunction "SDA_SDA") (pintype "bidirectional"))
    )
    (net (code "277") (name "SDAU") (class "Default")
      (node (ref "ATMEGA_2560") (pin "SDAU") (pinfunction "SDAU_SDAU") (pintype "bidirectional"))
      (node (ref "U$12") (pin "SDA") (pinfunction "SDA_SDA") (pintype "bidirectional"))
    )
    (net (code "278") (name "STAT_1") (class "Default")
      (node (ref "CEL1CC") (pin "A") (pinfunction "A_A") (pintype "passive"))
      (node (ref "CEL1CO") (pin "K") (pinfunction "C_K") (pintype "passive"))
      (node (ref "U$18") (pin "STAT") (pinfunction "STAT_STAT") (pintype "bidirectional"))
    )
    (net (code "279") (name "STAT_2") (class "Default")
      (node (ref "CEL2CC") (pin "A") (pinfunction "A_A") (pintype "passive"))
      (node (ref "CEL2CO") (pin "K") (pinfunction "C_K") (pintype "passive"))
      (node (ref "U$19") (pin "STAT") (pinfunction "STAT_STAT") (pintype "bidirectional"))
    )
    (net (code "280") (name "STAT_3") (class "Default")
      (node (ref "CEL3CC") (pin "A") (pinfunction "A_A") (pintype "passive"))
      (node (ref "CEL3CO") (pin "K") (pinfunction "C_K") (pintype "passive"))
      (node (ref "U$20") (pin "STAT") (pinfunction "STAT_STAT") (pintype "bidirectional"))
    )
    (net (code "281") (name "SUPP+") (class "Default")
      (node (ref "BAT_SUPP") (pin "2") (pinfunction "2_2") (pintype "bidirectional"))
      (node (ref "FUSE") (pin "IN") (pinfunction "IN_IN") (pintype "bidirectional"))
    )
    (net (code "282") (name "S_A0") (class "Default")
      (node (ref "IC3") (pin "23") (pinfunction "23_23") (pintype "passive"))
      (node (ref "U$53") (pin "6") (pinfunction "6_6") (pintype "bidirectional"))
    )
    (net (code "283") (name "S_A1") (class "Default")
      (node (ref "IC3") (pin "24") (pinfunction "24_24") (pintype "passive"))
      (node (ref "U$53") (pin "5") (pinfunction "5_5") (pintype "bidirectional"))
    )
    (net (code "284") (name "S_A2") (class "Default")
      (node (ref "IC3") (pin "25") (pinfunction "25_25") (pintype "passive"))
      (node (ref "U$53") (pin "4") (pinfunction "4_4") (pintype "bidirectional"))
    )
    (net (code "285") (name "S_A3") (class "Default")
      (node (ref "IC3") (pin "26") (pinfunction "26_26") (pintype "passive"))
      (node (ref "U$53") (pin "3") (pinfunction "3_3") (pintype "bidirectional"))
    )
    (net (code "286") (name "S_A4") (class "Default")
      (node (ref "IC3") (pin "27") (pinfunction "27_27") (pintype "passive"))
      (node (ref "U$53") (pin "2") (pinfunction "2_2") (pintype "bidirectional"))
    )
    (net (code "287") (name "S_A5") (class "Default")
      (node (ref "IC3") (pin "28") (pinfunction "28_28") (pintype "passive"))
      (node (ref "U$53") (pin "1") (pinfunction "1_1") (pintype "bidirectional"))
    )
    (net (code "288") (name "S_AREF") (class "Default")
      (node (ref "C8") (pin "1") (pinfunction "1_1") (pintype "passive"))
      (node (ref "IC3") (pin "21") (pinfunction "21_21") (pintype "passive"))
    )
    (net (code "289") (name "S_D2") (class "Default")
      (node (ref "IC3") (pin "4") (pinfunction "4_4") (pintype "passive"))
      (node (ref "U$52") (pin "8") (pinfunction "8_8") (pintype "bidirectional"))
    )
    (net (code "290") (name "S_D3") (class "Default")
      (node (ref "IC3") (pin "5") (pinfunction "5_5") (pintype "passive"))
      (node (ref "U$52") (pin "7") (pinfunction "7_7") (pintype "bidirectional"))
    )
    (net (code "291") (name "S_D4") (class "Default")
      (node (ref "IC3") (pin "6") (pinfunction "6_6") (pintype "passive"))
      (node (ref "U$52") (pin "6") (pinfunction "6_6") (pintype "bidirectional"))
    )
    (net (code "292") (name "S_D5") (class "Default")
      (node (ref "IC3") (pin "11") (pinfunction "11_11") (pintype "passive"))
      (node (ref "U$52") (pin "5") (pinfunction "5_5") (pintype "bidirectional"))
    )
    (net (code "293") (name "S_D6") (class "Default")
      (node (ref "IC3") (pin "12") (pinfunction "12_12") (pintype "passive"))
      (node (ref "U$52") (pin "4") (pinfunction "4_4") (pintype "bidirectional"))
    )
    (net (code "294") (name "S_D7") (class "Default")
      (node (ref "IC3") (pin "13") (pinfunction "13_13") (pintype "passive"))
      (node (ref "U$52") (pin "3") (pinfunction "3_3") (pintype "bidirectional"))
    )
    (net (code "295") (name "S_D8") (class "Default")
      (node (ref "IC3") (pin "14") (pinfunction "14_14") (pintype "passive"))
      (node (ref "U$52") (pin "2") (pinfunction "2_2") (pintype "bidirectional"))
    )
    (net (code "296") (name "S_D9") (class "Default")
      (node (ref "IC3") (pin "15") (pinfunction "15_15") (pintype "passive"))
      (node (ref "U$52") (pin "1") (pinfunction "1_1") (pintype "bidirectional"))
    )
    (net (code "297") (name "S_D10") (class "Default")
      (node (ref "IC3") (pin "16") (pinfunction "16_16") (pintype "passive"))
      (node (ref "U$53") (pin "10") (pinfunction "10_10") (pintype "bidirectional"))
    )
    (net (code "298") (name "S_D11") (class "Default")
      (node (ref "IC3") (pin "17") (pinfunction "17_17") (pintype "passive"))
      (node (ref "U$53") (pin "9") (pinfunction "9_9") (pintype "bidirectional"))
    )
    (net (code "299") (name "S_D12") (class "Default")
      (node (ref "IC3") (pin "18") (pinfunction "18_18") (pintype "passive"))
      (node (ref "U$53") (pin "8") (pinfunction "8_8") (pintype "bidirectional"))
    )
    (net (code "300") (name "S_D13") (class "Default")
      (node (ref "IC3") (pin "19") (pinfunction "19_19") (pintype "passive"))
      (node (ref "U$53") (pin "7") (pinfunction "7_7") (pintype "bidirectional"))
    )
    (net (code "301") (name "S_GND") (class "Default")
      (node (ref "BAT6") (pin "2") (pinfunction "2_2") (pintype "bidirectional"))
      (node (ref "C5") (pin "2") (pinfunction "2_2") (pintype "passive"))
      (node (ref "C6") (pin "1") (pinfunction "1_1") (pintype "passive"))
      (node (ref "C7") (pin "1") (pinfunction "1_1") (pintype "passive"))
      (node (ref "C8") (pin "2") (pinfunction "2_2") (pintype "passive"))
      (node (ref "IC3") (pin "22") (pinfunction "22_22") (pintype "passive"))
      (node (ref "IC3") (pin "8") (pinfunction "8_8") (pintype "passive"))
      (node (ref "JP3") (pin "6") (pinfunction "6_6") (pintype "passive"))
      (node (ref "MEGA_RST1") (pin "3") (pinfunction "2_3") (pintype "passive"))
      (node (ref "U$51") (pin "2") (pinfunction "2_2") (pintype "bidirectional"))
    )
    (net (code "302") (name "TX0") (class "Default")
      (node (ref "ATMEGA_2560") (pin "TX0") (pinfunction "TX0_TX0") (pintype "bidirectional"))
      (node (ref "RFID1") (pin "2") (pinfunction "2_2") (pintype "bidirectional"))
      (node (ref "U$12") (pin "TX0") (pinfunction "TX_TX0") (pintype "bidirectional"))
    )
    (net (code "303") (name "TX1") (class "Default")
      (node (ref "ATMEGA_2560") (pin "TX1") (pinfunction "TX1_TX1") (pintype "bidirectional"))
      (node (ref "N-M") (pin "4") (pinfunction "4_4") (pintype "passive"))
      (node (ref "RFID2") (pin "4") (pinfunction "4_4") (pintype "bidirectional"))
      (node (ref "SW1") (pin "2") (pinfunction "2_2") (pintype "passive"))
    )
    (net (code "304") (name "TX2") (class "Default")
      (node (ref "ATMEGA_2560") (pin "TX2") (pinfunction "TX2_TX2") (pintype "bidirectional"))
      (node (ref "RFID2") (pin "6") (pinfunction "6_6") (pintype "bidirectional"))
      (node (ref "SW1") (pin "4") (pinfunction "4_4") (pintype "passive"))
    )
    (net (code "305") (name "TX3") (class "Default")
      (node (ref "ATMEGA_2560") (pin "TX3") (pinfunction "TX3_TX3") (pintype "bidirectional"))
      (node (ref "RFID2") (pin "8") (pinfunction "8_8") (pintype "bidirectional"))
      (node (ref "SW1") (pin "6") (pinfunction "6_6") (pintype "passive"))
    )
    (net (code "306") (name "TXD") (class "Default")
      (node (ref "IC3") (pin "3") (pinfunction "3_3") (pintype "passive"))
      (node (ref "JP3") (pin "2") (pinfunction "2_2") (pintype "passive"))
      (node (ref "U$52") (pin "9") (pinfunction "9_9") (pintype "bidirectional"))
    )
    (net (code "307") (name "U1") (class "Default")
      (node (ref "IC1") (pin "16") (pinfunction "16_16") (pintype "passive"))
      (node (ref "L1") (pin "K") (pinfunction "C_K") (pintype "passive"))
      (node (ref "REL1") (pin "-") (pinfunction "-_-") (pintype "bidirectional"))
      (node (ref "ULN_SIG") (pin "3") (pinfunction "3_3") (pintype "bidirectional"))
    )
    (net (code "308") (name "U2") (class "Default")
      (node (ref "IC1") (pin "15") (pinfunction "15_15") (pintype "passive"))
      (node (ref "L2") (pin "K") (pinfunction "C_K") (pintype "passive"))
      (node (ref "REL2") (pin "-") (pinfunction "-_-") (pintype "bidirectional"))
      (node (ref "ULN_SIG") (pin "2") (pinfunction "2_2") (pintype "bidirectional"))
    )
    (net (code "309") (name "U3") (class "Default")
      (node (ref "IC1") (pin "14") (pinfunction "14_14") (pintype "passive"))
      (node (ref "L3") (pin "K") (pinfunction "C_K") (pintype "passive"))
      (node (ref "REL3") (pin "-") (pinfunction "-_-") (pintype "bidirectional"))
      (node (ref "ULN_SIG") (pin "1") (pinfunction "1_1") (pintype "bidirectional"))
    )
    (net (code "310") (name "U4") (class "Default")
      (node (ref "IC1") (pin "13") (pinfunction "13_13") (pintype "passive"))
      (node (ref "L4") (pin "K") (pinfunction "C_K") (pintype "passive"))
      (node (ref "U45") (pin "2") (pinfunction "2_2") (pintype "bidirectional"))
    )
    (net (code "311") (name "U5") (class "Default")
      (node (ref "IC1") (pin "12") (pinfunction "12_12") (pintype "passive"))
      (node (ref "L5") (pin "K") (pinfunction "C_K") (pintype "passive"))
      (node (ref "U45") (pin "1") (pinfunction "1_1") (pintype "bidirectional"))
    )
    (net (code "312") (name "U6") (class "Default")
      (node (ref "IC1") (pin "11") (pinfunction "11_11") (pintype "passive"))
      (node (ref "L6") (pin "K") (pinfunction "C_K") (pintype "passive"))
      (node (ref "U67") (pin "2") (pinfunction "2_2") (pintype "bidirectional"))
    )
    (net (code "313") (name "U7") (class "Default")
      (node (ref "IC1") (pin "10") (pinfunction "10_10") (pintype "passive"))
      (node (ref "L7") (pin "K") (pinfunction "C_K") (pintype "passive"))
      (node (ref "U67") (pin "1") (pinfunction "1_1") (pintype "bidirectional"))
    )
    (net (code "314") (name "VBAT_1") (class "Default")
      (node (ref "BALANCE") (pin "4") (pinfunction "4_4") (pintype "bidirectional"))
      (node (ref "BALANCE1") (pin "4") (pinfunction "4_4") (pintype "bidirectional"))
      (node (ref "R33") (pin "P$1") (pinfunction "1_P$1") (pintype "passive"))
      (node (ref "U$18") (pin "VBAT") (pinfunction "VBAT_VBAT") (pintype "bidirectional"))
      (node (ref "U$21") (pin "2") (pinfunction "2_2") (pintype "bidirectional"))
    )
    (net (code "315") (name "VBAT_2") (class "Default")
      (node (ref "BALANCE") (pin "3") (pinfunction "3_3") (pintype "bidirectional"))
      (node (ref "BALANCE1") (pin "3") (pinfunction "3_3") (pintype "bidirectional"))
      (node (ref "R35") (pin "P$1") (pinfunction "1_P$1") (pintype "passive"))
      (node (ref "U$19") (pin "VBAT") (pinfunction "VBAT_VBAT") (pintype "bidirectional"))
      (node (ref "U$21") (pin "1") (pinfunction "1_1") (pintype "bidirectional"))
      (node (ref "U$22") (pin "2") (pinfunction "2_2") (pintype "bidirectional"))
    )
    (net (code "316") (name "VBAT_3") (class "Default")
      (node (ref "BALANCE") (pin "2") (pinfunction "2_2") (pintype "bidirectional"))
      (node (ref "BALANCE1") (pin "2") (pinfunction "2_2") (pintype "bidirectional"))
      (node (ref "R37") (pin "P$1") (pinfunction "1_P$1") (pintype "passive"))
      (node (ref "U$20") (pin "VBAT") (pinfunction "VBAT_VBAT") (pintype "bidirectional"))
      (node (ref "U$22") (pin "1") (pinfunction "1_1") (pintype "bidirectional"))
      (node (ref "U$23") (pin "2") (pinfunction "2_2") (pintype "bidirectional"))
    )
    (net (code "317") (name "V_SUPP") (class "Default")
      (node (ref "BAT1") (pin "1") (pinfunction "1_1") (pintype "bidirectional"))
      (node (ref "IC1") (pin "9") (pinfunction "9_9") (pintype "passive"))
      (node (ref "IC2") (pin "8") (pinfunction "8_8") (pintype "passive"))
      (node (ref "LSA_2") (pin "9") (pinfunction "9_9") (pintype "passive"))
      (node (ref "PROX1") (pin "3") (pinfunction "3_3") (pintype "bidirectional"))
      (node (ref "PROX2") (pin "3") (pinfunction "3_3") (pintype "bidirectional"))
      (node (ref "PROX3") (pin "3") (pinfunction "3_3") (pintype "bidirectional"))
      (node (ref "REL1") (pin "+") (pinfunction "+_+") (pintype "bidirectional"))
      (node (ref "REL2") (pin "+") (pinfunction "+_+") (pintype "bidirectional"))
      (node (ref "REL3") (pin "+") (pinfunction "+_+") (pintype "bidirectional"))
      (node (ref "U$13") (pin "IN+") (pinfunction "IN+_IN+") (pintype "bidirectional"))
      (node (ref "U$3") (pin "IN+") (pinfunction "IN+_IN+") (pintype "bidirectional"))
      (node (ref "U$32") (pin "O1") (pinfunction "O1_O1") (pintype "bidirectional"))
      (node (ref "U$6") (pin "IN+") (pinfunction "IN+_IN+") (pintype "bidirectional"))
      (node (ref "U$7") (pin "IN+") (pinfunction "IN+_IN+") (pintype "bidirectional"))
      (node (ref "U$8") (pin "IN+") (pinfunction "IN+_IN+") (pintype "bidirectional"))
      (node (ref "U$9") (pin "IN+") (pinfunction "IN+_IN+") (pintype "bidirectional"))
    )
    (net (code "318") (name "XTAL1") (class "Default")
      (node (ref "C6") (pin "2") (pinfunction "2_2") (pintype "passive"))
      (node (ref "IC3") (pin "9") (pinfunction "9_9") (pintype "passive"))
      (node (ref "Q3") (pin "2") (pinfunction "2_2") (pintype "passive"))
    )
    (net (code "319") (name "XTAL2") (class "Default")
      (node (ref "C7") (pin "2") (pinfunction "2_2") (pintype "passive"))
      (node (ref "IC3") (pin "10") (pinfunction "10_10") (pintype "passive"))
      (node (ref "Q3") (pin "1") (pinfunction "1_1") (pintype "passive"))
    )
    (net (code "320") (name "unconnected-(ATMEGA_2560-Pad5V1)") (class "Default")
      (node (ref "ATMEGA_2560") (pin "5V1") (pinfunction "5V1_5V1") (pintype "bidirectional"))
    )
    (net (code "321") (name "unconnected-(ATMEGA_2560-Pad5V2)") (class "Default")
      (node (ref "ATMEGA_2560") (pin "5V2") (pinfunction "5V2_5V2") (pintype "bidirectional"))
    )
    (net (code "322") (name "unconnected-(ATMEGA_2560-PadGD3)") (class "Default")
      (node (ref "ATMEGA_2560") (pin "GD3") (pinfunction "GD3_GD3") (pintype "bidirectional"))
    )
    (net (code "323") (name "unconnected-(ATMEGA_2560-PadGD4)") (class "Default")
      (node (ref "ATMEGA_2560") (pin "GD4") (pinfunction "GD4_GD4") (pintype "bidirectional"))
    )
    (net (code "324") (name "unconnected-(C_GND-Pad3)") (class "Default")
      (node (ref "C_GND") (pin "3") (pinfunction "3_3") (pintype "bidirectional"))
    )
    (net (code "325") (name "unconnected-(IC2-Pad1)") (class "Default")
      (node (ref "IC2") (pin "1") (pinfunction "1_1") (pintype "passive"))
    )
    (net (code "326") (name "unconnected-(IC2-Pad2)") (class "Default")
      (node (ref "IC2") (pin "2") (pinfunction "2_2") (pintype "passive"))
    )
    (net (code "327") (name "unconnected-(IC2-Pad3)") (class "Default")
      (node (ref "IC2") (pin "3") (pinfunction "3_3") (pintype "passive"))
    )
    (net (code "328") (name "unconnected-(JP3-Pad5)") (class "Default")
      (node (ref "JP3") (pin "5") (pinfunction "5_5") (pintype "passive"))
    )
    (net (code "329") (name "unconnected-(LSA_2-Pad1)") (class "Default")
      (node (ref "LSA_2") (pin "1") (pinfunction "1_1") (pintype "passive"))
    )
    (net (code "330") (name "unconnected-(LSA_2-Pad2)") (class "Default")
      (node (ref "LSA_2") (pin "2") (pinfunction "2_2") (pintype "passive"))
    )
    (net (code "331") (name "unconnected-(LSA_2-Pad3)") (class "Default")
      (node (ref "LSA_2") (pin "3") (pinfunction "3_3") (pintype "passive"))
    )
    (net (code "332") (name "unconnected-(LSA_2-Pad6)") (class "Default")
      (node (ref "LSA_2") (pin "6") (pinfunction "6_6") (pintype "passive"))
    )
    (net (code "333") (name "unconnected-(LSA_2-Pad7)") (class "Default")
      (node (ref "LSA_2") (pin "7") (pinfunction "7_7") (pintype "passive"))
    )
    (net (code "334") (name "unconnected-(LSA_2-Pad8)") (class "Default")
      (node (ref "LSA_2") (pin "8") (pinfunction "8_8") (pintype "passive"))
    )
    (net (code "335") (name "unconnected-(REL1-PadOUT_2)") (class "Default")
      (node (ref "REL1") (pin "OUT_2") (pinfunction "OUT_2_OUT_2") (pintype "bidirectional"))
    )
    (net (code "336") (name "unconnected-(REL2-PadOUT_2)") (class "Default")
      (node (ref "REL2") (pin "OUT_2") (pinfunction "OUT_2_OUT_2") (pintype "bidirectional"))
    )
    (net (code "337") (name "unconnected-(REL3-PadOUT_2)") (class "Default")
      (node (ref "REL3") (pin "OUT_2") (pinfunction "OUT_2_OUT_2") (pintype "bidirectional"))
    )
    (net (code "338") (name "unconnected-(RFID-Pad4)") (class "Default")
      (node (ref "RFID") (pin "4") (pinfunction "4_4") (pintype "bidirectional"))
    )
    (net (code "339") (name "unconnected-(U$2-PadD0)") (class "Default")
      (node (ref "U$2") (pin "D0") (pinfunction "D0_D0") (pintype "bidirectional"))
    )
    (net (code "340") (name "unconnected-(U$2-PadD1)") (class "Default")
      (node (ref "U$2") (pin "D1") (pinfunction "D1_D1") (pintype "bidirectional"))
    )
    (net (code "341") (name "unconnected-(U$2-PadD2)") (class "Default")
      (node (ref "U$2") (pin "D2") (pinfunction "D2_D2") (pintype "bidirectional"))
    )
    (net (code "342") (name "unconnected-(U$2-PadD3)") (class "Default")
      (node (ref "U$2") (pin "D3") (pinfunction "D3_D3") (pintype "bidirectional"))
    )
    (net (code "343") (name "unconnected-(U$3-PadCS)") (class "Default")
      (node (ref "U$3") (pin "CS") (pinfunction "CS_CS") (pintype "bidirectional"))
    )
    (net (code "344") (name "unconnected-(U$4-Pad3V31)") (class "Default")
      (node (ref "U$4") (pin "3V31") (pinfunction "3V31_3V31") (pintype "bidirectional"))
    )
    (net (code "345") (name "unconnected-(U$4-Pad3V32)") (class "Default")
      (node (ref "U$4") (pin "3V32") (pinfunction "3V32_3V32") (pintype "bidirectional"))
    )
    (net (code "346") (name "unconnected-(U$4-PadCLK)") (class "Default")
      (node (ref "U$4") (pin "CLK") (pinfunction "CLK_CLK") (pintype "bidirectional"))
    )
    (net (code "347") (name "unconnected-(U$4-PadCMD)") (class "Default")
      (node (ref "U$4") (pin "CMD") (pinfunction "CMD_CMD") (pintype "bidirectional"))
    )
    (net (code "348") (name "unconnected-(U$4-PadGND)") (class "Default")
      (node (ref "U$4") (pin "GND") (pinfunction "GND_GND") (pintype "bidirectional"))
    )
    (net (code "349") (name "unconnected-(U$4-PadGND1)") (class "Default")
      (node (ref "U$4") (pin "GND1") (pinfunction "GND1_GND1") (pintype "bidirectional"))
    )
    (net (code "350") (name "unconnected-(U$4-PadRSV)") (class "Default")
      (node (ref "U$4") (pin "RSV") (pinfunction "RSV_RSV") (pintype "bidirectional"))
    )
    (net (code "351") (name "unconnected-(U$4-PadRSV1)") (class "Default")
      (node (ref "U$4") (pin "RSV1") (pinfunction "RSV1_RSV1") (pintype "bidirectional"))
    )
    (net (code "352") (name "unconnected-(U$4-PadSD1)") (class "Default")
      (node (ref "U$4") (pin "SD1") (pinfunction "SD1_SD1") (pintype "bidirectional"))
    )
    (net (code "353") (name "unconnected-(U$4-PadSD2)") (class "Default")
      (node (ref "U$4") (pin "SD2") (pinfunction "SD2_SD2") (pintype "bidirectional"))
    )
    (net (code "354") (name "unconnected-(U$4-PadSD3)") (class "Default")
      (node (ref "U$4") (pin "SD3") (pinfunction "SD3_SD3") (pintype "bidirectional"))
    )
    (net (code "355") (name "unconnected-(U$4-PadSDD)") (class "Default")
      (node (ref "U$4") (pin "SDD") (pinfunction "SDD_SDD") (pintype "bidirectional"))
    )
    (net (code "356") (name "unconnected-(U$6-PadCS)") (class "Default")
      (node (ref "U$6") (pin "CS") (pinfunction "CS_CS") (pintype "bidirectional"))
    )
    (net (code "357") (name "unconnected-(U$9-PadCS)") (class "Default")
      (node (ref "U$9") (pin "CS") (pinfunction "CS_CS") (pintype "bidirectional"))
    )
    (net (code "358") (name "unconnected-(U$10-FSYNC-PadFSY)") (class "Default")
      (node (ref "U$10") (pin "FSY") (pinfunction "FSYNC_FSY") (pintype "bidirectional"))
    )
    (net (code "359") (name "unconnected-(U$10-INTA-PadIA)") (class "Default")
      (node (ref "U$10") (pin "IA") (pinfunction "INTA_IA") (pintype "bidirectional"))
    )
    (net (code "360") (name "unconnected-(U$10-Pad3V3)") (class "Default")
      (node (ref "U$10") (pin "3V3") (pinfunction "3V3_3V3") (pintype "bidirectional"))
    )
    (net (code "361") (name "unconnected-(U$10-PadDRDY)") (class "Default")
      (node (ref "U$10") (pin "DRDY") (pinfunction "DRDY_DRDY") (pintype "bidirectional"))
    )
    (net (code "362") (name "unconnected-(U$11-PadEN)") (class "Default")
      (node (ref "U$11") (pin "EN") (pinfunction "EN_EN") (pintype "bidirectional"))
    )
    (net (code "363") (name "unconnected-(U$11-STATE-PadST)") (class "Default")
      (node (ref "U$11") (pin "ST") (pinfunction "STATE_ST") (pintype "bidirectional"))
    )
    (net (code "364") (name "unconnected-(U$14-PadO2)") (class "Default")
      (node (ref "U$14") (pin "O2") (pinfunction "O2_O2") (pintype "bidirectional"))
    )
    (net (code "365") (name "unconnected-(U$15-PadO2)") (class "Default")
      (node (ref "U$15") (pin "O2") (pinfunction "O2_O2") (pintype "bidirectional"))
    )
    (net (code "366") (name "unconnected-(U$16-PadO2)") (class "Default")
      (node (ref "U$16") (pin "O2") (pinfunction "O2_O2") (pintype "bidirectional"))
    )
    (net (code "367") (name "unconnected-(U$32-PadO2)") (class "Default")
      (node (ref "U$32") (pin "O2") (pinfunction "O2_O2") (pintype "bidirectional"))
    )
    (net (code "368") (name "unconnected-(U$35-Pad3V3)") (class "Default")
      (node (ref "U$35") (pin "3V3") (pinfunction "3V3_3V3") (pintype "bidirectional"))
    )
    (net (code "369") (name "unconnected-(U$35-PadREF)") (class "Default")
      (node (ref "U$35") (pin "REF") (pinfunction "REF_REF") (pintype "bidirectional"))
    )
    (net (code "370") (name "unconnected-(U$35-PadRST1)") (class "Default")
      (node (ref "U$35") (pin "RST1") (pinfunction "RST1_RST1") (pintype "bidirectional"))
    )
    (net (code "371") (name "unconnected-(U$54-Pad1)") (class "Default")
      (node (ref "U$54") (pin "1") (pinfunction "1_1") (pintype "bidirectional"))
    )
    (net (code "372") (name "unconnected-(U$55-Pad1)") (class "Default")
      (node (ref "U$55") (pin "1") (pinfunction "1_1") (pintype "bidirectional"))
    )
    (net (code "373") (name "unconnected-(U$56-Pad1)") (class "Default")
      (node (ref "U$56") (pin "1") (pinfunction "1_1") (pintype "bidirectional"))
    )
    (net (code "374") (name "unconnected-(U$57-Pad1)") (class "Default")
      (node (ref "U$57") (pin "1") (pinfunction "1_1") (pintype "bidirectional"))
    )
    (net (code "375") (name "unconnected-(U$58-Pad1)") (class "Default")
      (node (ref "U$58") (pin "1") (pinfunction "1_1") (pintype "bidirectional"))
    )
    (net (code "376") (name "unconnected-(U$59-Pad1)") (class "Default")
      (node (ref "U$59") (pin "1") (pinfunction "1_1") (pintype "bidirectional"))
    )
    (net (code "377") (name "unconnected-(U$60-Pad1)") (class "Default")
      (node (ref "U$60") (pin "1") (pinfunction "1_1") (pintype "bidirectional"))
    )
    (net (code "378") (name "unconnected-(U$61-Pad1)") (class "Default")
      (node (ref "U$61") (pin "1") (pinfunction "1_1") (pintype "bidirectional"))
    )
    (net (code "379") (name "unconnected-(U$63-Pad1)") (class "Default")
      (node (ref "U$63") (pin "1") (pinfunction "1_1") (pintype "bidirectional"))
    )
    (net (code "380") (name "unconnected-(U$64-Pad1)") (class "Default")
      (node (ref "U$64") (pin "1") (pinfunction "1_1") (pintype "bidirectional"))
    )
  )
)
